# dotflipper.net
KiCad netlist of a schematic drawn in EAGLE
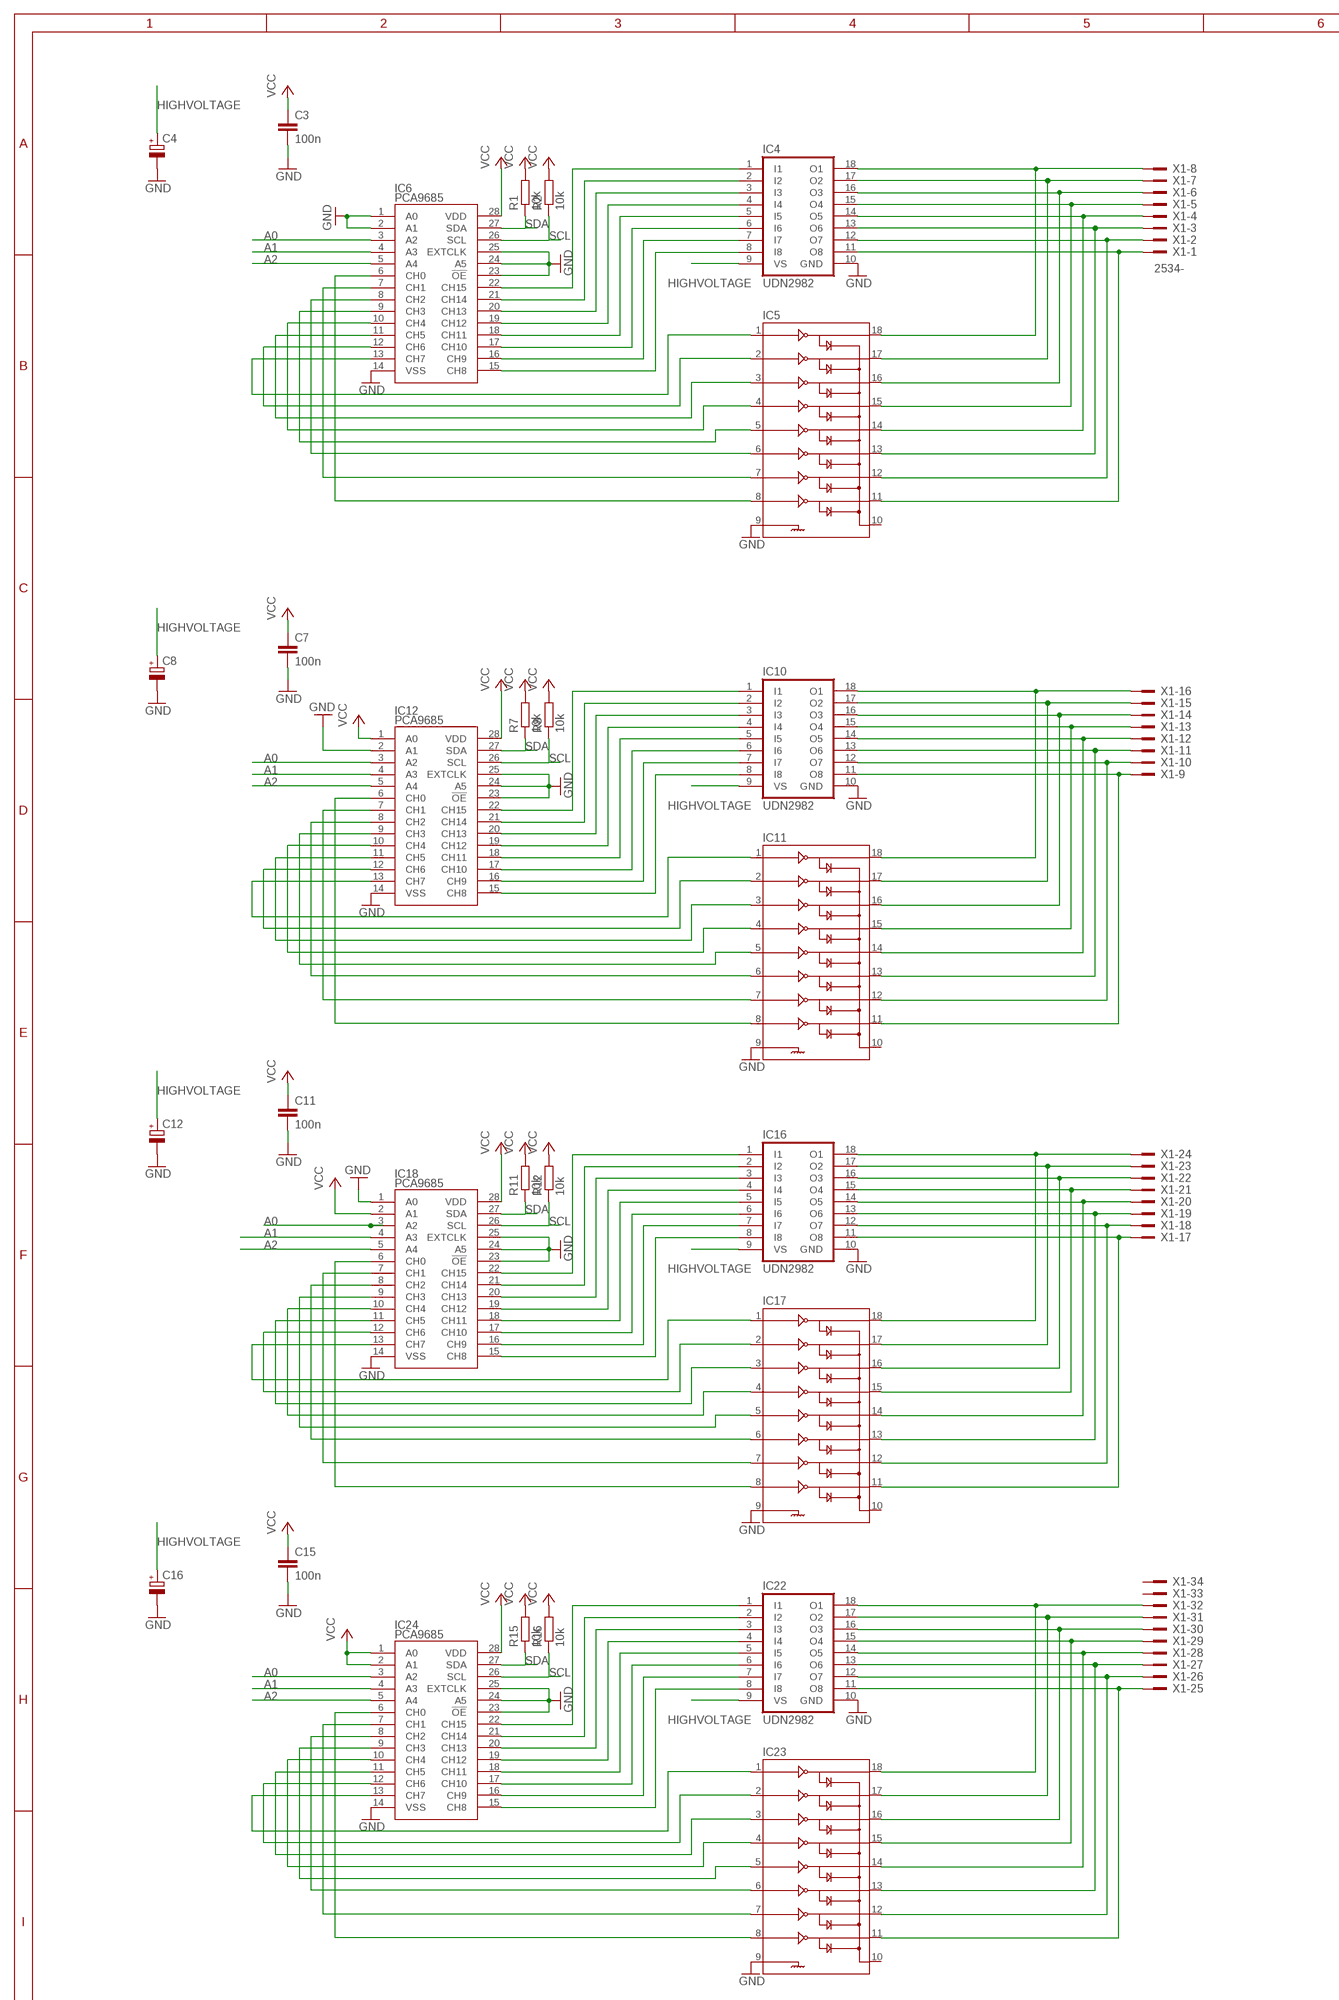
[diagram p0: schematic, sheet 1, part 1 of 2]
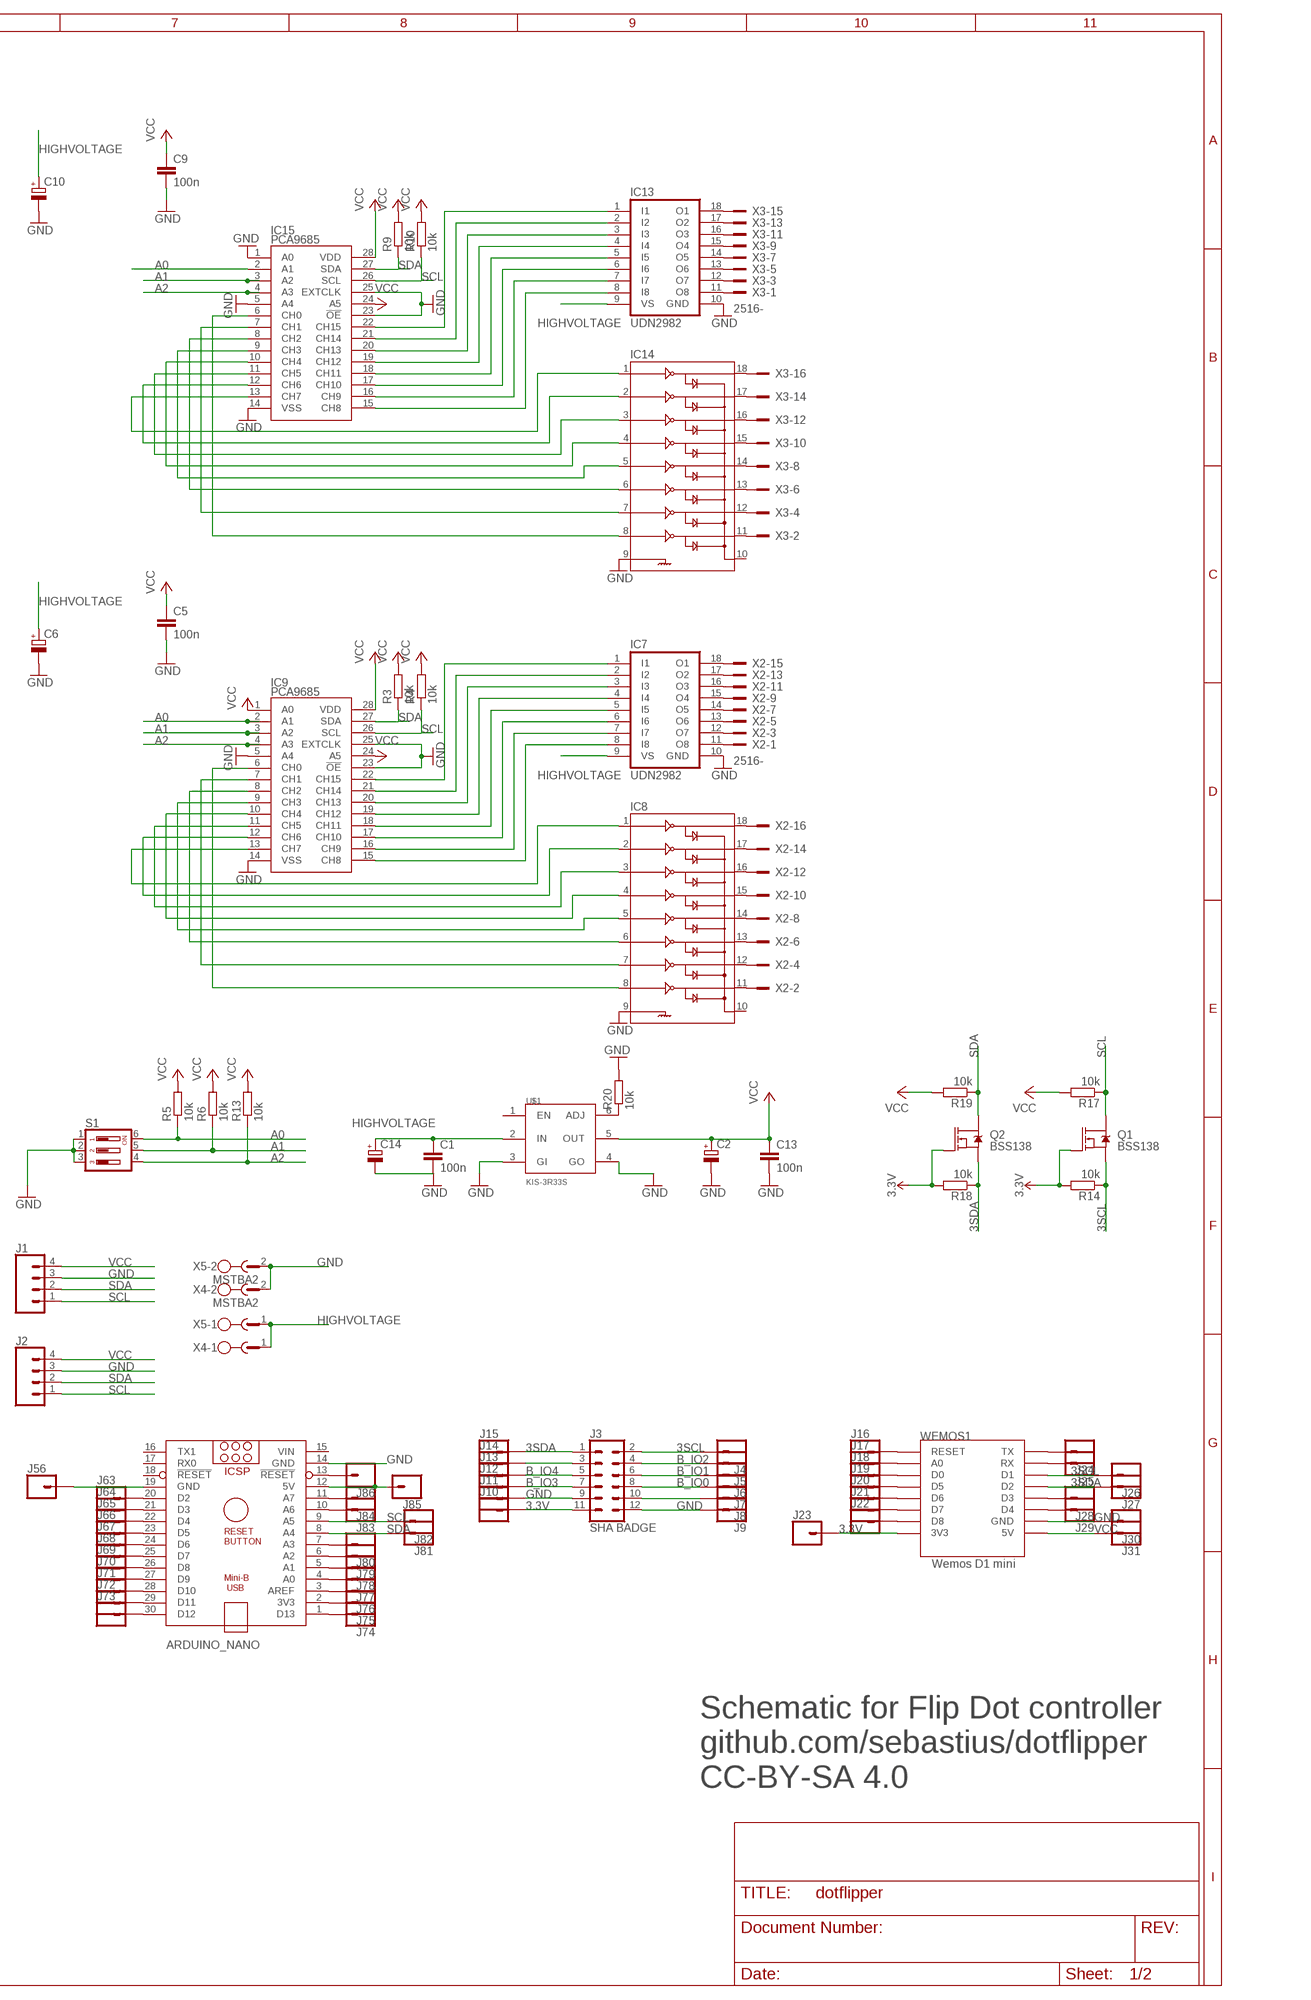
[diagram p1: schematic, sheet 1, part 2 of 2]
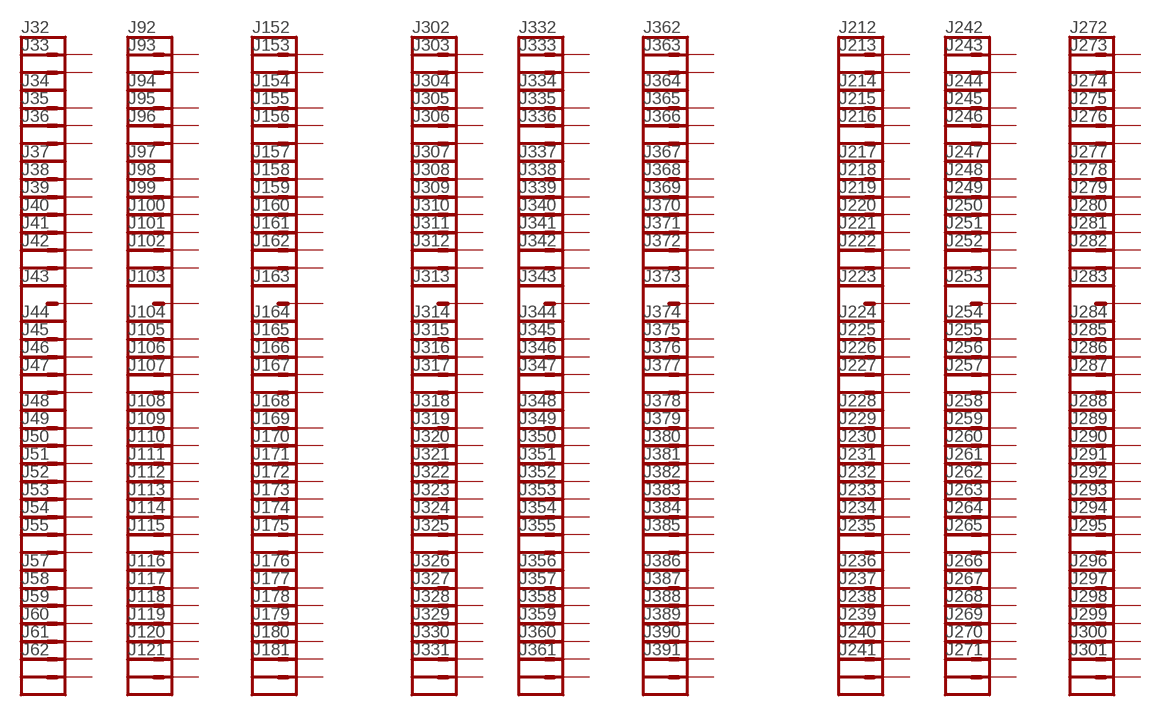
[diagram p2: schematic, sheet 2]

(export (version "E")
  (design (tool "Eeschema 10.0.6"))
  (components
    (comp (ref "ARDUINO_NANO")
      (value "ARDUINO_NANO")
      (footprint "eagle-import:ARDUINO_NANO")
      (libsource (lib "eagle-import") (part "ARDUINO_NANO"))
    )
    (comp (ref "C1")
      (value "100n")
      (footprint "eagle-import:C0603")
      (libsource (lib "eagle-import") (part "C-EUC0603"))
    )
    (comp (ref "C2")
      (value "CPOL-EUSANYO_SMD_F8")
      (footprint "eagle-import:SANYO-OSCON_SMD_F8")
      (libsource (lib "eagle-import") (part "CPOL-EUSANYO_SMD_F8"))
    )
    (comp (ref "C3")
      (value "100n")
      (footprint "eagle-import:C0603")
      (libsource (lib "eagle-import") (part "C-EUC0603"))
    )
    (comp (ref "C4")
      (value "CPOL-EUE2.5-6")
      (footprint "eagle-import:E2,5-6")
      (libsource (lib "eagle-import") (part "CPOL-EUE2.5-6"))
    )
    (comp (ref "C5")
      (value "100n")
      (footprint "eagle-import:C0603")
      (libsource (lib "eagle-import") (part "C-EUC0603"))
    )
    (comp (ref "C6")
      (value "CPOL-EUE2.5-6")
      (footprint "eagle-import:E2,5-6")
      (libsource (lib "eagle-import") (part "CPOL-EUE2.5-6"))
    )
    (comp (ref "C7")
      (value "100n")
      (footprint "eagle-import:C0603")
      (libsource (lib "eagle-import") (part "C-EUC0603"))
    )
    (comp (ref "C8")
      (value "CPOL-EUE2.5-6")
      (footprint "eagle-import:E2,5-6")
      (libsource (lib "eagle-import") (part "CPOL-EUE2.5-6"))
    )
    (comp (ref "C9")
      (value "100n")
      (footprint "eagle-import:C0603")
      (libsource (lib "eagle-import") (part "C-EUC0603"))
    )
    (comp (ref "C10")
      (value "CPOL-EUE2.5-6")
      (footprint "eagle-import:E2,5-6")
      (libsource (lib "eagle-import") (part "CPOL-EUE2.5-6"))
    )
    (comp (ref "C11")
      (value "100n")
      (footprint "eagle-import:C0603")
      (libsource (lib "eagle-import") (part "C-EUC0603"))
    )
    (comp (ref "C12")
      (value "CPOL-EUE2.5-6")
      (footprint "eagle-import:E2,5-6")
      (libsource (lib "eagle-import") (part "CPOL-EUE2.5-6"))
    )
    (comp (ref "C13")
      (value "100n")
      (footprint "eagle-import:C0603")
      (libsource (lib "eagle-import") (part "C-EUC0603"))
    )
    (comp (ref "C14")
      (value "CPOL-EUSANYO_SMD_F8")
      (footprint "eagle-import:SANYO-OSCON_SMD_F8")
      (libsource (lib "eagle-import") (part "CPOL-EUSANYO_SMD_F8"))
    )
    (comp (ref "C15")
      (value "100n")
      (footprint "eagle-import:C0603")
      (libsource (lib "eagle-import") (part "C-EUC0603"))
    )
    (comp (ref "C16")
      (value "CPOL-EUE2.5-6")
      (footprint "eagle-import:E2,5-6")
      (libsource (lib "eagle-import") (part "CPOL-EUE2.5-6"))
    )
    (comp (ref "IC4")
      (value "UDN2982")
      (footprint "eagle-import:DIL18")
      (libsource (lib "eagle-import") (part "UDN298A1"))
    )
    (comp (ref "IC5")
      (value "ULN2803DIP")
      (footprint "eagle-import:DIL18")
      (libsource (lib "eagle-import") (part "ULN2803DIP"))
    )
    (comp (ref "IC6")
      (value "PCA9685")
      (footprint "eagle-import:TSSOP-28_4MM")
      (libsource (lib "eagle-import") (part "PCA9685"))
    )
    (comp (ref "IC7")
      (value "UDN2982")
      (footprint "eagle-import:DIL18")
      (libsource (lib "eagle-import") (part "UDN298A1"))
    )
    (comp (ref "IC8")
      (value "ULN2803DIP")
      (footprint "eagle-import:DIL18")
      (libsource (lib "eagle-import") (part "ULN2803DIP"))
    )
    (comp (ref "IC9")
      (value "PCA9685")
      (footprint "eagle-import:TSSOP-28_4MM")
      (libsource (lib "eagle-import") (part "PCA9685"))
    )
    (comp (ref "IC10")
      (value "UDN2982")
      (footprint "eagle-import:DIL18")
      (libsource (lib "eagle-import") (part "UDN298A1"))
    )
    (comp (ref "IC11")
      (value "ULN2803DIP")
      (footprint "eagle-import:DIL18")
      (libsource (lib "eagle-import") (part "ULN2803DIP"))
    )
    (comp (ref "IC12")
      (value "PCA9685")
      (footprint "eagle-import:TSSOP-28_4MM")
      (libsource (lib "eagle-import") (part "PCA9685"))
    )
    (comp (ref "IC13")
      (value "UDN2982")
      (footprint "eagle-import:DIL18")
      (libsource (lib "eagle-import") (part "UDN298A1"))
    )
    (comp (ref "IC14")
      (value "ULN2803DIP")
      (footprint "eagle-import:DIL18")
      (libsource (lib "eagle-import") (part "ULN2803DIP"))
    )
    (comp (ref "IC15")
      (value "PCA9685")
      (footprint "eagle-import:TSSOP-28_4MM")
      (libsource (lib "eagle-import") (part "PCA9685"))
    )
    (comp (ref "IC16")
      (value "UDN2982")
      (footprint "eagle-import:DIL18")
      (libsource (lib "eagle-import") (part "UDN298A1"))
    )
    (comp (ref "IC17")
      (value "ULN2803DIP")
      (footprint "eagle-import:DIL18")
      (libsource (lib "eagle-import") (part "ULN2803DIP"))
    )
    (comp (ref "IC18")
      (value "PCA9685")
      (footprint "eagle-import:TSSOP-28_4MM")
      (libsource (lib "eagle-import") (part "PCA9685"))
    )
    (comp (ref "IC22")
      (value "UDN2982")
      (footprint "eagle-import:DIL18")
      (libsource (lib "eagle-import") (part "UDN298A1"))
    )
    (comp (ref "IC23")
      (value "ULN2803DIP")
      (footprint "eagle-import:DIL18")
      (libsource (lib "eagle-import") (part "ULN2803DIP"))
    )
    (comp (ref "IC24")
      (value "PCA9685")
      (footprint "eagle-import:TSSOP-28_4MM")
      (libsource (lib "eagle-import") (part "PCA9685"))
    )
    (comp (ref "J1")
      (value "CONN_04")
      (footprint "eagle-import:1X04")
      (libsource (lib "eagle-import") (part "CONN_04"))
    )
    (comp (ref "J2")
      (value "CONN_04")
      (footprint "eagle-import:1X04")
      (libsource (lib "eagle-import") (part "CONN_04"))
    )
    (comp (ref "J3")
      (value "SHA BADGE")
      (footprint "eagle-import:2X6")
      (libsource (lib "eagle-import") (part "CONN_06X2PTH_FEMALE"))
    )
    (comp (ref "J4")
      (value "CONN_01")
      (footprint "eagle-import:1X01")
      (libsource (lib "eagle-import") (part "CONN_01"))
    )
    (comp (ref "J5")
      (value "CONN_01")
      (footprint "eagle-import:1X01")
      (libsource (lib "eagle-import") (part "CONN_01"))
    )
    (comp (ref "J6")
      (value "CONN_01")
      (footprint "eagle-import:1X01")
      (libsource (lib "eagle-import") (part "CONN_01"))
    )
    (comp (ref "J7")
      (value "CONN_01")
      (footprint "eagle-import:1X01")
      (libsource (lib "eagle-import") (part "CONN_01"))
    )
    (comp (ref "J8")
      (value "CONN_01")
      (footprint "eagle-import:1X01")
      (libsource (lib "eagle-import") (part "CONN_01"))
    )
    (comp (ref "J9")
      (value "CONN_01")
      (footprint "eagle-import:1X01")
      (libsource (lib "eagle-import") (part "CONN_01"))
    )
    (comp (ref "J10")
      (value "CONN_01")
      (footprint "eagle-import:1X01")
      (libsource (lib "eagle-import") (part "CONN_01"))
    )
    (comp (ref "J11")
      (value "CONN_01")
      (footprint "eagle-import:1X01")
      (libsource (lib "eagle-import") (part "CONN_01"))
    )
    (comp (ref "J12")
      (value "CONN_01")
      (footprint "eagle-import:1X01")
      (libsource (lib "eagle-import") (part "CONN_01"))
    )
    (comp (ref "J13")
      (value "CONN_01")
      (footprint "eagle-import:1X01")
      (libsource (lib "eagle-import") (part "CONN_01"))
    )
    (comp (ref "J14")
      (value "CONN_01")
      (footprint "eagle-import:1X01")
      (libsource (lib "eagle-import") (part "CONN_01"))
    )
    (comp (ref "J15")
      (value "CONN_01")
      (footprint "eagle-import:1X01")
      (libsource (lib "eagle-import") (part "CONN_01"))
    )
    (comp (ref "J16")
      (value "CONN_01")
      (footprint "eagle-import:1X01")
      (libsource (lib "eagle-import") (part "CONN_01"))
    )
    (comp (ref "J17")
      (value "CONN_01")
      (footprint "eagle-import:1X01")
      (libsource (lib "eagle-import") (part "CONN_01"))
    )
    (comp (ref "J18")
      (value "CONN_01")
      (footprint "eagle-import:1X01")
      (libsource (lib "eagle-import") (part "CONN_01"))
    )
    (comp (ref "J19")
      (value "CONN_01")
      (footprint "eagle-import:1X01")
      (libsource (lib "eagle-import") (part "CONN_01"))
    )
    (comp (ref "J20")
      (value "CONN_01")
      (footprint "eagle-import:1X01")
      (libsource (lib "eagle-import") (part "CONN_01"))
    )
    (comp (ref "J21")
      (value "CONN_01")
      (footprint "eagle-import:1X01")
      (libsource (lib "eagle-import") (part "CONN_01"))
    )
    (comp (ref "J22")
      (value "CONN_01")
      (footprint "eagle-import:1X01")
      (libsource (lib "eagle-import") (part "CONN_01"))
    )
    (comp (ref "J23")
      (value "CONN_01")
      (footprint "eagle-import:1X01")
      (libsource (lib "eagle-import") (part "CONN_01"))
    )
    (comp (ref "J24")
      (value "CONN_01")
      (footprint "eagle-import:1X01")
      (libsource (lib "eagle-import") (part "CONN_01"))
    )
    (comp (ref "J25")
      (value "CONN_01")
      (footprint "eagle-import:1X01")
      (libsource (lib "eagle-import") (part "CONN_01"))
    )
    (comp (ref "J26")
      (value "CONN_01")
      (footprint "eagle-import:1X01")
      (libsource (lib "eagle-import") (part "CONN_01"))
    )
    (comp (ref "J27")
      (value "CONN_01")
      (footprint "eagle-import:1X01")
      (libsource (lib "eagle-import") (part "CONN_01"))
    )
    (comp (ref "J28")
      (value "CONN_01")
      (footprint "eagle-import:1X01")
      (libsource (lib "eagle-import") (part "CONN_01"))
    )
    (comp (ref "J29")
      (value "CONN_01")
      (footprint "eagle-import:1X01")
      (libsource (lib "eagle-import") (part "CONN_01"))
    )
    (comp (ref "J30")
      (value "CONN_01")
      (footprint "eagle-import:1X01")
      (libsource (lib "eagle-import") (part "CONN_01"))
    )
    (comp (ref "J31")
      (value "CONN_01")
      (footprint "eagle-import:1X01")
      (libsource (lib "eagle-import") (part "CONN_01"))
    )
    (comp (ref "J56")
      (value "CONN_01")
      (footprint "eagle-import:1X01")
      (libsource (lib "eagle-import") (part "CONN_01"))
    )
    (comp (ref "J63")
      (value "CONN_01")
      (footprint "eagle-import:1X01")
      (libsource (lib "eagle-import") (part "CONN_01"))
    )
    (comp (ref "J64")
      (value "CONN_01")
      (footprint "eagle-import:1X01")
      (libsource (lib "eagle-import") (part "CONN_01"))
    )
    (comp (ref "J65")
      (value "CONN_01")
      (footprint "eagle-import:1X01")
      (libsource (lib "eagle-import") (part "CONN_01"))
    )
    (comp (ref "J66")
      (value "CONN_01")
      (footprint "eagle-import:1X01")
      (libsource (lib "eagle-import") (part "CONN_01"))
    )
    (comp (ref "J67")
      (value "CONN_01")
      (footprint "eagle-import:1X01")
      (libsource (lib "eagle-import") (part "CONN_01"))
    )
    (comp (ref "J68")
      (value "CONN_01")
      (footprint "eagle-import:1X01")
      (libsource (lib "eagle-import") (part "CONN_01"))
    )
    (comp (ref "J69")
      (value "CONN_01")
      (footprint "eagle-import:1X01")
      (libsource (lib "eagle-import") (part "CONN_01"))
    )
    (comp (ref "J70")
      (value "CONN_01")
      (footprint "eagle-import:1X01")
      (libsource (lib "eagle-import") (part "CONN_01"))
    )
    (comp (ref "J71")
      (value "CONN_01")
      (footprint "eagle-import:1X01")
      (libsource (lib "eagle-import") (part "CONN_01"))
    )
    (comp (ref "J72")
      (value "CONN_01")
      (footprint "eagle-import:1X01")
      (libsource (lib "eagle-import") (part "CONN_01"))
    )
    (comp (ref "J73")
      (value "CONN_01")
      (footprint "eagle-import:1X01")
      (libsource (lib "eagle-import") (part "CONN_01"))
    )
    (comp (ref "J74")
      (value "CONN_01")
      (footprint "eagle-import:1X01")
      (libsource (lib "eagle-import") (part "CONN_01"))
    )
    (comp (ref "J75")
      (value "CONN_01")
      (footprint "eagle-import:1X01")
      (libsource (lib "eagle-import") (part "CONN_01"))
    )
    (comp (ref "J76")
      (value "CONN_01")
      (footprint "eagle-import:1X01")
      (libsource (lib "eagle-import") (part "CONN_01"))
    )
    (comp (ref "J77")
      (value "CONN_01")
      (footprint "eagle-import:1X01")
      (libsource (lib "eagle-import") (part "CONN_01"))
    )
    (comp (ref "J78")
      (value "CONN_01")
      (footprint "eagle-import:1X01")
      (libsource (lib "eagle-import") (part "CONN_01"))
    )
    (comp (ref "J79")
      (value "CONN_01")
      (footprint "eagle-import:1X01")
      (libsource (lib "eagle-import") (part "CONN_01"))
    )
    (comp (ref "J80")
      (value "CONN_01")
      (footprint "eagle-import:1X01")
      (libsource (lib "eagle-import") (part "CONN_01"))
    )
    (comp (ref "J81")
      (value "CONN_01")
      (footprint "eagle-import:1X01")
      (libsource (lib "eagle-import") (part "CONN_01"))
    )
    (comp (ref "J82")
      (value "CONN_01")
      (footprint "eagle-import:1X01")
      (libsource (lib "eagle-import") (part "CONN_01"))
    )
    (comp (ref "J83")
      (value "CONN_01")
      (footprint "eagle-import:1X01")
      (libsource (lib "eagle-import") (part "CONN_01"))
    )
    (comp (ref "J84")
      (value "CONN_01")
      (footprint "eagle-import:1X01")
      (libsource (lib "eagle-import") (part "CONN_01"))
    )
    (comp (ref "J85")
      (value "CONN_01")
      (footprint "eagle-import:1X01")
      (libsource (lib "eagle-import") (part "CONN_01"))
    )
    (comp (ref "J86")
      (value "CONN_01")
      (footprint "eagle-import:1X01")
      (libsource (lib "eagle-import") (part "CONN_01"))
    )
    (comp (ref "Q1")
      (value "BSS138")
      (footprint "eagle-import:SOT23-3")
      (libsource (lib "eagle-import") (part "MOSFET-NCH-BSS138"))
    )
    (comp (ref "Q2")
      (value "BSS138")
      (footprint "eagle-import:SOT23-3")
      (libsource (lib "eagle-import") (part "MOSFET-NCH-BSS138"))
    )
    (comp (ref "R1")
      (value "10k")
      (footprint "eagle-import:R0603")
      (libsource (lib "eagle-import") (part "R-EU_R0603"))
    )
    (comp (ref "R2")
      (value "10k")
      (footprint "eagle-import:R0603")
      (libsource (lib "eagle-import") (part "R-EU_R0603"))
    )
    (comp (ref "R3")
      (value "10k")
      (footprint "eagle-import:R0603")
      (libsource (lib "eagle-import") (part "R-EU_R0603"))
    )
    (comp (ref "R4")
      (value "10k")
      (footprint "eagle-import:R0603")
      (libsource (lib "eagle-import") (part "R-EU_R0603"))
    )
    (comp (ref "R5")
      (value "10k")
      (footprint "eagle-import:R0603")
      (libsource (lib "eagle-import") (part "R-EU_R0603"))
    )
    (comp (ref "R6")
      (value "10k")
      (footprint "eagle-import:R0603")
      (libsource (lib "eagle-import") (part "R-EU_R0603"))
    )
    (comp (ref "R7")
      (value "10k")
      (footprint "eagle-import:R0603")
      (libsource (lib "eagle-import") (part "R-EU_R0603"))
    )
    (comp (ref "R8")
      (value "10k")
      (footprint "eagle-import:R0603")
      (libsource (lib "eagle-import") (part "R-EU_R0603"))
    )
    (comp (ref "R9")
      (value "10k")
      (footprint "eagle-import:R0603")
      (libsource (lib "eagle-import") (part "R-EU_R0603"))
    )
    (comp (ref "R10")
      (value "10k")
      (footprint "eagle-import:R0603")
      (libsource (lib "eagle-import") (part "R-EU_R0603"))
    )
    (comp (ref "R11")
      (value "10k")
      (footprint "eagle-import:R0603")
      (libsource (lib "eagle-import") (part "R-EU_R0603"))
    )
    (comp (ref "R12")
      (value "10k")
      (footprint "eagle-import:R0603")
      (libsource (lib "eagle-import") (part "R-EU_R0603"))
    )
    (comp (ref "R13")
      (value "10k")
      (footprint "eagle-import:R0603")
      (libsource (lib "eagle-import") (part "R-EU_R0603"))
    )
    (comp (ref "R14")
      (value "10k")
      (footprint "eagle-import:R0603")
      (libsource (lib "eagle-import") (part "R-EU_R0603"))
    )
    (comp (ref "R15")
      (value "10k")
      (footprint "eagle-import:R0603")
      (libsource (lib "eagle-import") (part "R-EU_R0603"))
    )
    (comp (ref "R16")
      (value "10k")
      (footprint "eagle-import:R0603")
      (libsource (lib "eagle-import") (part "R-EU_R0603"))
    )
    (comp (ref "R17")
      (value "10k")
      (footprint "eagle-import:R0603")
      (libsource (lib "eagle-import") (part "R-EU_R0603"))
    )
    (comp (ref "R18")
      (value "10k")
      (footprint "eagle-import:R0603")
      (libsource (lib "eagle-import") (part "R-EU_R0603"))
    )
    (comp (ref "R19")
      (value "10k")
      (footprint "eagle-import:R0603")
      (libsource (lib "eagle-import") (part "R-EU_R0603"))
    )
    (comp (ref "R20")
      (value "10k")
      (footprint "eagle-import:R0603")
      (libsource (lib "eagle-import") (part "R-EU_R0603"))
    )
    (comp (ref "S1")
      (value "DIP03YL")
      (footprint "eagle-import:DIP03YL")
      (libsource (lib "eagle-import") (part "DIP03YL"))
    )
    (comp (ref "U$1")
      (value "KIS-3R33S")
      (footprint "eagle-import:KIS-3R33S")
      (libsource (lib "eagle-import") (part "KIS-3R33S"))
    )
    (comp (ref "WEMOS1")
      (value "Wemos D1 mini")
      (footprint "eagle-import:WEMOS-D1-MINI")
      (libsource (lib "eagle-import") (part "WEMOS-D1-MINI"))
    )
    (comp (ref "X1")
      (value "2534-")
      (footprint "eagle-import:PAK100_2500-34")
      (libsource (lib "eagle-import") (part "2534-"))
    )
    (comp (ref "X2")
      (value "2516-")
      (footprint "eagle-import:PAK100_2500-16")
      (libsource (lib "eagle-import") (part "2516-"))
    )
    (comp (ref "X3")
      (value "2516-")
      (footprint "eagle-import:PAK100_2500-16")
      (libsource (lib "eagle-import") (part "2516-"))
    )
    (comp (ref "X4")
      (value "MSTBA2")
      (footprint "eagle-import:MSTBA2")
      (fields (field (name "MF") "FARNELL") (field (name "MPN") "1757242"))
      (libsource (lib "eagle-import") (part "MSTBA2"))
    )
    (comp (ref "X5")
      (value "MSTBA2")
      (footprint "eagle-import:MSTBA2")
      (fields (field (name "MF") "FARNELL") (field (name "MPN") "1757242"))
      (libsource (lib "eagle-import") (part "MSTBA2"))
    )
    (comp (ref "J32")
      (value "CONN_01")
      (footprint "eagle-import:1X01")
      (libsource (lib "eagle-import") (part "CONN_01"))
    )
    (comp (ref "J33")
      (value "CONN_01")
      (footprint "eagle-import:1X01")
      (libsource (lib "eagle-import") (part "CONN_01"))
    )
    (comp (ref "J34")
      (value "CONN_01")
      (footprint "eagle-import:1X01")
      (libsource (lib "eagle-import") (part "CONN_01"))
    )
    (comp (ref "J35")
      (value "CONN_01")
      (footprint "eagle-import:1X01")
      (libsource (lib "eagle-import") (part "CONN_01"))
    )
    (comp (ref "J36")
      (value "CONN_01")
      (footprint "eagle-import:1X01")
      (libsource (lib "eagle-import") (part "CONN_01"))
    )
    (comp (ref "J37")
      (value "CONN_01")
      (footprint "eagle-import:1X01")
      (libsource (lib "eagle-import") (part "CONN_01"))
    )
    (comp (ref "J38")
      (value "CONN_01")
      (footprint "eagle-import:1X01")
      (libsource (lib "eagle-import") (part "CONN_01"))
    )
    (comp (ref "J39")
      (value "CONN_01")
      (footprint "eagle-import:1X01")
      (libsource (lib "eagle-import") (part "CONN_01"))
    )
    (comp (ref "J40")
      (value "CONN_01")
      (footprint "eagle-import:1X01")
      (libsource (lib "eagle-import") (part "CONN_01"))
    )
    (comp (ref "J41")
      (value "CONN_01")
      (footprint "eagle-import:1X01")
      (libsource (lib "eagle-import") (part "CONN_01"))
    )
    (comp (ref "J42")
      (value "CONN_01")
      (footprint "eagle-import:1X01")
      (libsource (lib "eagle-import") (part "CONN_01"))
    )
    (comp (ref "J43")
      (value "CONN_01")
      (footprint "eagle-import:1X01")
      (libsource (lib "eagle-import") (part "CONN_01"))
    )
    (comp (ref "J44")
      (value "CONN_01")
      (footprint "eagle-import:1X01")
      (libsource (lib "eagle-import") (part "CONN_01"))
    )
    (comp (ref "J45")
      (value "CONN_01")
      (footprint "eagle-import:1X01")
      (libsource (lib "eagle-import") (part "CONN_01"))
    )
    (comp (ref "J46")
      (value "CONN_01")
      (footprint "eagle-import:1X01")
      (libsource (lib "eagle-import") (part "CONN_01"))
    )
    (comp (ref "J47")
      (value "CONN_01")
      (footprint "eagle-import:1X01")
      (libsource (lib "eagle-import") (part "CONN_01"))
    )
    (comp (ref "J48")
      (value "CONN_01")
      (footprint "eagle-import:1X01")
      (libsource (lib "eagle-import") (part "CONN_01"))
    )
    (comp (ref "J49")
      (value "CONN_01")
      (footprint "eagle-import:1X01")
      (libsource (lib "eagle-import") (part "CONN_01"))
    )
    (comp (ref "J50")
      (value "CONN_01")
      (footprint "eagle-import:1X01")
      (libsource (lib "eagle-import") (part "CONN_01"))
    )
    (comp (ref "J51")
      (value "CONN_01")
      (footprint "eagle-import:1X01")
      (libsource (lib "eagle-import") (part "CONN_01"))
    )
    (comp (ref "J52")
      (value "CONN_01")
      (footprint "eagle-import:1X01")
      (libsource (lib "eagle-import") (part "CONN_01"))
    )
    (comp (ref "J53")
      (value "CONN_01")
      (footprint "eagle-import:1X01")
      (libsource (lib "eagle-import") (part "CONN_01"))
    )
    (comp (ref "J54")
      (value "CONN_01")
      (footprint "eagle-import:1X01")
      (libsource (lib "eagle-import") (part "CONN_01"))
    )
    (comp (ref "J55")
      (value "CONN_01")
      (footprint "eagle-import:1X01")
      (libsource (lib "eagle-import") (part "CONN_01"))
    )
    (comp (ref "J57")
      (value "CONN_01")
      (footprint "eagle-import:1X01")
      (libsource (lib "eagle-import") (part "CONN_01"))
    )
    (comp (ref "J58")
      (value "CONN_01")
      (footprint "eagle-import:1X01")
      (libsource (lib "eagle-import") (part "CONN_01"))
    )
    (comp (ref "J59")
      (value "CONN_01")
      (footprint "eagle-import:1X01")
      (libsource (lib "eagle-import") (part "CONN_01"))
    )
    (comp (ref "J60")
      (value "CONN_01")
      (footprint "eagle-import:1X01")
      (libsource (lib "eagle-import") (part "CONN_01"))
    )
    (comp (ref "J61")
      (value "CONN_01")
      (footprint "eagle-import:1X01")
      (libsource (lib "eagle-import") (part "CONN_01"))
    )
    (comp (ref "J62")
      (value "CONN_01")
      (footprint "eagle-import:1X01")
      (libsource (lib "eagle-import") (part "CONN_01"))
    )
    (comp (ref "J92")
      (value "CONN_01")
      (footprint "eagle-import:1X01")
      (libsource (lib "eagle-import") (part "CONN_01"))
    )
    (comp (ref "J93")
      (value "CONN_01")
      (footprint "eagle-import:1X01")
      (libsource (lib "eagle-import") (part "CONN_01"))
    )
    (comp (ref "J94")
      (value "CONN_01")
      (footprint "eagle-import:1X01")
      (libsource (lib "eagle-import") (part "CONN_01"))
    )
    (comp (ref "J95")
      (value "CONN_01")
      (footprint "eagle-import:1X01")
      (libsource (lib "eagle-import") (part "CONN_01"))
    )
    (comp (ref "J96")
      (value "CONN_01")
      (footprint "eagle-import:1X01")
      (libsource (lib "eagle-import") (part "CONN_01"))
    )
    (comp (ref "J97")
      (value "CONN_01")
      (footprint "eagle-import:1X01")
      (libsource (lib "eagle-import") (part "CONN_01"))
    )
    (comp (ref "J98")
      (value "CONN_01")
      (footprint "eagle-import:1X01")
      (libsource (lib "eagle-import") (part "CONN_01"))
    )
    (comp (ref "J99")
      (value "CONN_01")
      (footprint "eagle-import:1X01")
      (libsource (lib "eagle-import") (part "CONN_01"))
    )
    (comp (ref "J100")
      (value "CONN_01")
      (footprint "eagle-import:1X01")
      (libsource (lib "eagle-import") (part "CONN_01"))
    )
    (comp (ref "J101")
      (value "CONN_01")
      (footprint "eagle-import:1X01")
      (libsource (lib "eagle-import") (part "CONN_01"))
    )
    (comp (ref "J102")
      (value "CONN_01")
      (footprint "eagle-import:1X01")
      (libsource (lib "eagle-import") (part "CONN_01"))
    )
    (comp (ref "J103")
      (value "CONN_01")
      (footprint "eagle-import:1X01")
      (libsource (lib "eagle-import") (part "CONN_01"))
    )
    (comp (ref "J104")
      (value "CONN_01")
      (footprint "eagle-import:1X01")
      (libsource (lib "eagle-import") (part "CONN_01"))
    )
    (comp (ref "J105")
      (value "CONN_01")
      (footprint "eagle-import:1X01")
      (libsource (lib "eagle-import") (part "CONN_01"))
    )
    (comp (ref "J106")
      (value "CONN_01")
      (footprint "eagle-import:1X01")
      (libsource (lib "eagle-import") (part "CONN_01"))
    )
    (comp (ref "J107")
      (value "CONN_01")
      (footprint "eagle-import:1X01")
      (libsource (lib "eagle-import") (part "CONN_01"))
    )
    (comp (ref "J108")
      (value "CONN_01")
      (footprint "eagle-import:1X01")
      (libsource (lib "eagle-import") (part "CONN_01"))
    )
    (comp (ref "J109")
      (value "CONN_01")
      (footprint "eagle-import:1X01")
      (libsource (lib "eagle-import") (part "CONN_01"))
    )
    (comp (ref "J110")
      (value "CONN_01")
      (footprint "eagle-import:1X01")
      (libsource (lib "eagle-import") (part "CONN_01"))
    )
    (comp (ref "J111")
      (value "CONN_01")
      (footprint "eagle-import:1X01")
      (libsource (lib "eagle-import") (part "CONN_01"))
    )
    (comp (ref "J112")
      (value "CONN_01")
      (footprint "eagle-import:1X01")
      (libsource (lib "eagle-import") (part "CONN_01"))
    )
    (comp (ref "J113")
      (value "CONN_01")
      (footprint "eagle-import:1X01")
      (libsource (lib "eagle-import") (part "CONN_01"))
    )
    (comp (ref "J114")
      (value "CONN_01")
      (footprint "eagle-import:1X01")
      (libsource (lib "eagle-import") (part "CONN_01"))
    )
    (comp (ref "J115")
      (value "CONN_01")
      (footprint "eagle-import:1X01")
      (libsource (lib "eagle-import") (part "CONN_01"))
    )
    (comp (ref "J116")
      (value "CONN_01")
      (footprint "eagle-import:1X01")
      (libsource (lib "eagle-import") (part "CONN_01"))
    )
    (comp (ref "J117")
      (value "CONN_01")
      (footprint "eagle-import:1X01")
      (libsource (lib "eagle-import") (part "CONN_01"))
    )
    (comp (ref "J118")
      (value "CONN_01")
      (footprint "eagle-import:1X01")
      (libsource (lib "eagle-import") (part "CONN_01"))
    )
    (comp (ref "J119")
      (value "CONN_01")
      (footprint "eagle-import:1X01")
      (libsource (lib "eagle-import") (part "CONN_01"))
    )
    (comp (ref "J120")
      (value "CONN_01")
      (footprint "eagle-import:1X01")
      (libsource (lib "eagle-import") (part "CONN_01"))
    )
    (comp (ref "J121")
      (value "CONN_01")
      (footprint "eagle-import:1X01")
      (libsource (lib "eagle-import") (part "CONN_01"))
    )
    (comp (ref "J152")
      (value "CONN_01")
      (footprint "eagle-import:1X01")
      (libsource (lib "eagle-import") (part "CONN_01"))
    )
    (comp (ref "J153")
      (value "CONN_01")
      (footprint "eagle-import:1X01")
      (libsource (lib "eagle-import") (part "CONN_01"))
    )
    (comp (ref "J154")
      (value "CONN_01")
      (footprint "eagle-import:1X01")
      (libsource (lib "eagle-import") (part "CONN_01"))
    )
    (comp (ref "J155")
      (value "CONN_01")
      (footprint "eagle-import:1X01")
      (libsource (lib "eagle-import") (part "CONN_01"))
    )
    (comp (ref "J156")
      (value "CONN_01")
      (footprint "eagle-import:1X01")
      (libsource (lib "eagle-import") (part "CONN_01"))
    )
    (comp (ref "J157")
      (value "CONN_01")
      (footprint "eagle-import:1X01")
      (libsource (lib "eagle-import") (part "CONN_01"))
    )
    (comp (ref "J158")
      (value "CONN_01")
      (footprint "eagle-import:1X01")
      (libsource (lib "eagle-import") (part "CONN_01"))
    )
    (comp (ref "J159")
      (value "CONN_01")
      (footprint "eagle-import:1X01")
      (libsource (lib "eagle-import") (part "CONN_01"))
    )
    (comp (ref "J160")
      (value "CONN_01")
      (footprint "eagle-import:1X01")
      (libsource (lib "eagle-import") (part "CONN_01"))
    )
    (comp (ref "J161")
      (value "CONN_01")
      (footprint "eagle-import:1X01")
      (libsource (lib "eagle-import") (part "CONN_01"))
    )
    (comp (ref "J162")
      (value "CONN_01")
      (footprint "eagle-import:1X01")
      (libsource (lib "eagle-import") (part "CONN_01"))
    )
    (comp (ref "J163")
      (value "CONN_01")
      (footprint "eagle-import:1X01")
      (libsource (lib "eagle-import") (part "CONN_01"))
    )
    (comp (ref "J164")
      (value "CONN_01")
      (footprint "eagle-import:1X01")
      (libsource (lib "eagle-import") (part "CONN_01"))
    )
    (comp (ref "J165")
      (value "CONN_01")
      (footprint "eagle-import:1X01")
      (libsource (lib "eagle-import") (part "CONN_01"))
    )
    (comp (ref "J166")
      (value "CONN_01")
      (footprint "eagle-import:1X01")
      (libsource (lib "eagle-import") (part "CONN_01"))
    )
    (comp (ref "J167")
      (value "CONN_01")
      (footprint "eagle-import:1X01")
      (libsource (lib "eagle-import") (part "CONN_01"))
    )
    (comp (ref "J168")
      (value "CONN_01")
      (footprint "eagle-import:1X01")
      (libsource (lib "eagle-import") (part "CONN_01"))
    )
    (comp (ref "J169")
      (value "CONN_01")
      (footprint "eagle-import:1X01")
      (libsource (lib "eagle-import") (part "CONN_01"))
    )
    (comp (ref "J170")
      (value "CONN_01")
      (footprint "eagle-import:1X01")
      (libsource (lib "eagle-import") (part "CONN_01"))
    )
    (comp (ref "J171")
      (value "CONN_01")
      (footprint "eagle-import:1X01")
      (libsource (lib "eagle-import") (part "CONN_01"))
    )
    (comp (ref "J172")
      (value "CONN_01")
      (footprint "eagle-import:1X01")
      (libsource (lib "eagle-import") (part "CONN_01"))
    )
    (comp (ref "J173")
      (value "CONN_01")
      (footprint "eagle-import:1X01")
      (libsource (lib "eagle-import") (part "CONN_01"))
    )
    (comp (ref "J174")
      (value "CONN_01")
      (footprint "eagle-import:1X01")
      (libsource (lib "eagle-import") (part "CONN_01"))
    )
    (comp (ref "J175")
      (value "CONN_01")
      (footprint "eagle-import:1X01")
      (libsource (lib "eagle-import") (part "CONN_01"))
    )
    (comp (ref "J176")
      (value "CONN_01")
      (footprint "eagle-import:1X01")
      (libsource (lib "eagle-import") (part "CONN_01"))
    )
    (comp (ref "J177")
      (value "CONN_01")
      (footprint "eagle-import:1X01")
      (libsource (lib "eagle-import") (part "CONN_01"))
    )
    (comp (ref "J178")
      (value "CONN_01")
      (footprint "eagle-import:1X01")
      (libsource (lib "eagle-import") (part "CONN_01"))
    )
    (comp (ref "J179")
      (value "CONN_01")
      (footprint "eagle-import:1X01")
      (libsource (lib "eagle-import") (part "CONN_01"))
    )
    (comp (ref "J180")
      (value "CONN_01")
      (footprint "eagle-import:1X01")
      (libsource (lib "eagle-import") (part "CONN_01"))
    )
    (comp (ref "J181")
      (value "CONN_01")
      (footprint "eagle-import:1X01")
      (libsource (lib "eagle-import") (part "CONN_01"))
    )
    (comp (ref "J212")
      (value "CONN_01")
      (footprint "eagle-import:1X01")
      (libsource (lib "eagle-import") (part "CONN_01"))
    )
    (comp (ref "J213")
      (value "CONN_01")
      (footprint "eagle-import:1X01")
      (libsource (lib "eagle-import") (part "CONN_01"))
    )
    (comp (ref "J214")
      (value "CONN_01")
      (footprint "eagle-import:1X01")
      (libsource (lib "eagle-import") (part "CONN_01"))
    )
    (comp (ref "J215")
      (value "CONN_01")
      (footprint "eagle-import:1X01")
      (libsource (lib "eagle-import") (part "CONN_01"))
    )
    (comp (ref "J216")
      (value "CONN_01")
      (footprint "eagle-import:1X01")
      (libsource (lib "eagle-import") (part "CONN_01"))
    )
    (comp (ref "J217")
      (value "CONN_01")
      (footprint "eagle-import:1X01")
      (libsource (lib "eagle-import") (part "CONN_01"))
    )
    (comp (ref "J218")
      (value "CONN_01")
      (footprint "eagle-import:1X01")
      (libsource (lib "eagle-import") (part "CONN_01"))
    )
    (comp (ref "J219")
      (value "CONN_01")
      (footprint "eagle-import:1X01")
      (libsource (lib "eagle-import") (part "CONN_01"))
    )
    (comp (ref "J220")
      (value "CONN_01")
      (footprint "eagle-import:1X01")
      (libsource (lib "eagle-import") (part "CONN_01"))
    )
    (comp (ref "J221")
      (value "CONN_01")
      (footprint "eagle-import:1X01")
      (libsource (lib "eagle-import") (part "CONN_01"))
    )
    (comp (ref "J222")
      (value "CONN_01")
      (footprint "eagle-import:1X01")
      (libsource (lib "eagle-import") (part "CONN_01"))
    )
    (comp (ref "J223")
      (value "CONN_01")
      (footprint "eagle-import:1X01")
      (libsource (lib "eagle-import") (part "CONN_01"))
    )
    (comp (ref "J224")
      (value "CONN_01")
      (footprint "eagle-import:1X01")
      (libsource (lib "eagle-import") (part "CONN_01"))
    )
    (comp (ref "J225")
      (value "CONN_01")
      (footprint "eagle-import:1X01")
      (libsource (lib "eagle-import") (part "CONN_01"))
    )
    (comp (ref "J226")
      (value "CONN_01")
      (footprint "eagle-import:1X01")
      (libsource (lib "eagle-import") (part "CONN_01"))
    )
    (comp (ref "J227")
      (value "CONN_01")
      (footprint "eagle-import:1X01")
      (libsource (lib "eagle-import") (part "CONN_01"))
    )
    (comp (ref "J228")
      (value "CONN_01")
      (footprint "eagle-import:1X01")
      (libsource (lib "eagle-import") (part "CONN_01"))
    )
    (comp (ref "J229")
      (value "CONN_01")
      (footprint "eagle-import:1X01")
      (libsource (lib "eagle-import") (part "CONN_01"))
    )
    (comp (ref "J230")
      (value "CONN_01")
      (footprint "eagle-import:1X01")
      (libsource (lib "eagle-import") (part "CONN_01"))
    )
    (comp (ref "J231")
      (value "CONN_01")
      (footprint "eagle-import:1X01")
      (libsource (lib "eagle-import") (part "CONN_01"))
    )
    (comp (ref "J232")
      (value "CONN_01")
      (footprint "eagle-import:1X01")
      (libsource (lib "eagle-import") (part "CONN_01"))
    )
    (comp (ref "J233")
      (value "CONN_01")
      (footprint "eagle-import:1X01")
      (libsource (lib "eagle-import") (part "CONN_01"))
    )
    (comp (ref "J234")
      (value "CONN_01")
      (footprint "eagle-import:1X01")
      (libsource (lib "eagle-import") (part "CONN_01"))
    )
    (comp (ref "J235")
      (value "CONN_01")
      (footprint "eagle-import:1X01")
      (libsource (lib "eagle-import") (part "CONN_01"))
    )
    (comp (ref "J236")
      (value "CONN_01")
      (footprint "eagle-import:1X01")
      (libsource (lib "eagle-import") (part "CONN_01"))
    )
    (comp (ref "J237")
      (value "CONN_01")
      (footprint "eagle-import:1X01")
      (libsource (lib "eagle-import") (part "CONN_01"))
    )
    (comp (ref "J238")
      (value "CONN_01")
      (footprint "eagle-import:1X01")
      (libsource (lib "eagle-import") (part "CONN_01"))
    )
    (comp (ref "J239")
      (value "CONN_01")
      (footprint "eagle-import:1X01")
      (libsource (lib "eagle-import") (part "CONN_01"))
    )
    (comp (ref "J240")
      (value "CONN_01")
      (footprint "eagle-import:1X01")
      (libsource (lib "eagle-import") (part "CONN_01"))
    )
    (comp (ref "J241")
      (value "CONN_01")
      (footprint "eagle-import:1X01")
      (libsource (lib "eagle-import") (part "CONN_01"))
    )
    (comp (ref "J242")
      (value "CONN_01")
      (footprint "eagle-import:1X01")
      (libsource (lib "eagle-import") (part "CONN_01"))
    )
    (comp (ref "J243")
      (value "CONN_01")
      (footprint "eagle-import:1X01")
      (libsource (lib "eagle-import") (part "CONN_01"))
    )
    (comp (ref "J244")
      (value "CONN_01")
      (footprint "eagle-import:1X01")
      (libsource (lib "eagle-import") (part "CONN_01"))
    )
    (comp (ref "J245")
      (value "CONN_01")
      (footprint "eagle-import:1X01")
      (libsource (lib "eagle-import") (part "CONN_01"))
    )
    (comp (ref "J246")
      (value "CONN_01")
      (footprint "eagle-import:1X01")
      (libsource (lib "eagle-import") (part "CONN_01"))
    )
    (comp (ref "J247")
      (value "CONN_01")
      (footprint "eagle-import:1X01")
      (libsource (lib "eagle-import") (part "CONN_01"))
    )
    (comp (ref "J248")
      (value "CONN_01")
      (footprint "eagle-import:1X01")
      (libsource (lib "eagle-import") (part "CONN_01"))
    )
    (comp (ref "J249")
      (value "CONN_01")
      (footprint "eagle-import:1X01")
      (libsource (lib "eagle-import") (part "CONN_01"))
    )
    (comp (ref "J250")
      (value "CONN_01")
      (footprint "eagle-import:1X01")
      (libsource (lib "eagle-import") (part "CONN_01"))
    )
    (comp (ref "J251")
      (value "CONN_01")
      (footprint "eagle-import:1X01")
      (libsource (lib "eagle-import") (part "CONN_01"))
    )
    (comp (ref "J252")
      (value "CONN_01")
      (footprint "eagle-import:1X01")
      (libsource (lib "eagle-import") (part "CONN_01"))
    )
    (comp (ref "J253")
      (value "CONN_01")
      (footprint "eagle-import:1X01")
      (libsource (lib "eagle-import") (part "CONN_01"))
    )
    (comp (ref "J254")
      (value "CONN_01")
      (footprint "eagle-import:1X01")
      (libsource (lib "eagle-import") (part "CONN_01"))
    )
    (comp (ref "J255")
      (value "CONN_01")
      (footprint "eagle-import:1X01")
      (libsource (lib "eagle-import") (part "CONN_01"))
    )
    (comp (ref "J256")
      (value "CONN_01")
      (footprint "eagle-import:1X01")
      (libsource (lib "eagle-import") (part "CONN_01"))
    )
    (comp (ref "J257")
      (value "CONN_01")
      (footprint "eagle-import:1X01")
      (libsource (lib "eagle-import") (part "CONN_01"))
    )
    (comp (ref "J258")
      (value "CONN_01")
      (footprint "eagle-import:1X01")
      (libsource (lib "eagle-import") (part "CONN_01"))
    )
    (comp (ref "J259")
      (value "CONN_01")
      (footprint "eagle-import:1X01")
      (libsource (lib "eagle-import") (part "CONN_01"))
    )
    (comp (ref "J260")
      (value "CONN_01")
      (footprint "eagle-import:1X01")
      (libsource (lib "eagle-import") (part "CONN_01"))
    )
    (comp (ref "J261")
      (value "CONN_01")
      (footprint "eagle-import:1X01")
      (libsource (lib "eagle-import") (part "CONN_01"))
    )
    (comp (ref "J262")
      (value "CONN_01")
      (footprint "eagle-import:1X01")
      (libsource (lib "eagle-import") (part "CONN_01"))
    )
    (comp (ref "J263")
      (value "CONN_01")
      (footprint "eagle-import:1X01")
      (libsource (lib "eagle-import") (part "CONN_01"))
    )
    (comp (ref "J264")
      (value "CONN_01")
      (footprint "eagle-import:1X01")
      (libsource (lib "eagle-import") (part "CONN_01"))
    )
    (comp (ref "J265")
      (value "CONN_01")
      (footprint "eagle-import:1X01")
      (libsource (lib "eagle-import") (part "CONN_01"))
    )
    (comp (ref "J266")
      (value "CONN_01")
      (footprint "eagle-import:1X01")
      (libsource (lib "eagle-import") (part "CONN_01"))
    )
    (comp (ref "J267")
      (value "CONN_01")
      (footprint "eagle-import:1X01")
      (libsource (lib "eagle-import") (part "CONN_01"))
    )
    (comp (ref "J268")
      (value "CONN_01")
      (footprint "eagle-import:1X01")
      (libsource (lib "eagle-import") (part "CONN_01"))
    )
    (comp (ref "J269")
      (value "CONN_01")
      (footprint "eagle-import:1X01")
      (libsource (lib "eagle-import") (part "CONN_01"))
    )
    (comp (ref "J270")
      (value "CONN_01")
      (footprint "eagle-import:1X01")
      (libsource (lib "eagle-import") (part "CONN_01"))
    )
    (comp (ref "J271")
      (value "CONN_01")
      (footprint "eagle-import:1X01")
      (libsource (lib "eagle-import") (part "CONN_01"))
    )
    (comp (ref "J272")
      (value "CONN_01")
      (footprint "eagle-import:1X01")
      (libsource (lib "eagle-import") (part "CONN_01"))
    )
    (comp (ref "J273")
      (value "CONN_01")
      (footprint "eagle-import:1X01")
      (libsource (lib "eagle-import") (part "CONN_01"))
    )
    (comp (ref "J274")
      (value "CONN_01")
      (footprint "eagle-import:1X01")
      (libsource (lib "eagle-import") (part "CONN_01"))
    )
    (comp (ref "J275")
      (value "CONN_01")
      (footprint "eagle-import:1X01")
      (libsource (lib "eagle-import") (part "CONN_01"))
    )
    (comp (ref "J276")
      (value "CONN_01")
      (footprint "eagle-import:1X01")
      (libsource (lib "eagle-import") (part "CONN_01"))
    )
    (comp (ref "J277")
      (value "CONN_01")
      (footprint "eagle-import:1X01")
      (libsource (lib "eagle-import") (part "CONN_01"))
    )
    (comp (ref "J278")
      (value "CONN_01")
      (footprint "eagle-import:1X01")
      (libsource (lib "eagle-import") (part "CONN_01"))
    )
    (comp (ref "J279")
      (value "CONN_01")
      (footprint "eagle-import:1X01")
      (libsource (lib "eagle-import") (part "CONN_01"))
    )
    (comp (ref "J280")
      (value "CONN_01")
      (footprint "eagle-import:1X01")
      (libsource (lib "eagle-import") (part "CONN_01"))
    )
    (comp (ref "J281")
      (value "CONN_01")
      (footprint "eagle-import:1X01")
      (libsource (lib "eagle-import") (part "CONN_01"))
    )
    (comp (ref "J282")
      (value "CONN_01")
      (footprint "eagle-import:1X01")
      (libsource (lib "eagle-import") (part "CONN_01"))
    )
    (comp (ref "J283")
      (value "CONN_01")
      (footprint "eagle-import:1X01")
      (libsource (lib "eagle-import") (part "CONN_01"))
    )
    (comp (ref "J284")
      (value "CONN_01")
      (footprint "eagle-import:1X01")
      (libsource (lib "eagle-import") (part "CONN_01"))
    )
    (comp (ref "J285")
      (value "CONN_01")
      (footprint "eagle-import:1X01")
      (libsource (lib "eagle-import") (part "CONN_01"))
    )
    (comp (ref "J286")
      (value "CONN_01")
      (footprint "eagle-import:1X01")
      (libsource (lib "eagle-import") (part "CONN_01"))
    )
    (comp (ref "J287")
      (value "CONN_01")
      (footprint "eagle-import:1X01")
      (libsource (lib "eagle-import") (part "CONN_01"))
    )
    (comp (ref "J288")
      (value "CONN_01")
      (footprint "eagle-import:1X01")
      (libsource (lib "eagle-import") (part "CONN_01"))
    )
    (comp (ref "J289")
      (value "CONN_01")
      (footprint "eagle-import:1X01")
      (libsource (lib "eagle-import") (part "CONN_01"))
    )
    (comp (ref "J290")
      (value "CONN_01")
      (footprint "eagle-import:1X01")
      (libsource (lib "eagle-import") (part "CONN_01"))
    )
    (comp (ref "J291")
      (value "CONN_01")
      (footprint "eagle-import:1X01")
      (libsource (lib "eagle-import") (part "CONN_01"))
    )
    (comp (ref "J292")
      (value "CONN_01")
      (footprint "eagle-import:1X01")
      (libsource (lib "eagle-import") (part "CONN_01"))
    )
    (comp (ref "J293")
      (value "CONN_01")
      (footprint "eagle-import:1X01")
      (libsource (lib "eagle-import") (part "CONN_01"))
    )
    (comp (ref "J294")
      (value "CONN_01")
      (footprint "eagle-import:1X01")
      (libsource (lib "eagle-import") (part "CONN_01"))
    )
    (comp (ref "J295")
      (value "CONN_01")
      (footprint "eagle-import:1X01")
      (libsource (lib "eagle-import") (part "CONN_01"))
    )
    (comp (ref "J296")
      (value "CONN_01")
      (footprint "eagle-import:1X01")
      (libsource (lib "eagle-import") (part "CONN_01"))
    )
    (comp (ref "J297")
      (value "CONN_01")
      (footprint "eagle-import:1X01")
      (libsource (lib "eagle-import") (part "CONN_01"))
    )
    (comp (ref "J298")
      (value "CONN_01")
      (footprint "eagle-import:1X01")
      (libsource (lib "eagle-import") (part "CONN_01"))
    )
    (comp (ref "J299")
      (value "CONN_01")
      (footprint "eagle-import:1X01")
      (libsource (lib "eagle-import") (part "CONN_01"))
    )
    (comp (ref "J300")
      (value "CONN_01")
      (footprint "eagle-import:1X01")
      (libsource (lib "eagle-import") (part "CONN_01"))
    )
    (comp (ref "J301")
      (value "CONN_01")
      (footprint "eagle-import:1X01")
      (libsource (lib "eagle-import") (part "CONN_01"))
    )
    (comp (ref "J302")
      (value "CONN_01")
      (footprint "eagle-import:1X01")
      (libsource (lib "eagle-import") (part "CONN_01"))
    )
    (comp (ref "J303")
      (value "CONN_01")
      (footprint "eagle-import:1X01")
      (libsource (lib "eagle-import") (part "CONN_01"))
    )
    (comp (ref "J304")
      (value "CONN_01")
      (footprint "eagle-import:1X01")
      (libsource (lib "eagle-import") (part "CONN_01"))
    )
    (comp (ref "J305")
      (value "CONN_01")
      (footprint "eagle-import:1X01")
      (libsource (lib "eagle-import") (part "CONN_01"))
    )
    (comp (ref "J306")
      (value "CONN_01")
      (footprint "eagle-import:1X01")
      (libsource (lib "eagle-import") (part "CONN_01"))
    )
    (comp (ref "J307")
      (value "CONN_01")
      (footprint "eagle-import:1X01")
      (libsource (lib "eagle-import") (part "CONN_01"))
    )
    (comp (ref "J308")
      (value "CONN_01")
      (footprint "eagle-import:1X01")
      (libsource (lib "eagle-import") (part "CONN_01"))
    )
    (comp (ref "J309")
      (value "CONN_01")
      (footprint "eagle-import:1X01")
      (libsource (lib "eagle-import") (part "CONN_01"))
    )
    (comp (ref "J310")
      (value "CONN_01")
      (footprint "eagle-import:1X01")
      (libsource (lib "eagle-import") (part "CONN_01"))
    )
    (comp (ref "J311")
      (value "CONN_01")
      (footprint "eagle-import:1X01")
      (libsource (lib "eagle-import") (part "CONN_01"))
    )
    (comp (ref "J312")
      (value "CONN_01")
      (footprint "eagle-import:1X01")
      (libsource (lib "eagle-import") (part "CONN_01"))
    )
    (comp (ref "J313")
      (value "CONN_01")
      (footprint "eagle-import:1X01")
      (libsource (lib "eagle-import") (part "CONN_01"))
    )
    (comp (ref "J314")
      (value "CONN_01")
      (footprint "eagle-import:1X01")
      (libsource (lib "eagle-import") (part "CONN_01"))
    )
    (comp (ref "J315")
      (value "CONN_01")
      (footprint "eagle-import:1X01")
      (libsource (lib "eagle-import") (part "CONN_01"))
    )
    (comp (ref "J316")
      (value "CONN_01")
      (footprint "eagle-import:1X01")
      (libsource (lib "eagle-import") (part "CONN_01"))
    )
    (comp (ref "J317")
      (value "CONN_01")
      (footprint "eagle-import:1X01")
      (libsource (lib "eagle-import") (part "CONN_01"))
    )
    (comp (ref "J318")
      (value "CONN_01")
      (footprint "eagle-import:1X01")
      (libsource (lib "eagle-import") (part "CONN_01"))
    )
    (comp (ref "J319")
      (value "CONN_01")
      (footprint "eagle-import:1X01")
      (libsource (lib "eagle-import") (part "CONN_01"))
    )
    (comp (ref "J320")
      (value "CONN_01")
      (footprint "eagle-import:1X01")
      (libsource (lib "eagle-import") (part "CONN_01"))
    )
    (comp (ref "J321")
      (value "CONN_01")
      (footprint "eagle-import:1X01")
      (libsource (lib "eagle-import") (part "CONN_01"))
    )
    (comp (ref "J322")
      (value "CONN_01")
      (footprint "eagle-import:1X01")
      (libsource (lib "eagle-import") (part "CONN_01"))
    )
    (comp (ref "J323")
      (value "CONN_01")
      (footprint "eagle-import:1X01")
      (libsource (lib "eagle-import") (part "CONN_01"))
    )
    (comp (ref "J324")
      (value "CONN_01")
      (footprint "eagle-import:1X01")
      (libsource (lib "eagle-import") (part "CONN_01"))
    )
    (comp (ref "J325")
      (value "CONN_01")
      (footprint "eagle-import:1X01")
      (libsource (lib "eagle-import") (part "CONN_01"))
    )
    (comp (ref "J326")
      (value "CONN_01")
      (footprint "eagle-import:1X01")
      (libsource (lib "eagle-import") (part "CONN_01"))
    )
    (comp (ref "J327")
      (value "CONN_01")
      (footprint "eagle-import:1X01")
      (libsource (lib "eagle-import") (part "CONN_01"))
    )
    (comp (ref "J328")
      (value "CONN_01")
      (footprint "eagle-import:1X01")
      (libsource (lib "eagle-import") (part "CONN_01"))
    )
    (comp (ref "J329")
      (value "CONN_01")
      (footprint "eagle-import:1X01")
      (libsource (lib "eagle-import") (part "CONN_01"))
    )
    (comp (ref "J330")
      (value "CONN_01")
      (footprint "eagle-import:1X01")
      (libsource (lib "eagle-import") (part "CONN_01"))
    )
    (comp (ref "J331")
      (value "CONN_01")
      (footprint "eagle-import:1X01")
      (libsource (lib "eagle-import") (part "CONN_01"))
    )
    (comp (ref "J332")
      (value "CONN_01")
      (footprint "eagle-import:1X01")
      (libsource (lib "eagle-import") (part "CONN_01"))
    )
    (comp (ref "J333")
      (value "CONN_01")
      (footprint "eagle-import:1X01")
      (libsource (lib "eagle-import") (part "CONN_01"))
    )
    (comp (ref "J334")
      (value "CONN_01")
      (footprint "eagle-import:1X01")
      (libsource (lib "eagle-import") (part "CONN_01"))
    )
    (comp (ref "J335")
      (value "CONN_01")
      (footprint "eagle-import:1X01")
      (libsource (lib "eagle-import") (part "CONN_01"))
    )
    (comp (ref "J336")
      (value "CONN_01")
      (footprint "eagle-import:1X01")
      (libsource (lib "eagle-import") (part "CONN_01"))
    )
    (comp (ref "J337")
      (value "CONN_01")
      (footprint "eagle-import:1X01")
      (libsource (lib "eagle-import") (part "CONN_01"))
    )
    (comp (ref "J338")
      (value "CONN_01")
      (footprint "eagle-import:1X01")
      (libsource (lib "eagle-import") (part "CONN_01"))
    )
    (comp (ref "J339")
      (value "CONN_01")
      (footprint "eagle-import:1X01")
      (libsource (lib "eagle-import") (part "CONN_01"))
    )
    (comp (ref "J340")
      (value "CONN_01")
      (footprint "eagle-import:1X01")
      (libsource (lib "eagle-import") (part "CONN_01"))
    )
    (comp (ref "J341")
      (value "CONN_01")
      (footprint "eagle-import:1X01")
      (libsource (lib "eagle-import") (part "CONN_01"))
    )
    (comp (ref "J342")
      (value "CONN_01")
      (footprint "eagle-import:1X01")
      (libsource (lib "eagle-import") (part "CONN_01"))
    )
    (comp (ref "J343")
      (value "CONN_01")
      (footprint "eagle-import:1X01")
      (libsource (lib "eagle-import") (part "CONN_01"))
    )
    (comp (ref "J344")
      (value "CONN_01")
      (footprint "eagle-import:1X01")
      (libsource (lib "eagle-import") (part "CONN_01"))
    )
    (comp (ref "J345")
      (value "CONN_01")
      (footprint "eagle-import:1X01")
      (libsource (lib "eagle-import") (part "CONN_01"))
    )
    (comp (ref "J346")
      (value "CONN_01")
      (footprint "eagle-import:1X01")
      (libsource (lib "eagle-import") (part "CONN_01"))
    )
    (comp (ref "J347")
      (value "CONN_01")
      (footprint "eagle-import:1X01")
      (libsource (lib "eagle-import") (part "CONN_01"))
    )
    (comp (ref "J348")
      (value "CONN_01")
      (footprint "eagle-import:1X01")
      (libsource (lib "eagle-import") (part "CONN_01"))
    )
    (comp (ref "J349")
      (value "CONN_01")
      (footprint "eagle-import:1X01")
      (libsource (lib "eagle-import") (part "CONN_01"))
    )
    (comp (ref "J350")
      (value "CONN_01")
      (footprint "eagle-import:1X01")
      (libsource (lib "eagle-import") (part "CONN_01"))
    )
    (comp (ref "J351")
      (value "CONN_01")
      (footprint "eagle-import:1X01")
      (libsource (lib "eagle-import") (part "CONN_01"))
    )
    (comp (ref "J352")
      (value "CONN_01")
      (footprint "eagle-import:1X01")
      (libsource (lib "eagle-import") (part "CONN_01"))
    )
    (comp (ref "J353")
      (value "CONN_01")
      (footprint "eagle-import:1X01")
      (libsource (lib "eagle-import") (part "CONN_01"))
    )
    (comp (ref "J354")
      (value "CONN_01")
      (footprint "eagle-import:1X01")
      (libsource (lib "eagle-import") (part "CONN_01"))
    )
    (comp (ref "J355")
      (value "CONN_01")
      (footprint "eagle-import:1X01")
      (libsource (lib "eagle-import") (part "CONN_01"))
    )
    (comp (ref "J356")
      (value "CONN_01")
      (footprint "eagle-import:1X01")
      (libsource (lib "eagle-import") (part "CONN_01"))
    )
    (comp (ref "J357")
      (value "CONN_01")
      (footprint "eagle-import:1X01")
      (libsource (lib "eagle-import") (part "CONN_01"))
    )
    (comp (ref "J358")
      (value "CONN_01")
      (footprint "eagle-import:1X01")
      (libsource (lib "eagle-import") (part "CONN_01"))
    )
    (comp (ref "J359")
      (value "CONN_01")
      (footprint "eagle-import:1X01")
      (libsource (lib "eagle-import") (part "CONN_01"))
    )
    (comp (ref "J360")
      (value "CONN_01")
      (footprint "eagle-import:1X01")
      (libsource (lib "eagle-import") (part "CONN_01"))
    )
    (comp (ref "J361")
      (value "CONN_01")
      (footprint "eagle-import:1X01")
      (libsource (lib "eagle-import") (part "CONN_01"))
    )
    (comp (ref "J362")
      (value "CONN_01")
      (footprint "eagle-import:1X01")
      (libsource (lib "eagle-import") (part "CONN_01"))
    )
    (comp (ref "J363")
      (value "CONN_01")
      (footprint "eagle-import:1X01")
      (libsource (lib "eagle-import") (part "CONN_01"))
    )
    (comp (ref "J364")
      (value "CONN_01")
      (footprint "eagle-import:1X01")
      (libsource (lib "eagle-import") (part "CONN_01"))
    )
    (comp (ref "J365")
      (value "CONN_01")
      (footprint "eagle-import:1X01")
      (libsource (lib "eagle-import") (part "CONN_01"))
    )
    (comp (ref "J366")
      (value "CONN_01")
      (footprint "eagle-import:1X01")
      (libsource (lib "eagle-import") (part "CONN_01"))
    )
    (comp (ref "J367")
      (value "CONN_01")
      (footprint "eagle-import:1X01")
      (libsource (lib "eagle-import") (part "CONN_01"))
    )
    (comp (ref "J368")
      (value "CONN_01")
      (footprint "eagle-import:1X01")
      (libsource (lib "eagle-import") (part "CONN_01"))
    )
    (comp (ref "J369")
      (value "CONN_01")
      (footprint "eagle-import:1X01")
      (libsource (lib "eagle-import") (part "CONN_01"))
    )
    (comp (ref "J370")
      (value "CONN_01")
      (footprint "eagle-import:1X01")
      (libsource (lib "eagle-import") (part "CONN_01"))
    )
    (comp (ref "J371")
      (value "CONN_01")
      (footprint "eagle-import:1X01")
      (libsource (lib "eagle-import") (part "CONN_01"))
    )
    (comp (ref "J372")
      (value "CONN_01")
      (footprint "eagle-import:1X01")
      (libsource (lib "eagle-import") (part "CONN_01"))
    )
    (comp (ref "J373")
      (value "CONN_01")
      (footprint "eagle-import:1X01")
      (libsource (lib "eagle-import") (part "CONN_01"))
    )
    (comp (ref "J374")
      (value "CONN_01")
      (footprint "eagle-import:1X01")
      (libsource (lib "eagle-import") (part "CONN_01"))
    )
    (comp (ref "J375")
      (value "CONN_01")
      (footprint "eagle-import:1X01")
      (libsource (lib "eagle-import") (part "CONN_01"))
    )
    (comp (ref "J376")
      (value "CONN_01")
      (footprint "eagle-import:1X01")
      (libsource (lib "eagle-import") (part "CONN_01"))
    )
    (comp (ref "J377")
      (value "CONN_01")
      (footprint "eagle-import:1X01")
      (libsource (lib "eagle-import") (part "CONN_01"))
    )
    (comp (ref "J378")
      (value "CONN_01")
      (footprint "eagle-import:1X01")
      (libsource (lib "eagle-import") (part "CONN_01"))
    )
    (comp (ref "J379")
      (value "CONN_01")
      (footprint "eagle-import:1X01")
      (libsource (lib "eagle-import") (part "CONN_01"))
    )
    (comp (ref "J380")
      (value "CONN_01")
      (footprint "eagle-import:1X01")
      (libsource (lib "eagle-import") (part "CONN_01"))
    )
    (comp (ref "J381")
      (value "CONN_01")
      (footprint "eagle-import:1X01")
      (libsource (lib "eagle-import") (part "CONN_01"))
    )
    (comp (ref "J382")
      (value "CONN_01")
      (footprint "eagle-import:1X01")
      (libsource (lib "eagle-import") (part "CONN_01"))
    )
    (comp (ref "J383")
      (value "CONN_01")
      (footprint "eagle-import:1X01")
      (libsource (lib "eagle-import") (part "CONN_01"))
    )
    (comp (ref "J384")
      (value "CONN_01")
      (footprint "eagle-import:1X01")
      (libsource (lib "eagle-import") (part "CONN_01"))
    )
    (comp (ref "J385")
      (value "CONN_01")
      (footprint "eagle-import:1X01")
      (libsource (lib "eagle-import") (part "CONN_01"))
    )
    (comp (ref "J386")
      (value "CONN_01")
      (footprint "eagle-import:1X01")
      (libsource (lib "eagle-import") (part "CONN_01"))
    )
    (comp (ref "J387")
      (value "CONN_01")
      (footprint "eagle-import:1X01")
      (libsource (lib "eagle-import") (part "CONN_01"))
    )
    (comp (ref "J388")
      (value "CONN_01")
      (footprint "eagle-import:1X01")
      (libsource (lib "eagle-import") (part "CONN_01"))
    )
    (comp (ref "J389")
      (value "CONN_01")
      (footprint "eagle-import:1X01")
      (libsource (lib "eagle-import") (part "CONN_01"))
    )
    (comp (ref "J390")
      (value "CONN_01")
      (footprint "eagle-import:1X01")
      (libsource (lib "eagle-import") (part "CONN_01"))
    )
    (comp (ref "J391")
      (value "CONN_01")
      (footprint "eagle-import:1X01")
      (libsource (lib "eagle-import") (part "CONN_01"))
    )
  )
  (nets
    (net (code "1") (name "3.3V") (class "Default")
      (node (ref "J10") (pin "1") (pinfunction "1_1") (pintype "passive"))
      (node (ref "J23") (pin "1") (pinfunction "1_1") (pintype "passive"))
      (node (ref "J3") (pin "11") (pinfunction "11_11") (pintype "passive"))
      (node (ref "Q1") (pin "1") (pinfunction "G_1") (pintype "bidirectional"))
      (node (ref "Q2") (pin "1") (pinfunction "G_1") (pintype "bidirectional"))
      (node (ref "R14") (pin "2") (pinfunction "2_2") (pintype "passive"))
      (node (ref "R18") (pin "2") (pinfunction "2_2") (pintype "passive"))
      (node (ref "WEMOS1") (pin "3V3") (pinfunction "3V3_3V3") (pintype "bidirectional"))
    )
    (net (code "2") (name "3SCL") (class "Default")
      (node (ref "J26") (pin "1") (pinfunction "1_1") (pintype "passive"))
      (node (ref "J3") (pin "2") (pinfunction "2_2") (pintype "passive"))
      (node (ref "J4") (pin "1") (pinfunction "1_1") (pintype "passive"))
      (node (ref "Q1") (pin "2") (pinfunction "S_2") (pintype "bidirectional"))
      (node (ref "R14") (pin "1") (pinfunction "1_1") (pintype "passive"))
      (node (ref "WEMOS1") (pin "D1") (pinfunction "D1_D1") (pintype "bidirectional"))
    )
    (net (code "3") (name "3SDA") (class "Default")
      (node (ref "J15") (pin "1") (pinfunction "1_1") (pintype "passive"))
      (node (ref "J27") (pin "1") (pinfunction "1_1") (pintype "passive"))
      (node (ref "J3") (pin "1") (pinfunction "1_1") (pintype "passive"))
      (node (ref "Q2") (pin "2") (pinfunction "S_2") (pintype "bidirectional"))
      (node (ref "R18") (pin "1") (pinfunction "1_1") (pintype "passive"))
      (node (ref "WEMOS1") (pin "D2") (pinfunction "D2_D2") (pintype "bidirectional"))
    )
    (net (code "4") (name "A0") (class "Default")
      (node (ref "IC12") (pin "3") (pinfunction "A2_3") (pintype "bidirectional"))
      (node (ref "IC15") (pin "2") (pinfunction "A1_2") (pintype "bidirectional"))
      (node (ref "IC18") (pin "3") (pinfunction "A2_3") (pintype "bidirectional"))
      (node (ref "IC24") (pin "3") (pinfunction "A2_3") (pintype "bidirectional"))
      (node (ref "IC6") (pin "3") (pinfunction "A2_3") (pintype "bidirectional"))
      (node (ref "IC9") (pin "2") (pinfunction "A1_2") (pintype "bidirectional"))
      (node (ref "R5") (pin "1") (pinfunction "1_1") (pintype "passive"))
      (node (ref "S1") (pin "6") (pinfunction "6_6") (pintype "passive"))
    )
    (net (code "5") (name "A1") (class "Default")
      (node (ref "IC12") (pin "4") (pinfunction "A3_4") (pintype "bidirectional"))
      (node (ref "IC15") (pin "3") (pinfunction "A2_3") (pintype "bidirectional"))
      (node (ref "IC18") (pin "4") (pinfunction "A3_4") (pintype "bidirectional"))
      (node (ref "IC24") (pin "4") (pinfunction "A3_4") (pintype "bidirectional"))
      (node (ref "IC6") (pin "4") (pinfunction "A3_4") (pintype "bidirectional"))
      (node (ref "IC9") (pin "3") (pinfunction "A2_3") (pintype "bidirectional"))
      (node (ref "R6") (pin "1") (pinfunction "1_1") (pintype "passive"))
      (node (ref "S1") (pin "5") (pinfunction "5_5") (pintype "passive"))
    )
    (net (code "6") (name "A2") (class "Default")
      (node (ref "IC12") (pin "5") (pinfunction "A4_5") (pintype "bidirectional"))
      (node (ref "IC15") (pin "4") (pinfunction "A3_4") (pintype "bidirectional"))
      (node (ref "IC18") (pin "5") (pinfunction "A4_5") (pintype "bidirectional"))
      (node (ref "IC24") (pin "5") (pinfunction "A4_5") (pintype "bidirectional"))
      (node (ref "IC6") (pin "5") (pinfunction "A4_5") (pintype "bidirectional"))
      (node (ref "IC9") (pin "4") (pinfunction "A3_4") (pintype "bidirectional"))
      (node (ref "R13") (pin "1") (pinfunction "1_1") (pintype "passive"))
      (node (ref "S1") (pin "4") (pinfunction "4_4") (pintype "passive"))
    )
    (net (code "7") (name "B_IO0") (class "Default")
      (node (ref "J3") (pin "8") (pinfunction "8_8") (pintype "passive"))
      (node (ref "J7") (pin "1") (pinfunction "1_1") (pintype "passive"))
    )
    (net (code "8") (name "B_IO1") (class "Default")
      (node (ref "J3") (pin "6") (pinfunction "6_6") (pintype "passive"))
      (node (ref "J6") (pin "1") (pinfunction "1_1") (pintype "passive"))
    )
    (net (code "9") (name "B_IO2") (class "Default")
      (node (ref "J3") (pin "4") (pinfunction "4_4") (pintype "passive"))
      (node (ref "J5") (pin "1") (pinfunction "1_1") (pintype "passive"))
    )
    (net (code "10") (name "B_IO3") (class "Default")
      (node (ref "J12") (pin "1") (pinfunction "1_1") (pintype "passive"))
      (node (ref "J3") (pin "7") (pinfunction "7_7") (pintype "passive"))
    )
    (net (code "11") (name "B_IO4") (class "Default")
      (node (ref "J13") (pin "1") (pinfunction "1_1") (pintype "passive"))
      (node (ref "J3") (pin "5") (pinfunction "5_5") (pintype "passive"))
    )
    (net (code "12") (name "GND") (class "Default")
      (node (ref "ARDUINO_NANO") (pin "14") (pinfunction "GND_14") (pintype "power_in"))
      (node (ref "ARDUINO_NANO") (pin "19") (pinfunction "GND_19") (pintype "power_in"))
      (node (ref "C1") (pin "2") (pinfunction "2_2") (pintype "passive"))
      (node (ref "C10") (pin "-") (pinfunction "-_-") (pintype "passive"))
      (node (ref "C11") (pin "2") (pinfunction "2_2") (pintype "passive"))
      (node (ref "C12") (pin "-") (pinfunction "-_-") (pintype "passive"))
      (node (ref "C13") (pin "2") (pinfunction "2_2") (pintype "passive"))
      (node (ref "C14") (pin "-") (pinfunction "-_-") (pintype "passive"))
      (node (ref "C15") (pin "2") (pinfunction "2_2") (pintype "passive"))
      (node (ref "C16") (pin "-") (pinfunction "-_-") (pintype "passive"))
      (node (ref "C2") (pin "-") (pinfunction "-_-") (pintype "passive"))
      (node (ref "C3") (pin "2") (pinfunction "2_2") (pintype "passive"))
      (node (ref "C4") (pin "-") (pinfunction "-_-") (pintype "passive"))
      (node (ref "C5") (pin "2") (pinfunction "2_2") (pintype "passive"))
      (node (ref "C6") (pin "-") (pinfunction "-_-") (pintype "passive"))
      (node (ref "C7") (pin "2") (pinfunction "2_2") (pintype "passive"))
      (node (ref "C8") (pin "-") (pinfunction "-_-") (pintype "passive"))
      (node (ref "C9") (pin "2") (pinfunction "2_2") (pintype "passive"))
      (node (ref "IC10") (pin "10") (pinfunction "GND_10") (pintype "power_in"))
      (node (ref "IC11") (pin "9") (pinfunction "9_9") (pintype "bidirectional"))
      (node (ref "IC12") (pin "14") (pinfunction "VSS_14") (pintype "bidirectional"))
      (node (ref "IC12") (pin "2") (pinfunction "A1_2") (pintype "bidirectional"))
      (node (ref "IC12") (pin "23") (pinfunction "~{OE}_23") (pintype "bidirectional"))
      (node (ref "IC12") (pin "24") (pinfunction "A5_24") (pintype "bidirectional"))
      (node (ref "IC12") (pin "25") (pinfunction "EXTCLK_25") (pintype "bidirectional"))
      (node (ref "IC13") (pin "10") (pinfunction "GND_10") (pintype "power_in"))
      (node (ref "IC14") (pin "9") (pinfunction "9_9") (pintype "bidirectional"))
      (node (ref "IC15") (pin "1") (pinfunction "A0_1") (pintype "bidirectional"))
      (node (ref "IC15") (pin "14") (pinfunction "VSS_14") (pintype "bidirectional"))
      (node (ref "IC15") (pin "23") (pinfunction "~{OE}_23") (pintype "bidirectional"))
      (node (ref "IC15") (pin "25") (pinfunction "EXTCLK_25") (pintype "bidirectional"))
      (node (ref "IC15") (pin "5") (pinfunction "A4_5") (pintype "bidirectional"))
      (node (ref "IC16") (pin "10") (pinfunction "GND_10") (pintype "power_in"))
      (node (ref "IC17") (pin "9") (pinfunction "9_9") (pintype "bidirectional"))
      (node (ref "IC18") (pin "1") (pinfunction "A0_1") (pintype "bidirectional"))
      (node (ref "IC18") (pin "14") (pinfunction "VSS_14") (pintype "bidirectional"))
      (node (ref "IC18") (pin "23") (pinfunction "~{OE}_23") (pintype "bidirectional"))
      (node (ref "IC18") (pin "24") (pinfunction "A5_24") (pintype "bidirectional"))
      (node (ref "IC18") (pin "25") (pinfunction "EXTCLK_25") (pintype "bidirectional"))
      (node (ref "IC22") (pin "10") (pinfunction "GND_10") (pintype "power_in"))
      (node (ref "IC23") (pin "9") (pinfunction "9_9") (pintype "bidirectional"))
      (node (ref "IC24") (pin "14") (pinfunction "VSS_14") (pintype "bidirectional"))
      (node (ref "IC24") (pin "23") (pinfunction "~{OE}_23") (pintype "bidirectional"))
      (node (ref "IC24") (pin "24") (pinfunction "A5_24") (pintype "bidirectional"))
      (node (ref "IC24") (pin "25") (pinfunction "EXTCLK_25") (pintype "bidirectional"))
      (node (ref "IC4") (pin "10") (pinfunction "GND_10") (pintype "power_in"))
      (node (ref "IC5") (pin "9") (pinfunction "9_9") (pintype "bidirectional"))
      (node (ref "IC6") (pin "1") (pinfunction "A0_1") (pintype "bidirectional"))
      (node (ref "IC6") (pin "14") (pinfunction "VSS_14") (pintype "bidirectional"))
      (node (ref "IC6") (pin "2") (pinfunction "A1_2") (pintype "bidirectional"))
      (node (ref "IC6") (pin "23") (pinfunction "~{OE}_23") (pintype "bidirectional"))
      (node (ref "IC6") (pin "24") (pinfunction "A5_24") (pintype "bidirectional"))
      (node (ref "IC6") (pin "25") (pinfunction "EXTCLK_25") (pintype "bidirectional"))
      (node (ref "IC7") (pin "10") (pinfunction "GND_10") (pintype "power_in"))
      (node (ref "IC8") (pin "9") (pinfunction "9_9") (pintype "bidirectional"))
      (node (ref "IC9") (pin "14") (pinfunction "VSS_14") (pintype "bidirectional"))
      (node (ref "IC9") (pin "23") (pinfunction "~{OE}_23") (pintype "bidirectional"))
      (node (ref "IC9") (pin "25") (pinfunction "EXTCLK_25") (pintype "bidirectional"))
      (node (ref "IC9") (pin "5") (pinfunction "A4_5") (pintype "bidirectional"))
      (node (ref "J1") (pin "3") (pinfunction "3_3") (pintype "passive"))
      (node (ref "J11") (pin "1") (pinfunction "1_1") (pintype "passive"))
      (node (ref "J2") (pin "3") (pinfunction "3_3") (pintype "passive"))
      (node (ref "J3") (pin "12") (pinfunction "12_12") (pintype "passive"))
      (node (ref "J3") (pin "9") (pinfunction "9_9") (pintype "passive"))
      (node (ref "J30") (pin "1") (pinfunction "1_1") (pintype "passive"))
      (node (ref "J56") (pin "1") (pinfunction "1_1") (pintype "passive"))
      (node (ref "J9") (pin "1") (pinfunction "1_1") (pintype "passive"))
      (node (ref "R20") (pin "2") (pinfunction "2_2") (pintype "passive"))
      (node (ref "S1") (pin "1") (pinfunction "1_1") (pintype "passive"))
      (node (ref "S1") (pin "2") (pinfunction "2_2") (pintype "passive"))
      (node (ref "S1") (pin "3") (pinfunction "3_3") (pintype "passive"))
      (node (ref "U$1") (pin "3") (pinfunction "GI_3") (pintype "power_in"))
      (node (ref "U$1") (pin "4") (pinfunction "GO_4") (pintype "power_in"))
      (node (ref "WEMOS1") (pin "GND") (pinfunction "GND_GND") (pintype "bidirectional"))
      (node (ref "X4") (pin "2") (pinfunction "1_2") (pintype "passive"))
      (node (ref "X5") (pin "2") (pinfunction "1_2") (pintype "passive"))
    )
    (net (code "13") (name "HIGHVOLTAGE") (class "Default")
      (node (ref "C1") (pin "1") (pinfunction "1_1") (pintype "passive"))
      (node (ref "C10") (pin "+") (pinfunction "+_+") (pintype "passive"))
      (node (ref "C12") (pin "+") (pinfunction "+_+") (pintype "passive"))
      (node (ref "C14") (pin "+") (pinfunction "+_+") (pintype "passive"))
      (node (ref "C16") (pin "+") (pinfunction "+_+") (pintype "passive"))
      (node (ref "C4") (pin "+") (pinfunction "+_+") (pintype "passive"))
      (node (ref "C6") (pin "+") (pinfunction "+_+") (pintype "passive"))
      (node (ref "C8") (pin "+") (pinfunction "+_+") (pintype "passive"))
      (node (ref "IC10") (pin "9") (pinfunction "VS_9") (pintype "passive"))
      (node (ref "IC13") (pin "9") (pinfunction "VS_9") (pintype "passive"))
      (node (ref "IC16") (pin "9") (pinfunction "VS_9") (pintype "passive"))
      (node (ref "IC22") (pin "9") (pinfunction "VS_9") (pintype "passive"))
      (node (ref "IC4") (pin "9") (pinfunction "VS_9") (pintype "passive"))
      (node (ref "IC7") (pin "9") (pinfunction "VS_9") (pintype "passive"))
      (node (ref "U$1") (pin "2") (pinfunction "IN_2") (pintype "bidirectional"))
      (node (ref "X4") (pin "1") (pinfunction "1_1") (pintype "passive"))
      (node (ref "X5") (pin "1") (pinfunction "1_1") (pintype "passive"))
    )
    (net (code "14") (name "Net-(ARDUINO_NANO-3V3)") (class "Default")
      (node (ref "ARDUINO_NANO") (pin "2") (pinfunction "3V3_2") (pintype "output"))
      (node (ref "J75") (pin "1") (pinfunction "1_1") (pintype "passive"))
    )
    (net (code "15") (name "Net-(ARDUINO_NANO-A0)") (class "Default")
      (node (ref "ARDUINO_NANO") (pin "4") (pinfunction "A0_4") (pintype "bidirectional"))
      (node (ref "J77") (pin "1") (pinfunction "1_1") (pintype "passive"))
    )
    (net (code "16") (name "Net-(ARDUINO_NANO-A1)") (class "Default")
      (node (ref "ARDUINO_NANO") (pin "5") (pinfunction "A1_5") (pintype "bidirectional"))
      (node (ref "J78") (pin "1") (pinfunction "1_1") (pintype "passive"))
    )
    (net (code "17") (name "Net-(ARDUINO_NANO-A2)") (class "Default")
      (node (ref "ARDUINO_NANO") (pin "6") (pinfunction "A2_6") (pintype "bidirectional"))
      (node (ref "J79") (pin "1") (pinfunction "1_1") (pintype "passive"))
    )
    (net (code "18") (name "Net-(ARDUINO_NANO-A3)") (class "Default")
      (node (ref "ARDUINO_NANO") (pin "7") (pinfunction "A3_7") (pintype "bidirectional"))
      (node (ref "J80") (pin "1") (pinfunction "1_1") (pintype "passive"))
    )
    (net (code "19") (name "Net-(ARDUINO_NANO-A6)") (class "Default")
      (node (ref "ARDUINO_NANO") (pin "10") (pinfunction "A6_10") (pintype "bidirectional"))
      (node (ref "J83") (pin "1") (pinfunction "1_1") (pintype "passive"))
    )
    (net (code "20") (name "Net-(ARDUINO_NANO-A7)") (class "Default")
      (node (ref "ARDUINO_NANO") (pin "11") (pinfunction "A7_11") (pintype "bidirectional"))
      (node (ref "J84") (pin "1") (pinfunction "1_1") (pintype "passive"))
    )
    (net (code "21") (name "Net-(ARDUINO_NANO-AREF)") (class "Default")
      (node (ref "ARDUINO_NANO") (pin "3") (pinfunction "AREF_3") (pintype "input"))
      (node (ref "J76") (pin "1") (pinfunction "1_1") (pintype "passive"))
    )
    (net (code "22") (name "Net-(ARDUINO_NANO-D2)") (class "Default")
      (node (ref "ARDUINO_NANO") (pin "20") (pinfunction "D2_20") (pintype "bidirectional"))
      (node (ref "J63") (pin "1") (pinfunction "1_1") (pintype "passive"))
    )
    (net (code "23") (name "Net-(ARDUINO_NANO-D3)") (class "Default")
      (node (ref "ARDUINO_NANO") (pin "21") (pinfunction "D3_21") (pintype "bidirectional"))
      (node (ref "J64") (pin "1") (pinfunction "1_1") (pintype "passive"))
    )
    (net (code "24") (name "Net-(ARDUINO_NANO-D4)") (class "Default")
      (node (ref "ARDUINO_NANO") (pin "22") (pinfunction "D4_22") (pintype "bidirectional"))
      (node (ref "J65") (pin "1") (pinfunction "1_1") (pintype "passive"))
    )
    (net (code "25") (name "Net-(ARDUINO_NANO-D5)") (class "Default")
      (node (ref "ARDUINO_NANO") (pin "23") (pinfunction "D5_23") (pintype "bidirectional"))
      (node (ref "J66") (pin "1") (pinfunction "1_1") (pintype "passive"))
    )
    (net (code "26") (name "Net-(ARDUINO_NANO-D6)") (class "Default")
      (node (ref "ARDUINO_NANO") (pin "24") (pinfunction "D6_24") (pintype "bidirectional"))
      (node (ref "J67") (pin "1") (pinfunction "1_1") (pintype "passive"))
    )
    (net (code "27") (name "Net-(ARDUINO_NANO-D7)") (class "Default")
      (node (ref "ARDUINO_NANO") (pin "25") (pinfunction "D7_25") (pintype "bidirectional"))
      (node (ref "J68") (pin "1") (pinfunction "1_1") (pintype "passive"))
    )
    (net (code "28") (name "Net-(ARDUINO_NANO-D8)") (class "Default")
      (node (ref "ARDUINO_NANO") (pin "26") (pinfunction "D8_26") (pintype "bidirectional"))
      (node (ref "J69") (pin "1") (pinfunction "1_1") (pintype "passive"))
    )
    (net (code "29") (name "Net-(ARDUINO_NANO-D9)") (class "Default")
      (node (ref "ARDUINO_NANO") (pin "27") (pinfunction "D9_27") (pintype "bidirectional"))
      (node (ref "J70") (pin "1") (pinfunction "1_1") (pintype "passive"))
    )
    (net (code "30") (name "Net-(ARDUINO_NANO-D10)") (class "Default")
      (node (ref "ARDUINO_NANO") (pin "28") (pinfunction "D10_28") (pintype "bidirectional"))
      (node (ref "J71") (pin "1") (pinfunction "1_1") (pintype "passive"))
    )
    (net (code "31") (name "Net-(ARDUINO_NANO-D11)") (class "Default")
      (node (ref "ARDUINO_NANO") (pin "29") (pinfunction "D11_29") (pintype "bidirectional"))
      (node (ref "J72") (pin "1") (pinfunction "1_1") (pintype "passive"))
    )
    (net (code "32") (name "Net-(ARDUINO_NANO-D12)") (class "Default")
      (node (ref "ARDUINO_NANO") (pin "30") (pinfunction "D12_30") (pintype "bidirectional"))
      (node (ref "J73") (pin "1") (pinfunction "1_1") (pintype "passive"))
    )
    (net (code "33") (name "Net-(ARDUINO_NANO-D13)") (class "Default")
      (node (ref "ARDUINO_NANO") (pin "1") (pinfunction "D13_1") (pintype "bidirectional"))
      (node (ref "J74") (pin "1") (pinfunction "1_1") (pintype "passive"))
    )
    (net (code "34") (name "Net-(ARDUINO_NANO-~{RESET}-Pad13)") (class "Default")
      (node (ref "ARDUINO_NANO") (pin "13") (pinfunction "~{RESET}_13") (pintype "input"))
      (node (ref "J86") (pin "1") (pinfunction "1_1") (pintype "passive"))
    )
    (net (code "35") (name "Net-(IC4-I1)") (class "Default")
      (node (ref "IC4") (pin "1") (pinfunction "I1_1") (pintype "input"))
      (node (ref "IC6") (pin "22") (pinfunction "CH15_22") (pintype "bidirectional"))
    )
    (net (code "36") (name "Net-(IC4-I2)") (class "Default")
      (node (ref "IC4") (pin "2") (pinfunction "I2_2") (pintype "input"))
      (node (ref "IC6") (pin "21") (pinfunction "CH14_21") (pintype "bidirectional"))
    )
    (net (code "37") (name "Net-(IC4-I3)") (class "Default")
      (node (ref "IC4") (pin "3") (pinfunction "I3_3") (pintype "input"))
      (node (ref "IC6") (pin "20") (pinfunction "CH13_20") (pintype "bidirectional"))
    )
    (net (code "38") (name "Net-(IC4-I4)") (class "Default")
      (node (ref "IC4") (pin "4") (pinfunction "I4_4") (pintype "input"))
      (node (ref "IC6") (pin "19") (pinfunction "CH12_19") (pintype "bidirectional"))
    )
    (net (code "39") (name "Net-(IC4-I5)") (class "Default")
      (node (ref "IC4") (pin "5") (pinfunction "I5_5") (pintype "input"))
      (node (ref "IC6") (pin "18") (pinfunction "CH11_18") (pintype "bidirectional"))
    )
    (net (code "40") (name "Net-(IC4-I6)") (class "Default")
      (node (ref "IC4") (pin "6") (pinfunction "I6_6") (pintype "input"))
      (node (ref "IC6") (pin "17") (pinfunction "CH10_17") (pintype "bidirectional"))
    )
    (net (code "41") (name "Net-(IC4-I7)") (class "Default")
      (node (ref "IC4") (pin "7") (pinfunction "I7_7") (pintype "input"))
      (node (ref "IC6") (pin "16") (pinfunction "CH9_16") (pintype "bidirectional"))
    )
    (net (code "42") (name "Net-(IC4-I8)") (class "Default")
      (node (ref "IC4") (pin "8") (pinfunction "I8_8") (pintype "input"))
      (node (ref "IC6") (pin "15") (pinfunction "CH8_15") (pintype "bidirectional"))
    )
    (net (code "43") (name "Net-(IC4-O1)") (class "Default")
      (node (ref "IC4") (pin "18") (pinfunction "O1_18") (pintype "open_collector"))
      (node (ref "IC5") (pin "18") (pinfunction "18_18") (pintype "bidirectional"))
      (node (ref "X1") (pin "8") (pinfunction "KL_8") (pintype "passive"))
    )
    (net (code "44") (name "Net-(IC4-O2)") (class "Default")
      (node (ref "IC4") (pin "17") (pinfunction "O2_17") (pintype "open_collector"))
      (node (ref "IC5") (pin "17") (pinfunction "17_17") (pintype "bidirectional"))
      (node (ref "X1") (pin "7") (pinfunction "KL_7") (pintype "passive"))
    )
    (net (code "45") (name "Net-(IC4-O3)") (class "Default")
      (node (ref "IC4") (pin "16") (pinfunction "O3_16") (pintype "open_collector"))
      (node (ref "IC5") (pin "16") (pinfunction "16_16") (pintype "bidirectional"))
      (node (ref "X1") (pin "6") (pinfunction "KL_6") (pintype "passive"))
    )
    (net (code "46") (name "Net-(IC4-O4)") (class "Default")
      (node (ref "IC4") (pin "15") (pinfunction "O4_15") (pintype "open_collector"))
      (node (ref "IC5") (pin "15") (pinfunction "15_15") (pintype "bidirectional"))
      (node (ref "X1") (pin "5") (pinfunction "KL_5") (pintype "passive"))
    )
    (net (code "47") (name "Net-(IC4-O5)") (class "Default")
      (node (ref "IC4") (pin "14") (pinfunction "O5_14") (pintype "open_collector"))
      (node (ref "IC5") (pin "14") (pinfunction "14_14") (pintype "bidirectional"))
      (node (ref "X1") (pin "4") (pinfunction "KL_4") (pintype "passive"))
    )
    (net (code "48") (name "Net-(IC4-O6)") (class "Default")
      (node (ref "IC4") (pin "13") (pinfunction "O6_13") (pintype "open_collector"))
      (node (ref "IC5") (pin "13") (pinfunction "13_13") (pintype "bidirectional"))
      (node (ref "X1") (pin "3") (pinfunction "KL_3") (pintype "passive"))
    )
    (net (code "49") (name "Net-(IC4-O7)") (class "Default")
      (node (ref "IC4") (pin "12") (pinfunction "O7_12") (pintype "open_collector"))
      (node (ref "IC5") (pin "12") (pinfunction "12_12") (pintype "bidirectional"))
      (node (ref "X1") (pin "2") (pinfunction "KL_2") (pintype "passive"))
    )
    (net (code "50") (name "Net-(IC4-O8)") (class "Default")
      (node (ref "IC4") (pin "11") (pinfunction "O8_11") (pintype "open_collector"))
      (node (ref "IC5") (pin "11") (pinfunction "11_11") (pintype "bidirectional"))
      (node (ref "X1") (pin "1") (pinfunction "KL_1") (pintype "passive"))
    )
    (net (code "51") (name "Net-(IC6-CH0)") (class "Default")
      (node (ref "IC5") (pin "8") (pinfunction "8_8") (pintype "bidirectional"))
      (node (ref "IC6") (pin "6") (pinfunction "CH0_6") (pintype "bidirectional"))
    )
    (net (code "52") (name "Net-(IC6-CH1)") (class "Default")
      (node (ref "IC5") (pin "7") (pinfunction "7_7") (pintype "bidirectional"))
      (node (ref "IC6") (pin "7") (pinfunction "CH1_7") (pintype "bidirectional"))
    )
    (net (code "53") (name "Net-(IC6-CH2)") (class "Default")
      (node (ref "IC5") (pin "6") (pinfunction "6_6") (pintype "bidirectional"))
      (node (ref "IC6") (pin "8") (pinfunction "CH2_8") (pintype "bidirectional"))
    )
    (net (code "54") (name "Net-(IC6-CH3)") (class "Default")
      (node (ref "IC5") (pin "5") (pinfunction "5_5") (pintype "bidirectional"))
      (node (ref "IC6") (pin "9") (pinfunction "CH3_9") (pintype "bidirectional"))
    )
    (net (code "55") (name "Net-(IC6-CH4)") (class "Default")
      (node (ref "IC5") (pin "4") (pinfunction "4_4") (pintype "bidirectional"))
      (node (ref "IC6") (pin "10") (pinfunction "CH4_10") (pintype "bidirectional"))
    )
    (net (code "56") (name "Net-(IC6-CH5)") (class "Default")
      (node (ref "IC5") (pin "3") (pinfunction "3_3") (pintype "bidirectional"))
      (node (ref "IC6") (pin "11") (pinfunction "CH5_11") (pintype "bidirectional"))
    )
    (net (code "57") (name "Net-(IC6-CH6)") (class "Default")
      (node (ref "IC5") (pin "2") (pinfunction "2_2") (pintype "bidirectional"))
      (node (ref "IC6") (pin "12") (pinfunction "CH6_12") (pintype "bidirectional"))
    )
    (net (code "58") (name "Net-(IC6-CH7)") (class "Default")
      (node (ref "IC5") (pin "1") (pinfunction "1_1") (pintype "bidirectional"))
      (node (ref "IC6") (pin "13") (pinfunction "CH7_13") (pintype "bidirectional"))
    )
    (net (code "59") (name "Net-(IC7-I1)") (class "Default")
      (node (ref "IC7") (pin "1") (pinfunction "I1_1") (pintype "input"))
      (node (ref "IC9") (pin "22") (pinfunction "CH15_22") (pintype "bidirectional"))
    )
    (net (code "60") (name "Net-(IC7-I2)") (class "Default")
      (node (ref "IC7") (pin "2") (pinfunction "I2_2") (pintype "input"))
      (node (ref "IC9") (pin "21") (pinfunction "CH14_21") (pintype "bidirectional"))
    )
    (net (code "61") (name "Net-(IC7-I3)") (class "Default")
      (node (ref "IC7") (pin "3") (pinfunction "I3_3") (pintype "input"))
      (node (ref "IC9") (pin "20") (pinfunction "CH13_20") (pintype "bidirectional"))
    )
    (net (code "62") (name "Net-(IC7-I4)") (class "Default")
      (node (ref "IC7") (pin "4") (pinfunction "I4_4") (pintype "input"))
      (node (ref "IC9") (pin "19") (pinfunction "CH12_19") (pintype "bidirectional"))
    )
    (net (code "63") (name "Net-(IC7-I5)") (class "Default")
      (node (ref "IC7") (pin "5") (pinfunction "I5_5") (pintype "input"))
      (node (ref "IC9") (pin "18") (pinfunction "CH11_18") (pintype "bidirectional"))
    )
    (net (code "64") (name "Net-(IC7-I6)") (class "Default")
      (node (ref "IC7") (pin "6") (pinfunction "I6_6") (pintype "input"))
      (node (ref "IC9") (pin "17") (pinfunction "CH10_17") (pintype "bidirectional"))
    )
    (net (code "65") (name "Net-(IC7-I7)") (class "Default")
      (node (ref "IC7") (pin "7") (pinfunction "I7_7") (pintype "input"))
      (node (ref "IC9") (pin "16") (pinfunction "CH9_16") (pintype "bidirectional"))
    )
    (net (code "66") (name "Net-(IC7-I8)") (class "Default")
      (node (ref "IC7") (pin "8") (pinfunction "I8_8") (pintype "input"))
      (node (ref "IC9") (pin "15") (pinfunction "CH8_15") (pintype "bidirectional"))
    )
    (net (code "67") (name "Net-(IC7-O1)") (class "Default")
      (node (ref "IC7") (pin "18") (pinfunction "O1_18") (pintype "open_collector"))
      (node (ref "X2") (pin "15") (pinfunction "KL_15") (pintype "passive"))
    )
    (net (code "68") (name "Net-(IC7-O2)") (class "Default")
      (node (ref "IC7") (pin "17") (pinfunction "O2_17") (pintype "open_collector"))
      (node (ref "X2") (pin "13") (pinfunction "KL_13") (pintype "passive"))
    )
    (net (code "69") (name "Net-(IC7-O3)") (class "Default")
      (node (ref "IC7") (pin "16") (pinfunction "O3_16") (pintype "open_collector"))
      (node (ref "X2") (pin "11") (pinfunction "KL_11") (pintype "passive"))
    )
    (net (code "70") (name "Net-(IC7-O4)") (class "Default")
      (node (ref "IC7") (pin "15") (pinfunction "O4_15") (pintype "open_collector"))
      (node (ref "X2") (pin "9") (pinfunction "KL_9") (pintype "passive"))
    )
    (net (code "71") (name "Net-(IC7-O5)") (class "Default")
      (node (ref "IC7") (pin "14") (pinfunction "O5_14") (pintype "open_collector"))
      (node (ref "X2") (pin "7") (pinfunction "KL_7") (pintype "passive"))
    )
    (net (code "72") (name "Net-(IC7-O6)") (class "Default")
      (node (ref "IC7") (pin "13") (pinfunction "O6_13") (pintype "open_collector"))
      (node (ref "X2") (pin "5") (pinfunction "KL_5") (pintype "passive"))
    )
    (net (code "73") (name "Net-(IC7-O7)") (class "Default")
      (node (ref "IC7") (pin "12") (pinfunction "O7_12") (pintype "open_collector"))
      (node (ref "X2") (pin "3") (pinfunction "KL_3") (pintype "passive"))
    )
    (net (code "74") (name "Net-(IC7-O8)") (class "Default")
      (node (ref "IC7") (pin "11") (pinfunction "O8_11") (pintype "open_collector"))
      (node (ref "X2") (pin "1") (pinfunction "KL_1") (pintype "passive"))
    )
    (net (code "75") (name "Net-(IC9-CH0)") (class "Default")
      (node (ref "IC8") (pin "8") (pinfunction "8_8") (pintype "bidirectional"))
      (node (ref "IC9") (pin "6") (pinfunction "CH0_6") (pintype "bidirectional"))
    )
    (net (code "76") (name "Net-(IC9-CH1)") (class "Default")
      (node (ref "IC8") (pin "7") (pinfunction "7_7") (pintype "bidirectional"))
      (node (ref "IC9") (pin "7") (pinfunction "CH1_7") (pintype "bidirectional"))
    )
    (net (code "77") (name "Net-(IC9-CH2)") (class "Default")
      (node (ref "IC8") (pin "6") (pinfunction "6_6") (pintype "bidirectional"))
      (node (ref "IC9") (pin "8") (pinfunction "CH2_8") (pintype "bidirectional"))
    )
    (net (code "78") (name "Net-(IC9-CH3)") (class "Default")
      (node (ref "IC8") (pin "5") (pinfunction "5_5") (pintype "bidirectional"))
      (node (ref "IC9") (pin "9") (pinfunction "CH3_9") (pintype "bidirectional"))
    )
    (net (code "79") (name "Net-(IC9-CH4)") (class "Default")
      (node (ref "IC8") (pin "4") (pinfunction "4_4") (pintype "bidirectional"))
      (node (ref "IC9") (pin "10") (pinfunction "CH4_10") (pintype "bidirectional"))
    )
    (net (code "80") (name "Net-(IC9-CH5)") (class "Default")
      (node (ref "IC8") (pin "3") (pinfunction "3_3") (pintype "bidirectional"))
      (node (ref "IC9") (pin "11") (pinfunction "CH5_11") (pintype "bidirectional"))
    )
    (net (code "81") (name "Net-(IC9-CH6)") (class "Default")
      (node (ref "IC8") (pin "2") (pinfunction "2_2") (pintype "bidirectional"))
      (node (ref "IC9") (pin "12") (pinfunction "CH6_12") (pintype "bidirectional"))
    )
    (net (code "82") (name "Net-(IC9-CH7)") (class "Default")
      (node (ref "IC8") (pin "1") (pinfunction "1_1") (pintype "bidirectional"))
      (node (ref "IC9") (pin "13") (pinfunction "CH7_13") (pintype "bidirectional"))
    )
    (net (code "83") (name "Net-(IC10-I1)") (class "Default")
      (node (ref "IC10") (pin "1") (pinfunction "I1_1") (pintype "input"))
      (node (ref "IC12") (pin "22") (pinfunction "CH15_22") (pintype "bidirectional"))
    )
    (net (code "84") (name "Net-(IC10-I2)") (class "Default")
      (node (ref "IC10") (pin "2") (pinfunction "I2_2") (pintype "input"))
      (node (ref "IC12") (pin "21") (pinfunction "CH14_21") (pintype "bidirectional"))
    )
    (net (code "85") (name "Net-(IC10-I3)") (class "Default")
      (node (ref "IC10") (pin "3") (pinfunction "I3_3") (pintype "input"))
      (node (ref "IC12") (pin "20") (pinfunction "CH13_20") (pintype "bidirectional"))
    )
    (net (code "86") (name "Net-(IC10-I4)") (class "Default")
      (node (ref "IC10") (pin "4") (pinfunction "I4_4") (pintype "input"))
      (node (ref "IC12") (pin "19") (pinfunction "CH12_19") (pintype "bidirectional"))
    )
    (net (code "87") (name "Net-(IC10-I5)") (class "Default")
      (node (ref "IC10") (pin "5") (pinfunction "I5_5") (pintype "input"))
      (node (ref "IC12") (pin "18") (pinfunction "CH11_18") (pintype "bidirectional"))
    )
    (net (code "88") (name "Net-(IC10-I6)") (class "Default")
      (node (ref "IC10") (pin "6") (pinfunction "I6_6") (pintype "input"))
      (node (ref "IC12") (pin "17") (pinfunction "CH10_17") (pintype "bidirectional"))
    )
    (net (code "89") (name "Net-(IC10-I7)") (class "Default")
      (node (ref "IC10") (pin "7") (pinfunction "I7_7") (pintype "input"))
      (node (ref "IC12") (pin "16") (pinfunction "CH9_16") (pintype "bidirectional"))
    )
    (net (code "90") (name "Net-(IC10-I8)") (class "Default")
      (node (ref "IC10") (pin "8") (pinfunction "I8_8") (pintype "input"))
      (node (ref "IC12") (pin "15") (pinfunction "CH8_15") (pintype "bidirectional"))
    )
    (net (code "91") (name "Net-(IC10-O1)") (class "Default")
      (node (ref "IC10") (pin "18") (pinfunction "O1_18") (pintype "open_collector"))
      (node (ref "IC11") (pin "18") (pinfunction "18_18") (pintype "bidirectional"))
      (node (ref "X1") (pin "16") (pinfunction "KL_16") (pintype "passive"))
    )
    (net (code "92") (name "Net-(IC10-O2)") (class "Default")
      (node (ref "IC10") (pin "17") (pinfunction "O2_17") (pintype "open_collector"))
      (node (ref "IC11") (pin "17") (pinfunction "17_17") (pintype "bidirectional"))
      (node (ref "X1") (pin "15") (pinfunction "KL_15") (pintype "passive"))
    )
    (net (code "93") (name "Net-(IC10-O3)") (class "Default")
      (node (ref "IC10") (pin "16") (pinfunction "O3_16") (pintype "open_collector"))
      (node (ref "IC11") (pin "16") (pinfunction "16_16") (pintype "bidirectional"))
      (node (ref "X1") (pin "14") (pinfunction "KL_14") (pintype "passive"))
    )
    (net (code "94") (name "Net-(IC10-O4)") (class "Default")
      (node (ref "IC10") (pin "15") (pinfunction "O4_15") (pintype "open_collector"))
      (node (ref "IC11") (pin "15") (pinfunction "15_15") (pintype "bidirectional"))
      (node (ref "X1") (pin "13") (pinfunction "KL_13") (pintype "passive"))
    )
    (net (code "95") (name "Net-(IC10-O5)") (class "Default")
      (node (ref "IC10") (pin "14") (pinfunction "O5_14") (pintype "open_collector"))
      (node (ref "IC11") (pin "14") (pinfunction "14_14") (pintype "bidirectional"))
      (node (ref "X1") (pin "12") (pinfunction "KL_12") (pintype "passive"))
    )
    (net (code "96") (name "Net-(IC10-O6)") (class "Default")
      (node (ref "IC10") (pin "13") (pinfunction "O6_13") (pintype "open_collector"))
      (node (ref "IC11") (pin "13") (pinfunction "13_13") (pintype "bidirectional"))
      (node (ref "X1") (pin "11") (pinfunction "KL_11") (pintype "passive"))
    )
    (net (code "97") (name "Net-(IC10-O7)") (class "Default")
      (node (ref "IC10") (pin "12") (pinfunction "O7_12") (pintype "open_collector"))
      (node (ref "IC11") (pin "12") (pinfunction "12_12") (pintype "bidirectional"))
      (node (ref "X1") (pin "10") (pinfunction "KL_10") (pintype "passive"))
    )
    (net (code "98") (name "Net-(IC10-O8)") (class "Default")
      (node (ref "IC10") (pin "11") (pinfunction "O8_11") (pintype "open_collector"))
      (node (ref "IC11") (pin "11") (pinfunction "11_11") (pintype "bidirectional"))
      (node (ref "X1") (pin "9") (pinfunction "KL_9") (pintype "passive"))
    )
    (net (code "99") (name "Net-(IC12-CH0)") (class "Default")
      (node (ref "IC11") (pin "8") (pinfunction "8_8") (pintype "bidirectional"))
      (node (ref "IC12") (pin "6") (pinfunction "CH0_6") (pintype "bidirectional"))
    )
    (net (code "100") (name "Net-(IC12-CH1)") (class "Default")
      (node (ref "IC11") (pin "7") (pinfunction "7_7") (pintype "bidirectional"))
      (node (ref "IC12") (pin "7") (pinfunction "CH1_7") (pintype "bidirectional"))
    )
    (net (code "101") (name "Net-(IC12-CH2)") (class "Default")
      (node (ref "IC11") (pin "6") (pinfunction "6_6") (pintype "bidirectional"))
      (node (ref "IC12") (pin "8") (pinfunction "CH2_8") (pintype "bidirectional"))
    )
    (net (code "102") (name "Net-(IC12-CH3)") (class "Default")
      (node (ref "IC11") (pin "5") (pinfunction "5_5") (pintype "bidirectional"))
      (node (ref "IC12") (pin "9") (pinfunction "CH3_9") (pintype "bidirectional"))
    )
    (net (code "103") (name "Net-(IC12-CH4)") (class "Default")
      (node (ref "IC11") (pin "4") (pinfunction "4_4") (pintype "bidirectional"))
      (node (ref "IC12") (pin "10") (pinfunction "CH4_10") (pintype "bidirectional"))
    )
    (net (code "104") (name "Net-(IC12-CH5)") (class "Default")
      (node (ref "IC11") (pin "3") (pinfunction "3_3") (pintype "bidirectional"))
      (node (ref "IC12") (pin "11") (pinfunction "CH5_11") (pintype "bidirectional"))
    )
    (net (code "105") (name "Net-(IC12-CH6)") (class "Default")
      (node (ref "IC11") (pin "2") (pinfunction "2_2") (pintype "bidirectional"))
      (node (ref "IC12") (pin "12") (pinfunction "CH6_12") (pintype "bidirectional"))
    )
    (net (code "106") (name "Net-(IC12-CH7)") (class "Default")
      (node (ref "IC11") (pin "1") (pinfunction "1_1") (pintype "bidirectional"))
      (node (ref "IC12") (pin "13") (pinfunction "CH7_13") (pintype "bidirectional"))
    )
    (net (code "107") (name "Net-(IC13-I1)") (class "Default")
      (node (ref "IC13") (pin "1") (pinfunction "I1_1") (pintype "input"))
      (node (ref "IC15") (pin "22") (pinfunction "CH15_22") (pintype "bidirectional"))
    )
    (net (code "108") (name "Net-(IC13-I2)") (class "Default")
      (node (ref "IC13") (pin "2") (pinfunction "I2_2") (pintype "input"))
      (node (ref "IC15") (pin "21") (pinfunction "CH14_21") (pintype "bidirectional"))
    )
    (net (code "109") (name "Net-(IC13-I3)") (class "Default")
      (node (ref "IC13") (pin "3") (pinfunction "I3_3") (pintype "input"))
      (node (ref "IC15") (pin "20") (pinfunction "CH13_20") (pintype "bidirectional"))
    )
    (net (code "110") (name "Net-(IC13-I4)") (class "Default")
      (node (ref "IC13") (pin "4") (pinfunction "I4_4") (pintype "input"))
      (node (ref "IC15") (pin "19") (pinfunction "CH12_19") (pintype "bidirectional"))
    )
    (net (code "111") (name "Net-(IC13-I5)") (class "Default")
      (node (ref "IC13") (pin "5") (pinfunction "I5_5") (pintype "input"))
      (node (ref "IC15") (pin "18") (pinfunction "CH11_18") (pintype "bidirectional"))
    )
    (net (code "112") (name "Net-(IC13-I6)") (class "Default")
      (node (ref "IC13") (pin "6") (pinfunction "I6_6") (pintype "input"))
      (node (ref "IC15") (pin "17") (pinfunction "CH10_17") (pintype "bidirectional"))
    )
    (net (code "113") (name "Net-(IC13-I7)") (class "Default")
      (node (ref "IC13") (pin "7") (pinfunction "I7_7") (pintype "input"))
      (node (ref "IC15") (pin "16") (pinfunction "CH9_16") (pintype "bidirectional"))
    )
    (net (code "114") (name "Net-(IC13-I8)") (class "Default")
      (node (ref "IC13") (pin "8") (pinfunction "I8_8") (pintype "input"))
      (node (ref "IC15") (pin "15") (pinfunction "CH8_15") (pintype "bidirectional"))
    )
    (net (code "115") (name "Net-(IC13-O1)") (class "Default")
      (node (ref "IC13") (pin "18") (pinfunction "O1_18") (pintype "open_collector"))
      (node (ref "X3") (pin "15") (pinfunction "KL_15") (pintype "passive"))
    )
    (net (code "116") (name "Net-(IC13-O2)") (class "Default")
      (node (ref "IC13") (pin "17") (pinfunction "O2_17") (pintype "open_collector"))
      (node (ref "X3") (pin "13") (pinfunction "KL_13") (pintype "passive"))
    )
    (net (code "117") (name "Net-(IC13-O3)") (class "Default")
      (node (ref "IC13") (pin "16") (pinfunction "O3_16") (pintype "open_collector"))
      (node (ref "X3") (pin "11") (pinfunction "KL_11") (pintype "passive"))
    )
    (net (code "118") (name "Net-(IC13-O4)") (class "Default")
      (node (ref "IC13") (pin "15") (pinfunction "O4_15") (pintype "open_collector"))
      (node (ref "X3") (pin "9") (pinfunction "KL_9") (pintype "passive"))
    )
    (net (code "119") (name "Net-(IC13-O5)") (class "Default")
      (node (ref "IC13") (pin "14") (pinfunction "O5_14") (pintype "open_collector"))
      (node (ref "X3") (pin "7") (pinfunction "KL_7") (pintype "passive"))
    )
    (net (code "120") (name "Net-(IC13-O6)") (class "Default")
      (node (ref "IC13") (pin "13") (pinfunction "O6_13") (pintype "open_collector"))
      (node (ref "X3") (pin "5") (pinfunction "KL_5") (pintype "passive"))
    )
    (net (code "121") (name "Net-(IC13-O7)") (class "Default")
      (node (ref "IC13") (pin "12") (pinfunction "O7_12") (pintype "open_collector"))
      (node (ref "X3") (pin "3") (pinfunction "KL_3") (pintype "passive"))
    )
    (net (code "122") (name "Net-(IC13-O8)") (class "Default")
      (node (ref "IC13") (pin "11") (pinfunction "O8_11") (pintype "open_collector"))
      (node (ref "X3") (pin "1") (pinfunction "KL_1") (pintype "passive"))
    )
    (net (code "123") (name "Net-(IC15-CH0)") (class "Default")
      (node (ref "IC14") (pin "8") (pinfunction "8_8") (pintype "bidirectional"))
      (node (ref "IC15") (pin "6") (pinfunction "CH0_6") (pintype "bidirectional"))
    )
    (net (code "124") (name "Net-(IC15-CH1)") (class "Default")
      (node (ref "IC14") (pin "7") (pinfunction "7_7") (pintype "bidirectional"))
      (node (ref "IC15") (pin "7") (pinfunction "CH1_7") (pintype "bidirectional"))
    )
    (net (code "125") (name "Net-(IC15-CH2)") (class "Default")
      (node (ref "IC14") (pin "6") (pinfunction "6_6") (pintype "bidirectional"))
      (node (ref "IC15") (pin "8") (pinfunction "CH2_8") (pintype "bidirectional"))
    )
    (net (code "126") (name "Net-(IC15-CH3)") (class "Default")
      (node (ref "IC14") (pin "5") (pinfunction "5_5") (pintype "bidirectional"))
      (node (ref "IC15") (pin "9") (pinfunction "CH3_9") (pintype "bidirectional"))
    )
    (net (code "127") (name "Net-(IC15-CH4)") (class "Default")
      (node (ref "IC14") (pin "4") (pinfunction "4_4") (pintype "bidirectional"))
      (node (ref "IC15") (pin "10") (pinfunction "CH4_10") (pintype "bidirectional"))
    )
    (net (code "128") (name "Net-(IC15-CH5)") (class "Default")
      (node (ref "IC14") (pin "3") (pinfunction "3_3") (pintype "bidirectional"))
      (node (ref "IC15") (pin "11") (pinfunction "CH5_11") (pintype "bidirectional"))
    )
    (net (code "129") (name "Net-(IC15-CH6)") (class "Default")
      (node (ref "IC14") (pin "2") (pinfunction "2_2") (pintype "bidirectional"))
      (node (ref "IC15") (pin "12") (pinfunction "CH6_12") (pintype "bidirectional"))
    )
    (net (code "130") (name "Net-(IC15-CH7)") (class "Default")
      (node (ref "IC14") (pin "1") (pinfunction "1_1") (pintype "bidirectional"))
      (node (ref "IC15") (pin "13") (pinfunction "CH7_13") (pintype "bidirectional"))
    )
    (net (code "131") (name "Net-(IC16-I1)") (class "Default")
      (node (ref "IC16") (pin "1") (pinfunction "I1_1") (pintype "input"))
      (node (ref "IC18") (pin "22") (pinfunction "CH15_22") (pintype "bidirectional"))
    )
    (net (code "132") (name "Net-(IC16-I2)") (class "Default")
      (node (ref "IC16") (pin "2") (pinfunction "I2_2") (pintype "input"))
      (node (ref "IC18") (pin "21") (pinfunction "CH14_21") (pintype "bidirectional"))
    )
    (net (code "133") (name "Net-(IC16-I3)") (class "Default")
      (node (ref "IC16") (pin "3") (pinfunction "I3_3") (pintype "input"))
      (node (ref "IC18") (pin "20") (pinfunction "CH13_20") (pintype "bidirectional"))
    )
    (net (code "134") (name "Net-(IC16-I4)") (class "Default")
      (node (ref "IC16") (pin "4") (pinfunction "I4_4") (pintype "input"))
      (node (ref "IC18") (pin "19") (pinfunction "CH12_19") (pintype "bidirectional"))
    )
    (net (code "135") (name "Net-(IC16-I5)") (class "Default")
      (node (ref "IC16") (pin "5") (pinfunction "I5_5") (pintype "input"))
      (node (ref "IC18") (pin "18") (pinfunction "CH11_18") (pintype "bidirectional"))
    )
    (net (code "136") (name "Net-(IC16-I6)") (class "Default")
      (node (ref "IC16") (pin "6") (pinfunction "I6_6") (pintype "input"))
      (node (ref "IC18") (pin "17") (pinfunction "CH10_17") (pintype "bidirectional"))
    )
    (net (code "137") (name "Net-(IC16-I7)") (class "Default")
      (node (ref "IC16") (pin "7") (pinfunction "I7_7") (pintype "input"))
      (node (ref "IC18") (pin "16") (pinfunction "CH9_16") (pintype "bidirectional"))
    )
    (net (code "138") (name "Net-(IC16-I8)") (class "Default")
      (node (ref "IC16") (pin "8") (pinfunction "I8_8") (pintype "input"))
      (node (ref "IC18") (pin "15") (pinfunction "CH8_15") (pintype "bidirectional"))
    )
    (net (code "139") (name "Net-(IC16-O1)") (class "Default")
      (node (ref "IC16") (pin "18") (pinfunction "O1_18") (pintype "open_collector"))
      (node (ref "IC17") (pin "18") (pinfunction "18_18") (pintype "bidirectional"))
      (node (ref "X1") (pin "24") (pinfunction "KL_24") (pintype "passive"))
    )
    (net (code "140") (name "Net-(IC16-O2)") (class "Default")
      (node (ref "IC16") (pin "17") (pinfunction "O2_17") (pintype "open_collector"))
      (node (ref "IC17") (pin "17") (pinfunction "17_17") (pintype "bidirectional"))
      (node (ref "X1") (pin "23") (pinfunction "KL_23") (pintype "passive"))
    )
    (net (code "141") (name "Net-(IC16-O3)") (class "Default")
      (node (ref "IC16") (pin "16") (pinfunction "O3_16") (pintype "open_collector"))
      (node (ref "IC17") (pin "16") (pinfunction "16_16") (pintype "bidirectional"))
      (node (ref "X1") (pin "22") (pinfunction "KL_22") (pintype "passive"))
    )
    (net (code "142") (name "Net-(IC16-O4)") (class "Default")
      (node (ref "IC16") (pin "15") (pinfunction "O4_15") (pintype "open_collector"))
      (node (ref "IC17") (pin "15") (pinfunction "15_15") (pintype "bidirectional"))
      (node (ref "X1") (pin "21") (pinfunction "KL_21") (pintype "passive"))
    )
    (net (code "143") (name "Net-(IC16-O5)") (class "Default")
      (node (ref "IC16") (pin "14") (pinfunction "O5_14") (pintype "open_collector"))
      (node (ref "IC17") (pin "14") (pinfunction "14_14") (pintype "bidirectional"))
      (node (ref "X1") (pin "20") (pinfunction "KL_20") (pintype "passive"))
    )
    (net (code "144") (name "Net-(IC16-O6)") (class "Default")
      (node (ref "IC16") (pin "13") (pinfunction "O6_13") (pintype "open_collector"))
      (node (ref "IC17") (pin "13") (pinfunction "13_13") (pintype "bidirectional"))
      (node (ref "X1") (pin "19") (pinfunction "KL_19") (pintype "passive"))
    )
    (net (code "145") (name "Net-(IC16-O7)") (class "Default")
      (node (ref "IC16") (pin "12") (pinfunction "O7_12") (pintype "open_collector"))
      (node (ref "IC17") (pin "12") (pinfunction "12_12") (pintype "bidirectional"))
      (node (ref "X1") (pin "18") (pinfunction "KL_18") (pintype "passive"))
    )
    (net (code "146") (name "Net-(IC16-O8)") (class "Default")
      (node (ref "IC16") (pin "11") (pinfunction "O8_11") (pintype "open_collector"))
      (node (ref "IC17") (pin "11") (pinfunction "11_11") (pintype "bidirectional"))
      (node (ref "X1") (pin "17") (pinfunction "KL_17") (pintype "passive"))
    )
    (net (code "147") (name "Net-(IC18-CH0)") (class "Default")
      (node (ref "IC17") (pin "8") (pinfunction "8_8") (pintype "bidirectional"))
      (node (ref "IC18") (pin "6") (pinfunction "CH0_6") (pintype "bidirectional"))
    )
    (net (code "148") (name "Net-(IC18-CH1)") (class "Default")
      (node (ref "IC17") (pin "7") (pinfunction "7_7") (pintype "bidirectional"))
      (node (ref "IC18") (pin "7") (pinfunction "CH1_7") (pintype "bidirectional"))
    )
    (net (code "149") (name "Net-(IC18-CH2)") (class "Default")
      (node (ref "IC17") (pin "6") (pinfunction "6_6") (pintype "bidirectional"))
      (node (ref "IC18") (pin "8") (pinfunction "CH2_8") (pintype "bidirectional"))
    )
    (net (code "150") (name "Net-(IC18-CH3)") (class "Default")
      (node (ref "IC17") (pin "5") (pinfunction "5_5") (pintype "bidirectional"))
      (node (ref "IC18") (pin "9") (pinfunction "CH3_9") (pintype "bidirectional"))
    )
    (net (code "151") (name "Net-(IC18-CH4)") (class "Default")
      (node (ref "IC17") (pin "4") (pinfunction "4_4") (pintype "bidirectional"))
      (node (ref "IC18") (pin "10") (pinfunction "CH4_10") (pintype "bidirectional"))
    )
    (net (code "152") (name "Net-(IC18-CH5)") (class "Default")
      (node (ref "IC17") (pin "3") (pinfunction "3_3") (pintype "bidirectional"))
      (node (ref "IC18") (pin "11") (pinfunction "CH5_11") (pintype "bidirectional"))
    )
    (net (code "153") (name "Net-(IC18-CH6)") (class "Default")
      (node (ref "IC17") (pin "2") (pinfunction "2_2") (pintype "bidirectional"))
      (node (ref "IC18") (pin "12") (pinfunction "CH6_12") (pintype "bidirectional"))
    )
    (net (code "154") (name "Net-(IC18-CH7)") (class "Default")
      (node (ref "IC17") (pin "1") (pinfunction "1_1") (pintype "bidirectional"))
      (node (ref "IC18") (pin "13") (pinfunction "CH7_13") (pintype "bidirectional"))
    )
    (net (code "155") (name "Net-(IC22-I1)") (class "Default")
      (node (ref "IC22") (pin "1") (pinfunction "I1_1") (pintype "input"))
      (node (ref "IC24") (pin "22") (pinfunction "CH15_22") (pintype "bidirectional"))
    )
    (net (code "156") (name "Net-(IC22-I2)") (class "Default")
      (node (ref "IC22") (pin "2") (pinfunction "I2_2") (pintype "input"))
      (node (ref "IC24") (pin "21") (pinfunction "CH14_21") (pintype "bidirectional"))
    )
    (net (code "157") (name "Net-(IC22-I3)") (class "Default")
      (node (ref "IC22") (pin "3") (pinfunction "I3_3") (pintype "input"))
      (node (ref "IC24") (pin "20") (pinfunction "CH13_20") (pintype "bidirectional"))
    )
    (net (code "158") (name "Net-(IC22-I4)") (class "Default")
      (node (ref "IC22") (pin "4") (pinfunction "I4_4") (pintype "input"))
      (node (ref "IC24") (pin "19") (pinfunction "CH12_19") (pintype "bidirectional"))
    )
    (net (code "159") (name "Net-(IC22-I5)") (class "Default")
      (node (ref "IC22") (pin "5") (pinfunction "I5_5") (pintype "input"))
      (node (ref "IC24") (pin "18") (pinfunction "CH11_18") (pintype "bidirectional"))
    )
    (net (code "160") (name "Net-(IC22-I6)") (class "Default")
      (node (ref "IC22") (pin "6") (pinfunction "I6_6") (pintype "input"))
      (node (ref "IC24") (pin "17") (pinfunction "CH10_17") (pintype "bidirectional"))
    )
    (net (code "161") (name "Net-(IC22-I7)") (class "Default")
      (node (ref "IC22") (pin "7") (pinfunction "I7_7") (pintype "input"))
      (node (ref "IC24") (pin "16") (pinfunction "CH9_16") (pintype "bidirectional"))
    )
    (net (code "162") (name "Net-(IC22-I8)") (class "Default")
      (node (ref "IC22") (pin "8") (pinfunction "I8_8") (pintype "input"))
      (node (ref "IC24") (pin "15") (pinfunction "CH8_15") (pintype "bidirectional"))
    )
    (net (code "163") (name "Net-(IC22-O1)") (class "Default")
      (node (ref "IC22") (pin "18") (pinfunction "O1_18") (pintype "open_collector"))
      (node (ref "IC23") (pin "18") (pinfunction "18_18") (pintype "bidirectional"))
      (node (ref "X1") (pin "32") (pinfunction "KL_32") (pintype "passive"))
    )
    (net (code "164") (name "Net-(IC22-O2)") (class "Default")
      (node (ref "IC22") (pin "17") (pinfunction "O2_17") (pintype "open_collector"))
      (node (ref "IC23") (pin "17") (pinfunction "17_17") (pintype "bidirectional"))
      (node (ref "X1") (pin "31") (pinfunction "KL_31") (pintype "passive"))
    )
    (net (code "165") (name "Net-(IC22-O3)") (class "Default")
      (node (ref "IC22") (pin "16") (pinfunction "O3_16") (pintype "open_collector"))
      (node (ref "IC23") (pin "16") (pinfunction "16_16") (pintype "bidirectional"))
      (node (ref "X1") (pin "30") (pinfunction "KL_30") (pintype "passive"))
    )
    (net (code "166") (name "Net-(IC22-O4)") (class "Default")
      (node (ref "IC22") (pin "15") (pinfunction "O4_15") (pintype "open_collector"))
      (node (ref "IC23") (pin "15") (pinfunction "15_15") (pintype "bidirectional"))
      (node (ref "X1") (pin "29") (pinfunction "KL_29") (pintype "passive"))
    )
    (net (code "167") (name "Net-(IC22-O5)") (class "Default")
      (node (ref "IC22") (pin "14") (pinfunction "O5_14") (pintype "open_collector"))
      (node (ref "IC23") (pin "14") (pinfunction "14_14") (pintype "bidirectional"))
      (node (ref "X1") (pin "28") (pinfunction "KL_28") (pintype "passive"))
    )
    (net (code "168") (name "Net-(IC22-O6)") (class "Default")
      (node (ref "IC22") (pin "13") (pinfunction "O6_13") (pintype "open_collector"))
      (node (ref "IC23") (pin "13") (pinfunction "13_13") (pintype "bidirectional"))
      (node (ref "X1") (pin "27") (pinfunction "KL_27") (pintype "passive"))
    )
    (net (code "169") (name "Net-(IC22-O7)") (class "Default")
      (node (ref "IC22") (pin "12") (pinfunction "O7_12") (pintype "open_collector"))
      (node (ref "IC23") (pin "12") (pinfunction "12_12") (pintype "bidirectional"))
      (node (ref "X1") (pin "26") (pinfunction "KL_26") (pintype "passive"))
    )
    (net (code "170") (name "Net-(IC22-O8)") (class "Default")
      (node (ref "IC22") (pin "11") (pinfunction "O8_11") (pintype "open_collector"))
      (node (ref "IC23") (pin "11") (pinfunction "11_11") (pintype "bidirectional"))
      (node (ref "X1") (pin "25") (pinfunction "KL_25") (pintype "passive"))
    )
    (net (code "171") (name "Net-(IC24-CH0)") (class "Default")
      (node (ref "IC23") (pin "8") (pinfunction "8_8") (pintype "bidirectional"))
      (node (ref "IC24") (pin "6") (pinfunction "CH0_6") (pintype "bidirectional"))
    )
    (net (code "172") (name "Net-(IC24-CH1)") (class "Default")
      (node (ref "IC23") (pin "7") (pinfunction "7_7") (pintype "bidirectional"))
      (node (ref "IC24") (pin "7") (pinfunction "CH1_7") (pintype "bidirectional"))
    )
    (net (code "173") (name "Net-(IC24-CH2)") (class "Default")
      (node (ref "IC23") (pin "6") (pinfunction "6_6") (pintype "bidirectional"))
      (node (ref "IC24") (pin "8") (pinfunction "CH2_8") (pintype "bidirectional"))
    )
    (net (code "174") (name "Net-(IC24-CH3)") (class "Default")
      (node (ref "IC23") (pin "5") (pinfunction "5_5") (pintype "bidirectional"))
      (node (ref "IC24") (pin "9") (pinfunction "CH3_9") (pintype "bidirectional"))
    )
    (net (code "175") (name "Net-(IC24-CH4)") (class "Default")
      (node (ref "IC23") (pin "4") (pinfunction "4_4") (pintype "bidirectional"))
      (node (ref "IC24") (pin "10") (pinfunction "CH4_10") (pintype "bidirectional"))
    )
    (net (code "176") (name "Net-(IC24-CH5)") (class "Default")
      (node (ref "IC23") (pin "3") (pinfunction "3_3") (pintype "bidirectional"))
      (node (ref "IC24") (pin "11") (pinfunction "CH5_11") (pintype "bidirectional"))
    )
    (net (code "177") (name "Net-(IC24-CH6)") (class "Default")
      (node (ref "IC23") (pin "2") (pinfunction "2_2") (pintype "bidirectional"))
      (node (ref "IC24") (pin "12") (pinfunction "CH6_12") (pintype "bidirectional"))
    )
    (net (code "178") (name "Net-(IC24-CH7)") (class "Default")
      (node (ref "IC23") (pin "1") (pinfunction "1_1") (pintype "bidirectional"))
      (node (ref "IC24") (pin "13") (pinfunction "CH7_13") (pintype "bidirectional"))
    )
    (net (code "179") (name "Net-(J3-Pad10)") (class "Default")
      (node (ref "J3") (pin "10") (pinfunction "10_10") (pintype "passive"))
      (node (ref "J8") (pin "1") (pinfunction "1_1") (pintype "passive"))
    )
    (net (code "180") (name "Net-(J14-Pad1)") (class "Default")
      (node (ref "J14") (pin "1") (pinfunction "1_1") (pintype "passive"))
      (node (ref "J3") (pin "3") (pinfunction "3_3") (pintype "passive"))
    )
    (net (code "181") (name "Net-(J16-Pad1)") (class "Default")
      (node (ref "J16") (pin "1") (pinfunction "1_1") (pintype "passive"))
      (node (ref "WEMOS1") (pin "RESET") (pinfunction "RESET_RESET") (pintype "bidirectional"))
    )
    (net (code "182") (name "Net-(J17-Pad1)") (class "Default")
      (node (ref "J17") (pin "1") (pinfunction "1_1") (pintype "passive"))
      (node (ref "WEMOS1") (pin "A0") (pinfunction "A0_A0") (pintype "bidirectional"))
    )
    (net (code "183") (name "Net-(J18-Pad1)") (class "Default")
      (node (ref "J18") (pin "1") (pinfunction "1_1") (pintype "passive"))
      (node (ref "WEMOS1") (pin "D0") (pinfunction "D0_D0") (pintype "bidirectional"))
    )
    (net (code "184") (name "Net-(J19-Pad1)") (class "Default")
      (node (ref "J19") (pin "1") (pinfunction "1_1") (pintype "passive"))
      (node (ref "WEMOS1") (pin "D5") (pinfunction "D5_D5") (pintype "bidirectional"))
    )
    (net (code "185") (name "Net-(J20-Pad1)") (class "Default")
      (node (ref "J20") (pin "1") (pinfunction "1_1") (pintype "passive"))
      (node (ref "WEMOS1") (pin "D6") (pinfunction "D6_D6") (pintype "bidirectional"))
    )
    (net (code "186") (name "Net-(J21-Pad1)") (class "Default")
      (node (ref "J21") (pin "1") (pinfunction "1_1") (pintype "passive"))
      (node (ref "WEMOS1") (pin "D7") (pinfunction "D7_D7") (pintype "bidirectional"))
    )
    (net (code "187") (name "Net-(J22-Pad1)") (class "Default")
      (node (ref "J22") (pin "1") (pinfunction "1_1") (pintype "passive"))
      (node (ref "WEMOS1") (pin "D8") (pinfunction "D8_D8") (pintype "bidirectional"))
    )
    (net (code "188") (name "Net-(J24-Pad1)") (class "Default")
      (node (ref "J24") (pin "1") (pinfunction "1_1") (pintype "passive"))
      (node (ref "WEMOS1") (pin "TX") (pinfunction "TX_TX") (pintype "bidirectional"))
    )
    (net (code "189") (name "Net-(J25-Pad1)") (class "Default")
      (node (ref "J25") (pin "1") (pinfunction "1_1") (pintype "passive"))
      (node (ref "WEMOS1") (pin "RX") (pinfunction "RX_RX") (pintype "bidirectional"))
    )
    (net (code "190") (name "Net-(J28-Pad1)") (class "Default")
      (node (ref "J28") (pin "1") (pinfunction "1_1") (pintype "passive"))
      (node (ref "WEMOS1") (pin "D3") (pinfunction "D3_D3") (pintype "bidirectional"))
    )
    (net (code "191") (name "Net-(J29-Pad1)") (class "Default")
      (node (ref "J29") (pin "1") (pinfunction "1_1") (pintype "passive"))
      (node (ref "WEMOS1") (pin "D4") (pinfunction "D4_D4") (pintype "bidirectional"))
    )
    (net (code "192") (name "Net-(U$1-ADJ)") (class "Default")
      (node (ref "R20") (pin "1") (pinfunction "1_1") (pintype "passive"))
      (node (ref "U$1") (pin "6") (pinfunction "ADJ_6") (pintype "bidirectional"))
    )
    (net (code "193") (name "Net-(X2B-KL)") (class "Default")
      (node (ref "IC8") (pin "15") (pinfunction "15_15") (pintype "bidirectional"))
      (node (ref "X2") (pin "10") (pinfunction "KL_10") (pintype "passive"))
    )
    (net (code "194") (name "Net-(X2D-KL)") (class "Default")
      (node (ref "IC8") (pin "16") (pinfunction "16_16") (pintype "bidirectional"))
      (node (ref "X2") (pin "12") (pinfunction "KL_12") (pintype "passive"))
    )
    (net (code "195") (name "Net-(X2F-KL)") (class "Default")
      (node (ref "IC8") (pin "17") (pinfunction "17_17") (pintype "bidirectional"))
      (node (ref "X2") (pin "14") (pinfunction "KL_14") (pintype "passive"))
    )
    (net (code "196") (name "Net-(X2H-KL)") (class "Default")
      (node (ref "IC8") (pin "18") (pinfunction "18_18") (pintype "bidirectional"))
      (node (ref "X2") (pin "16") (pinfunction "KL_16") (pintype "passive"))
    )
    (net (code "197") (name "Net-(X2I-KL)") (class "Default")
      (node (ref "IC8") (pin "11") (pinfunction "11_11") (pintype "bidirectional"))
      (node (ref "X2") (pin "2") (pinfunction "KL_2") (pintype "passive"))
    )
    (net (code "198") (name "Net-(X2K-KL)") (class "Default")
      (node (ref "IC8") (pin "12") (pinfunction "12_12") (pintype "bidirectional"))
      (node (ref "X2") (pin "4") (pinfunction "KL_4") (pintype "passive"))
    )
    (net (code "199") (name "Net-(X2M-KL)") (class "Default")
      (node (ref "IC8") (pin "13") (pinfunction "13_13") (pintype "bidirectional"))
      (node (ref "X2") (pin "6") (pinfunction "KL_6") (pintype "passive"))
    )
    (net (code "200") (name "Net-(X2O-KL)") (class "Default")
      (node (ref "IC8") (pin "14") (pinfunction "14_14") (pintype "bidirectional"))
      (node (ref "X2") (pin "8") (pinfunction "KL_8") (pintype "passive"))
    )
    (net (code "201") (name "Net-(X3B-KL)") (class "Default")
      (node (ref "IC14") (pin "15") (pinfunction "15_15") (pintype "bidirectional"))
      (node (ref "X3") (pin "10") (pinfunction "KL_10") (pintype "passive"))
    )
    (net (code "202") (name "Net-(X3D-KL)") (class "Default")
      (node (ref "IC14") (pin "16") (pinfunction "16_16") (pintype "bidirectional"))
      (node (ref "X3") (pin "12") (pinfunction "KL_12") (pintype "passive"))
    )
    (net (code "203") (name "Net-(X3F-KL)") (class "Default")
      (node (ref "IC14") (pin "17") (pinfunction "17_17") (pintype "bidirectional"))
      (node (ref "X3") (pin "14") (pinfunction "KL_14") (pintype "passive"))
    )
    (net (code "204") (name "Net-(X3H-KL)") (class "Default")
      (node (ref "IC14") (pin "18") (pinfunction "18_18") (pintype "bidirectional"))
      (node (ref "X3") (pin "16") (pinfunction "KL_16") (pintype "passive"))
    )
    (net (code "205") (name "Net-(X3I-KL)") (class "Default")
      (node (ref "IC14") (pin "11") (pinfunction "11_11") (pintype "bidirectional"))
      (node (ref "X3") (pin "2") (pinfunction "KL_2") (pintype "passive"))
    )
    (net (code "206") (name "Net-(X3K-KL)") (class "Default")
      (node (ref "IC14") (pin "12") (pinfunction "12_12") (pintype "bidirectional"))
      (node (ref "X3") (pin "4") (pinfunction "KL_4") (pintype "passive"))
    )
    (net (code "207") (name "Net-(X3M-KL)") (class "Default")
      (node (ref "IC14") (pin "13") (pinfunction "13_13") (pintype "bidirectional"))
      (node (ref "X3") (pin "6") (pinfunction "KL_6") (pintype "passive"))
    )
    (net (code "208") (name "Net-(X3O-KL)") (class "Default")
      (node (ref "IC14") (pin "14") (pinfunction "14_14") (pintype "bidirectional"))
      (node (ref "X3") (pin "8") (pinfunction "KL_8") (pintype "passive"))
    )
    (net (code "209") (name "SCL") (class "Default")
      (node (ref "ARDUINO_NANO") (pin "9") (pinfunction "A5_9") (pintype "bidirectional"))
      (node (ref "IC12") (pin "26") (pinfunction "SCL_26") (pintype "bidirectional"))
      (node (ref "IC15") (pin "26") (pinfunction "SCL_26") (pintype "bidirectional"))
      (node (ref "IC18") (pin "26") (pinfunction "SCL_26") (pintype "bidirectional"))
      (node (ref "IC24") (pin "26") (pinfunction "SCL_26") (pintype "bidirectional"))
      (node (ref "IC6") (pin "26") (pinfunction "SCL_26") (pintype "bidirectional"))
      (node (ref "IC9") (pin "26") (pinfunction "SCL_26") (pintype "bidirectional"))
      (node (ref "J1") (pin "1") (pinfunction "1_1") (pintype "passive"))
      (node (ref "J2") (pin "1") (pinfunction "1_1") (pintype "passive"))
      (node (ref "J82") (pin "1") (pinfunction "1_1") (pintype "passive"))
      (node (ref "Q1") (pin "3") (pinfunction "D_3") (pintype "bidirectional"))
      (node (ref "R10") (pin "1") (pinfunction "1_1") (pintype "passive"))
      (node (ref "R12") (pin "1") (pinfunction "1_1") (pintype "passive"))
      (node (ref "R16") (pin "1") (pinfunction "1_1") (pintype "passive"))
      (node (ref "R17") (pin "1") (pinfunction "1_1") (pintype "passive"))
      (node (ref "R2") (pin "1") (pinfunction "1_1") (pintype "passive"))
      (node (ref "R4") (pin "1") (pinfunction "1_1") (pintype "passive"))
      (node (ref "R8") (pin "1") (pinfunction "1_1") (pintype "passive"))
    )
    (net (code "210") (name "SDA") (class "Default")
      (node (ref "ARDUINO_NANO") (pin "8") (pinfunction "A4_8") (pintype "bidirectional"))
      (node (ref "IC12") (pin "27") (pinfunction "SDA_27") (pintype "bidirectional"))
      (node (ref "IC15") (pin "27") (pinfunction "SDA_27") (pintype "bidirectional"))
      (node (ref "IC18") (pin "27") (pinfunction "SDA_27") (pintype "bidirectional"))
      (node (ref "IC24") (pin "27") (pinfunction "SDA_27") (pintype "bidirectional"))
      (node (ref "IC6") (pin "27") (pinfunction "SDA_27") (pintype "bidirectional"))
      (node (ref "IC9") (pin "27") (pinfunction "SDA_27") (pintype "bidirectional"))
      (node (ref "J1") (pin "2") (pinfunction "2_2") (pintype "passive"))
      (node (ref "J2") (pin "2") (pinfunction "2_2") (pintype "passive"))
      (node (ref "J81") (pin "1") (pinfunction "1_1") (pintype "passive"))
      (node (ref "Q2") (pin "3") (pinfunction "D_3") (pintype "bidirectional"))
      (node (ref "R1") (pin "1") (pinfunction "1_1") (pintype "passive"))
      (node (ref "R11") (pin "1") (pinfunction "1_1") (pintype "passive"))
      (node (ref "R15") (pin "1") (pinfunction "1_1") (pintype "passive"))
      (node (ref "R19") (pin "1") (pinfunction "1_1") (pintype "passive"))
      (node (ref "R3") (pin "1") (pinfunction "1_1") (pintype "passive"))
      (node (ref "R7") (pin "1") (pinfunction "1_1") (pintype "passive"))
      (node (ref "R9") (pin "1") (pinfunction "1_1") (pintype "passive"))
    )
    (net (code "211") (name "VCC") (class "Default")
      (node (ref "ARDUINO_NANO") (pin "12") (pinfunction "5V_12") (pintype "power_in"))
      (node (ref "C11") (pin "1") (pinfunction "1_1") (pintype "passive"))
      (node (ref "C13") (pin "1") (pinfunction "1_1") (pintype "passive"))
      (node (ref "C15") (pin "1") (pinfunction "1_1") (pintype "passive"))
      (node (ref "C2") (pin "+") (pinfunction "+_+") (pintype "passive"))
      (node (ref "C3") (pin "1") (pinfunction "1_1") (pintype "passive"))
      (node (ref "C5") (pin "1") (pinfunction "1_1") (pintype "passive"))
      (node (ref "C7") (pin "1") (pinfunction "1_1") (pintype "passive"))
      (node (ref "C9") (pin "1") (pinfunction "1_1") (pintype "passive"))
      (node (ref "IC12") (pin "1") (pinfunction "A0_1") (pintype "bidirectional"))
      (node (ref "IC12") (pin "28") (pinfunction "VDD_28") (pintype "bidirectional"))
      (node (ref "IC15") (pin "24") (pinfunction "A5_24") (pintype "bidirectional"))
      (node (ref "IC15") (pin "28") (pinfunction "VDD_28") (pintype "bidirectional"))
      (node (ref "IC18") (pin "2") (pinfunction "A1_2") (pintype "bidirectional"))
      (node (ref "IC18") (pin "28") (pinfunction "VDD_28") (pintype "bidirectional"))
      (node (ref "IC24") (pin "1") (pinfunction "A0_1") (pintype "bidirectional"))
      (node (ref "IC24") (pin "2") (pinfunction "A1_2") (pintype "bidirectional"))
      (node (ref "IC24") (pin "28") (pinfunction "VDD_28") (pintype "bidirectional"))
      (node (ref "IC6") (pin "28") (pinfunction "VDD_28") (pintype "bidirectional"))
      (node (ref "IC9") (pin "1") (pinfunction "A0_1") (pintype "bidirectional"))
      (node (ref "IC9") (pin "24") (pinfunction "A5_24") (pintype "bidirectional"))
      (node (ref "IC9") (pin "28") (pinfunction "VDD_28") (pintype "bidirectional"))
      (node (ref "J1") (pin "4") (pinfunction "4_4") (pintype "passive"))
      (node (ref "J2") (pin "4") (pinfunction "4_4") (pintype "passive"))
      (node (ref "J31") (pin "1") (pinfunction "1_1") (pintype "passive"))
      (node (ref "J85") (pin "1") (pinfunction "1_1") (pintype "passive"))
      (node (ref "R1") (pin "2") (pinfunction "2_2") (pintype "passive"))
      (node (ref "R10") (pin "2") (pinfunction "2_2") (pintype "passive"))
      (node (ref "R11") (pin "2") (pinfunction "2_2") (pintype "passive"))
      (node (ref "R12") (pin "2") (pinfunction "2_2") (pintype "passive"))
      (node (ref "R13") (pin "2") (pinfunction "2_2") (pintype "passive"))
      (node (ref "R15") (pin "2") (pinfunction "2_2") (pintype "passive"))
      (node (ref "R16") (pin "2") (pinfunction "2_2") (pintype "passive"))
      (node (ref "R17") (pin "2") (pinfunction "2_2") (pintype "passive"))
      (node (ref "R19") (pin "2") (pinfunction "2_2") (pintype "passive"))
      (node (ref "R2") (pin "2") (pinfunction "2_2") (pintype "passive"))
      (node (ref "R3") (pin "2") (pinfunction "2_2") (pintype "passive"))
      (node (ref "R4") (pin "2") (pinfunction "2_2") (pintype "passive"))
      (node (ref "R5") (pin "2") (pinfunction "2_2") (pintype "passive"))
      (node (ref "R6") (pin "2") (pinfunction "2_2") (pintype "passive"))
      (node (ref "R7") (pin "2") (pinfunction "2_2") (pintype "passive"))
      (node (ref "R8") (pin "2") (pinfunction "2_2") (pintype "passive"))
      (node (ref "R9") (pin "2") (pinfunction "2_2") (pintype "passive"))
      (node (ref "U$1") (pin "5") (pinfunction "OUT_5") (pintype "bidirectional"))
      (node (ref "WEMOS1") (pin "5V") (pinfunction "5V_5V") (pintype "bidirectional"))
    )
    (net (code "212") (name "VIN") (class "Default")
      (node (ref "ARDUINO_NANO") (pin "15") (pinfunction "VIN_15") (pintype "power_in"))
    )
    (net (code "213") (name "unconnected-(ARDUINO_NANO-RX0-Pad17)") (class "Default")
      (node (ref "ARDUINO_NANO") (pin "17") (pinfunction "RX0_17") (pintype "bidirectional"))
    )
    (net (code "214") (name "unconnected-(ARDUINO_NANO-TX1-Pad16)") (class "Default")
      (node (ref "ARDUINO_NANO") (pin "16") (pinfunction "TX1_16") (pintype "bidirectional"))
    )
    (net (code "215") (name "unconnected-(ARDUINO_NANO-~{RESET}-Pad18)") (class "Default")
      (node (ref "ARDUINO_NANO") (pin "18") (pinfunction "~{RESET}_18") (pintype "input"))
    )
    (net (code "216") (name "unconnected-(IC5-Pad10)") (class "Default")
      (node (ref "IC5") (pin "10") (pinfunction "10_10") (pintype "bidirectional"))
    )
    (net (code "217") (name "unconnected-(IC8-Pad10)") (class "Default")
      (node (ref "IC8") (pin "10") (pinfunction "10_10") (pintype "bidirectional"))
    )
    (net (code "218") (name "unconnected-(IC11-Pad10)") (class "Default")
      (node (ref "IC11") (pin "10") (pinfunction "10_10") (pintype "bidirectional"))
    )
    (net (code "219") (name "unconnected-(IC14-Pad10)") (class "Default")
      (node (ref "IC14") (pin "10") (pinfunction "10_10") (pintype "bidirectional"))
    )
    (net (code "220") (name "unconnected-(IC17-Pad10)") (class "Default")
      (node (ref "IC17") (pin "10") (pinfunction "10_10") (pintype "bidirectional"))
    )
    (net (code "221") (name "unconnected-(IC23-Pad10)") (class "Default")
      (node (ref "IC23") (pin "10") (pinfunction "10_10") (pintype "bidirectional"))
    )
    (net (code "222") (name "unconnected-(J32-Pad1)") (class "Default")
      (node (ref "J32") (pin "1") (pinfunction "1_1") (pintype "passive"))
    )
    (net (code "223") (name "unconnected-(J33-Pad1)") (class "Default")
      (node (ref "J33") (pin "1") (pinfunction "1_1") (pintype "passive"))
    )
    (net (code "224") (name "unconnected-(J34-Pad1)") (class "Default")
      (node (ref "J34") (pin "1") (pinfunction "1_1") (pintype "passive"))
    )
    (net (code "225") (name "unconnected-(J35-Pad1)") (class "Default")
      (node (ref "J35") (pin "1") (pinfunction "1_1") (pintype "passive"))
    )
    (net (code "226") (name "unconnected-(J36-Pad1)") (class "Default")
      (node (ref "J36") (pin "1") (pinfunction "1_1") (pintype "passive"))
    )
    (net (code "227") (name "unconnected-(J37-Pad1)") (class "Default")
      (node (ref "J37") (pin "1") (pinfunction "1_1") (pintype "passive"))
    )
    (net (code "228") (name "unconnected-(J38-Pad1)") (class "Default")
      (node (ref "J38") (pin "1") (pinfunction "1_1") (pintype "passive"))
    )
    (net (code "229") (name "unconnected-(J39-Pad1)") (class "Default")
      (node (ref "J39") (pin "1") (pinfunction "1_1") (pintype "passive"))
    )
    (net (code "230") (name "unconnected-(J40-Pad1)") (class "Default")
      (node (ref "J40") (pin "1") (pinfunction "1_1") (pintype "passive"))
    )
    (net (code "231") (name "unconnected-(J41-Pad1)") (class "Default")
      (node (ref "J41") (pin "1") (pinfunction "1_1") (pintype "passive"))
    )
    (net (code "232") (name "unconnected-(J42-Pad1)") (class "Default")
      (node (ref "J42") (pin "1") (pinfunction "1_1") (pintype "passive"))
    )
    (net (code "233") (name "unconnected-(J43-Pad1)") (class "Default")
      (node (ref "J43") (pin "1") (pinfunction "1_1") (pintype "passive"))
    )
    (net (code "234") (name "unconnected-(J44-Pad1)") (class "Default")
      (node (ref "J44") (pin "1") (pinfunction "1_1") (pintype "passive"))
    )
    (net (code "235") (name "unconnected-(J45-Pad1)") (class "Default")
      (node (ref "J45") (pin "1") (pinfunction "1_1") (pintype "passive"))
    )
    (net (code "236") (name "unconnected-(J46-Pad1)") (class "Default")
      (node (ref "J46") (pin "1") (pinfunction "1_1") (pintype "passive"))
    )
    (net (code "237") (name "unconnected-(J47-Pad1)") (class "Default")
      (node (ref "J47") (pin "1") (pinfunction "1_1") (pintype "passive"))
    )
    (net (code "238") (name "unconnected-(J48-Pad1)") (class "Default")
      (node (ref "J48") (pin "1") (pinfunction "1_1") (pintype "passive"))
    )
    (net (code "239") (name "unconnected-(J49-Pad1)") (class "Default")
      (node (ref "J49") (pin "1") (pinfunction "1_1") (pintype "passive"))
    )
    (net (code "240") (name "unconnected-(J50-Pad1)") (class "Default")
      (node (ref "J50") (pin "1") (pinfunction "1_1") (pintype "passive"))
    )
    (net (code "241") (name "unconnected-(J51-Pad1)") (class "Default")
      (node (ref "J51") (pin "1") (pinfunction "1_1") (pintype "passive"))
    )
    (net (code "242") (name "unconnected-(J52-Pad1)") (class "Default")
      (node (ref "J52") (pin "1") (pinfunction "1_1") (pintype "passive"))
    )
    (net (code "243") (name "unconnected-(J53-Pad1)") (class "Default")
      (node (ref "J53") (pin "1") (pinfunction "1_1") (pintype "passive"))
    )
    (net (code "244") (name "unconnected-(J54-Pad1)") (class "Default")
      (node (ref "J54") (pin "1") (pinfunction "1_1") (pintype "passive"))
    )
    (net (code "245") (name "unconnected-(J55-Pad1)") (class "Default")
      (node (ref "J55") (pin "1") (pinfunction "1_1") (pintype "passive"))
    )
    (net (code "246") (name "unconnected-(J57-Pad1)") (class "Default")
      (node (ref "J57") (pin "1") (pinfunction "1_1") (pintype "passive"))
    )
    (net (code "247") (name "unconnected-(J58-Pad1)") (class "Default")
      (node (ref "J58") (pin "1") (pinfunction "1_1") (pintype "passive"))
    )
    (net (code "248") (name "unconnected-(J59-Pad1)") (class "Default")
      (node (ref "J59") (pin "1") (pinfunction "1_1") (pintype "passive"))
    )
    (net (code "249") (name "unconnected-(J60-Pad1)") (class "Default")
      (node (ref "J60") (pin "1") (pinfunction "1_1") (pintype "passive"))
    )
    (net (code "250") (name "unconnected-(J61-Pad1)") (class "Default")
      (node (ref "J61") (pin "1") (pinfunction "1_1") (pintype "passive"))
    )
    (net (code "251") (name "unconnected-(J62-Pad1)") (class "Default")
      (node (ref "J62") (pin "1") (pinfunction "1_1") (pintype "passive"))
    )
    (net (code "252") (name "unconnected-(J92-Pad1)") (class "Default")
      (node (ref "J92") (pin "1") (pinfunction "1_1") (pintype "passive"))
    )
    (net (code "253") (name "unconnected-(J93-Pad1)") (class "Default")
      (node (ref "J93") (pin "1") (pinfunction "1_1") (pintype "passive"))
    )
    (net (code "254") (name "unconnected-(J94-Pad1)") (class "Default")
      (node (ref "J94") (pin "1") (pinfunction "1_1") (pintype "passive"))
    )
    (net (code "255") (name "unconnected-(J95-Pad1)") (class "Default")
      (node (ref "J95") (pin "1") (pinfunction "1_1") (pintype "passive"))
    )
    (net (code "256") (name "unconnected-(J96-Pad1)") (class "Default")
      (node (ref "J96") (pin "1") (pinfunction "1_1") (pintype "passive"))
    )
    (net (code "257") (name "unconnected-(J97-Pad1)") (class "Default")
      (node (ref "J97") (pin "1") (pinfunction "1_1") (pintype "passive"))
    )
    (net (code "258") (name "unconnected-(J98-Pad1)") (class "Default")
      (node (ref "J98") (pin "1") (pinfunction "1_1") (pintype "passive"))
    )
    (net (code "259") (name "unconnected-(J99-Pad1)") (class "Default")
      (node (ref "J99") (pin "1") (pinfunction "1_1") (pintype "passive"))
    )
    (net (code "260") (name "unconnected-(J100-Pad1)") (class "Default")
      (node (ref "J100") (pin "1") (pinfunction "1_1") (pintype "passive"))
    )
    (net (code "261") (name "unconnected-(J101-Pad1)") (class "Default")
      (node (ref "J101") (pin "1") (pinfunction "1_1") (pintype "passive"))
    )
    (net (code "262") (name "unconnected-(J102-Pad1)") (class "Default")
      (node (ref "J102") (pin "1") (pinfunction "1_1") (pintype "passive"))
    )
    (net (code "263") (name "unconnected-(J103-Pad1)") (class "Default")
      (node (ref "J103") (pin "1") (pinfunction "1_1") (pintype "passive"))
    )
    (net (code "264") (name "unconnected-(J104-Pad1)") (class "Default")
      (node (ref "J104") (pin "1") (pinfunction "1_1") (pintype "passive"))
    )
    (net (code "265") (name "unconnected-(J105-Pad1)") (class "Default")
      (node (ref "J105") (pin "1") (pinfunction "1_1") (pintype "passive"))
    )
    (net (code "266") (name "unconnected-(J106-Pad1)") (class "Default")
      (node (ref "J106") (pin "1") (pinfunction "1_1") (pintype "passive"))
    )
    (net (code "267") (name "unconnected-(J107-Pad1)") (class "Default")
      (node (ref "J107") (pin "1") (pinfunction "1_1") (pintype "passive"))
    )
    (net (code "268") (name "unconnected-(J108-Pad1)") (class "Default")
      (node (ref "J108") (pin "1") (pinfunction "1_1") (pintype "passive"))
    )
    (net (code "269") (name "unconnected-(J109-Pad1)") (class "Default")
      (node (ref "J109") (pin "1") (pinfunction "1_1") (pintype "passive"))
    )
    (net (code "270") (name "unconnected-(J110-Pad1)") (class "Default")
      (node (ref "J110") (pin "1") (pinfunction "1_1") (pintype "passive"))
    )
    (net (code "271") (name "unconnected-(J111-Pad1)") (class "Default")
      (node (ref "J111") (pin "1") (pinfunction "1_1") (pintype "passive"))
    )
    (net (code "272") (name "unconnected-(J112-Pad1)") (class "Default")
      (node (ref "J112") (pin "1") (pinfunction "1_1") (pintype "passive"))
    )
    (net (code "273") (name "unconnected-(J113-Pad1)") (class "Default")
      (node (ref "J113") (pin "1") (pinfunction "1_1") (pintype "passive"))
    )
    (net (code "274") (name "unconnected-(J114-Pad1)") (class "Default")
      (node (ref "J114") (pin "1") (pinfunction "1_1") (pintype "passive"))
    )
    (net (code "275") (name "unconnected-(J115-Pad1)") (class "Default")
      (node (ref "J115") (pin "1") (pinfunction "1_1") (pintype "passive"))
    )
    (net (code "276") (name "unconnected-(J116-Pad1)") (class "Default")
      (node (ref "J116") (pin "1") (pinfunction "1_1") (pintype "passive"))
    )
    (net (code "277") (name "unconnected-(J117-Pad1)") (class "Default")
      (node (ref "J117") (pin "1") (pinfunction "1_1") (pintype "passive"))
    )
    (net (code "278") (name "unconnected-(J118-Pad1)") (class "Default")
      (node (ref "J118") (pin "1") (pinfunction "1_1") (pintype "passive"))
    )
    (net (code "279") (name "unconnected-(J119-Pad1)") (class "Default")
      (node (ref "J119") (pin "1") (pinfunction "1_1") (pintype "passive"))
    )
    (net (code "280") (name "unconnected-(J120-Pad1)") (class "Default")
      (node (ref "J120") (pin "1") (pinfunction "1_1") (pintype "passive"))
    )
    (net (code "281") (name "unconnected-(J121-Pad1)") (class "Default")
      (node (ref "J121") (pin "1") (pinfunction "1_1") (pintype "passive"))
    )
    (net (code "282") (name "unconnected-(J152-Pad1)") (class "Default")
      (node (ref "J152") (pin "1") (pinfunction "1_1") (pintype "passive"))
    )
    (net (code "283") (name "unconnected-(J153-Pad1)") (class "Default")
      (node (ref "J153") (pin "1") (pinfunction "1_1") (pintype "passive"))
    )
    (net (code "284") (name "unconnected-(J154-Pad1)") (class "Default")
      (node (ref "J154") (pin "1") (pinfunction "1_1") (pintype "passive"))
    )
    (net (code "285") (name "unconnected-(J155-Pad1)") (class "Default")
      (node (ref "J155") (pin "1") (pinfunction "1_1") (pintype "passive"))
    )
    (net (code "286") (name "unconnected-(J156-Pad1)") (class "Default")
      (node (ref "J156") (pin "1") (pinfunction "1_1") (pintype "passive"))
    )
    (net (code "287") (name "unconnected-(J157-Pad1)") (class "Default")
      (node (ref "J157") (pin "1") (pinfunction "1_1") (pintype "passive"))
    )
    (net (code "288") (name "unconnected-(J158-Pad1)") (class "Default")
      (node (ref "J158") (pin "1") (pinfunction "1_1") (pintype "passive"))
    )
    (net (code "289") (name "unconnected-(J159-Pad1)") (class "Default")
      (node (ref "J159") (pin "1") (pinfunction "1_1") (pintype "passive"))
    )
    (net (code "290") (name "unconnected-(J160-Pad1)") (class "Default")
      (node (ref "J160") (pin "1") (pinfunction "1_1") (pintype "passive"))
    )
    (net (code "291") (name "unconnected-(J161-Pad1)") (class "Default")
      (node (ref "J161") (pin "1") (pinfunction "1_1") (pintype "passive"))
    )
    (net (code "292") (name "unconnected-(J162-Pad1)") (class "Default")
      (node (ref "J162") (pin "1") (pinfunction "1_1") (pintype "passive"))
    )
    (net (code "293") (name "unconnected-(J163-Pad1)") (class "Default")
      (node (ref "J163") (pin "1") (pinfunction "1_1") (pintype "passive"))
    )
    (net (code "294") (name "unconnected-(J164-Pad1)") (class "Default")
      (node (ref "J164") (pin "1") (pinfunction "1_1") (pintype "passive"))
    )
    (net (code "295") (name "unconnected-(J165-Pad1)") (class "Default")
      (node (ref "J165") (pin "1") (pinfunction "1_1") (pintype "passive"))
    )
    (net (code "296") (name "unconnected-(J166-Pad1)") (class "Default")
      (node (ref "J166") (pin "1") (pinfunction "1_1") (pintype "passive"))
    )
    (net (code "297") (name "unconnected-(J167-Pad1)") (class "Default")
      (node (ref "J167") (pin "1") (pinfunction "1_1") (pintype "passive"))
    )
    (net (code "298") (name "unconnected-(J168-Pad1)") (class "Default")
      (node (ref "J168") (pin "1") (pinfunction "1_1") (pintype "passive"))
    )
    (net (code "299") (name "unconnected-(J169-Pad1)") (class "Default")
      (node (ref "J169") (pin "1") (pinfunction "1_1") (pintype "passive"))
    )
    (net (code "300") (name "unconnected-(J170-Pad1)") (class "Default")
      (node (ref "J170") (pin "1") (pinfunction "1_1") (pintype "passive"))
    )
    (net (code "301") (name "unconnected-(J171-Pad1)") (class "Default")
      (node (ref "J171") (pin "1") (pinfunction "1_1") (pintype "passive"))
    )
    (net (code "302") (name "unconnected-(J172-Pad1)") (class "Default")
      (node (ref "J172") (pin "1") (pinfunction "1_1") (pintype "passive"))
    )
    (net (code "303") (name "unconnected-(J173-Pad1)") (class "Default")
      (node (ref "J173") (pin "1") (pinfunction "1_1") (pintype "passive"))
    )
    (net (code "304") (name "unconnected-(J174-Pad1)") (class "Default")
      (node (ref "J174") (pin "1") (pinfunction "1_1") (pintype "passive"))
    )
    (net (code "305") (name "unconnected-(J175-Pad1)") (class "Default")
      (node (ref "J175") (pin "1") (pinfunction "1_1") (pintype "passive"))
    )
    (net (code "306") (name "unconnected-(J176-Pad1)") (class "Default")
      (node (ref "J176") (pin "1") (pinfunction "1_1") (pintype "passive"))
    )
    (net (code "307") (name "unconnected-(J177-Pad1)") (class "Default")
      (node (ref "J177") (pin "1") (pinfunction "1_1") (pintype "passive"))
    )
    (net (code "308") (name "unconnected-(J178-Pad1)") (class "Default")
      (node (ref "J178") (pin "1") (pinfunction "1_1") (pintype "passive"))
    )
    (net (code "309") (name "unconnected-(J179-Pad1)") (class "Default")
      (node (ref "J179") (pin "1") (pinfunction "1_1") (pintype "passive"))
    )
    (net (code "310") (name "unconnected-(J180-Pad1)") (class "Default")
      (node (ref "J180") (pin "1") (pinfunction "1_1") (pintype "passive"))
    )
    (net (code "311") (name "unconnected-(J181-Pad1)") (class "Default")
      (node (ref "J181") (pin "1") (pinfunction "1_1") (pintype "passive"))
    )
    (net (code "312") (name "unconnected-(J212-Pad1)") (class "Default")
      (node (ref "J212") (pin "1") (pinfunction "1_1") (pintype "passive"))
    )
    (net (code "313") (name "unconnected-(J213-Pad1)") (class "Default")
      (node (ref "J213") (pin "1") (pinfunction "1_1") (pintype "passive"))
    )
    (net (code "314") (name "unconnected-(J214-Pad1)") (class "Default")
      (node (ref "J214") (pin "1") (pinfunction "1_1") (pintype "passive"))
    )
    (net (code "315") (name "unconnected-(J215-Pad1)") (class "Default")
      (node (ref "J215") (pin "1") (pinfunction "1_1") (pintype "passive"))
    )
    (net (code "316") (name "unconnected-(J216-Pad1)") (class "Default")
      (node (ref "J216") (pin "1") (pinfunction "1_1") (pintype "passive"))
    )
    (net (code "317") (name "unconnected-(J217-Pad1)") (class "Default")
      (node (ref "J217") (pin "1") (pinfunction "1_1") (pintype "passive"))
    )
    (net (code "318") (name "unconnected-(J218-Pad1)") (class "Default")
      (node (ref "J218") (pin "1") (pinfunction "1_1") (pintype "passive"))
    )
    (net (code "319") (name "unconnected-(J219-Pad1)") (class "Default")
      (node (ref "J219") (pin "1") (pinfunction "1_1") (pintype "passive"))
    )
    (net (code "320") (name "unconnected-(J220-Pad1)") (class "Default")
      (node (ref "J220") (pin "1") (pinfunction "1_1") (pintype "passive"))
    )
    (net (code "321") (name "unconnected-(J221-Pad1)") (class "Default")
      (node (ref "J221") (pin "1") (pinfunction "1_1") (pintype "passive"))
    )
    (net (code "322") (name "unconnected-(J222-Pad1)") (class "Default")
      (node (ref "J222") (pin "1") (pinfunction "1_1") (pintype "passive"))
    )
    (net (code "323") (name "unconnected-(J223-Pad1)") (class "Default")
      (node (ref "J223") (pin "1") (pinfunction "1_1") (pintype "passive"))
    )
    (net (code "324") (name "unconnected-(J224-Pad1)") (class "Default")
      (node (ref "J224") (pin "1") (pinfunction "1_1") (pintype "passive"))
    )
    (net (code "325") (name "unconnected-(J225-Pad1)") (class "Default")
      (node (ref "J225") (pin "1") (pinfunction "1_1") (pintype "passive"))
    )
    (net (code "326") (name "unconnected-(J226-Pad1)") (class "Default")
      (node (ref "J226") (pin "1") (pinfunction "1_1") (pintype "passive"))
    )
    (net (code "327") (name "unconnected-(J227-Pad1)") (class "Default")
      (node (ref "J227") (pin "1") (pinfunction "1_1") (pintype "passive"))
    )
    (net (code "328") (name "unconnected-(J228-Pad1)") (class "Default")
      (node (ref "J228") (pin "1") (pinfunction "1_1") (pintype "passive"))
    )
    (net (code "329") (name "unconnected-(J229-Pad1)") (class "Default")
      (node (ref "J229") (pin "1") (pinfunction "1_1") (pintype "passive"))
    )
    (net (code "330") (name "unconnected-(J230-Pad1)") (class "Default")
      (node (ref "J230") (pin "1") (pinfunction "1_1") (pintype "passive"))
    )
    (net (code "331") (name "unconnected-(J231-Pad1)") (class "Default")
      (node (ref "J231") (pin "1") (pinfunction "1_1") (pintype "passive"))
    )
    (net (code "332") (name "unconnected-(J232-Pad1)") (class "Default")
      (node (ref "J232") (pin "1") (pinfunction "1_1") (pintype "passive"))
    )
    (net (code "333") (name "unconnected-(J233-Pad1)") (class "Default")
      (node (ref "J233") (pin "1") (pinfunction "1_1") (pintype "passive"))
    )
    (net (code "334") (name "unconnected-(J234-Pad1)") (class "Default")
      (node (ref "J234") (pin "1") (pinfunction "1_1") (pintype "passive"))
    )
    (net (code "335") (name "unconnected-(J235-Pad1)") (class "Default")
      (node (ref "J235") (pin "1") (pinfunction "1_1") (pintype "passive"))
    )
    (net (code "336") (name "unconnected-(J236-Pad1)") (class "Default")
      (node (ref "J236") (pin "1") (pinfunction "1_1") (pintype "passive"))
    )
    (net (code "337") (name "unconnected-(J237-Pad1)") (class "Default")
      (node (ref "J237") (pin "1") (pinfunction "1_1") (pintype "passive"))
    )
    (net (code "338") (name "unconnected-(J238-Pad1)") (class "Default")
      (node (ref "J238") (pin "1") (pinfunction "1_1") (pintype "passive"))
    )
    (net (code "339") (name "unconnected-(J239-Pad1)") (class "Default")
      (node (ref "J239") (pin "1") (pinfunction "1_1") (pintype "passive"))
    )
    (net (code "340") (name "unconnected-(J240-Pad1)") (class "Default")
      (node (ref "J240") (pin "1") (pinfunction "1_1") (pintype "passive"))
    )
    (net (code "341") (name "unconnected-(J241-Pad1)") (class "Default")
      (node (ref "J241") (pin "1") (pinfunction "1_1") (pintype "passive"))
    )
    (net (code "342") (name "unconnected-(J242-Pad1)") (class "Default")
      (node (ref "J242") (pin "1") (pinfunction "1_1") (pintype "passive"))
    )
    (net (code "343") (name "unconnected-(J243-Pad1)") (class "Default")
      (node (ref "J243") (pin "1") (pinfunction "1_1") (pintype "passive"))
    )
    (net (code "344") (name "unconnected-(J244-Pad1)") (class "Default")
      (node (ref "J244") (pin "1") (pinfunction "1_1") (pintype "passive"))
    )
    (net (code "345") (name "unconnected-(J245-Pad1)") (class "Default")
      (node (ref "J245") (pin "1") (pinfunction "1_1") (pintype "passive"))
    )
    (net (code "346") (name "unconnected-(J246-Pad1)") (class "Default")
      (node (ref "J246") (pin "1") (pinfunction "1_1") (pintype "passive"))
    )
    (net (code "347") (name "unconnected-(J247-Pad1)") (class "Default")
      (node (ref "J247") (pin "1") (pinfunction "1_1") (pintype "passive"))
    )
    (net (code "348") (name "unconnected-(J248-Pad1)") (class "Default")
      (node (ref "J248") (pin "1") (pinfunction "1_1") (pintype "passive"))
    )
    (net (code "349") (name "unconnected-(J249-Pad1)") (class "Default")
      (node (ref "J249") (pin "1") (pinfunction "1_1") (pintype "passive"))
    )
    (net (code "350") (name "unconnected-(J250-Pad1)") (class "Default")
      (node (ref "J250") (pin "1") (pinfunction "1_1") (pintype "passive"))
    )
    (net (code "351") (name "unconnected-(J251-Pad1)") (class "Default")
      (node (ref "J251") (pin "1") (pinfunction "1_1") (pintype "passive"))
    )
    (net (code "352") (name "unconnected-(J252-Pad1)") (class "Default")
      (node (ref "J252") (pin "1") (pinfunction "1_1") (pintype "passive"))
    )
    (net (code "353") (name "unconnected-(J253-Pad1)") (class "Default")
      (node (ref "J253") (pin "1") (pinfunction "1_1") (pintype "passive"))
    )
    (net (code "354") (name "unconnected-(J254-Pad1)") (class "Default")
      (node (ref "J254") (pin "1") (pinfunction "1_1") (pintype "passive"))
    )
    (net (code "355") (name "unconnected-(J255-Pad1)") (class "Default")
      (node (ref "J255") (pin "1") (pinfunction "1_1") (pintype "passive"))
    )
    (net (code "356") (name "unconnected-(J256-Pad1)") (class "Default")
      (node (ref "J256") (pin "1") (pinfunction "1_1") (pintype "passive"))
    )
    (net (code "357") (name "unconnected-(J257-Pad1)") (class "Default")
      (node (ref "J257") (pin "1") (pinfunction "1_1") (pintype "passive"))
    )
    (net (code "358") (name "unconnected-(J258-Pad1)") (class "Default")
      (node (ref "J258") (pin "1") (pinfunction "1_1") (pintype "passive"))
    )
    (net (code "359") (name "unconnected-(J259-Pad1)") (class "Default")
      (node (ref "J259") (pin "1") (pinfunction "1_1") (pintype "passive"))
    )
    (net (code "360") (name "unconnected-(J260-Pad1)") (class "Default")
      (node (ref "J260") (pin "1") (pinfunction "1_1") (pintype "passive"))
    )
    (net (code "361") (name "unconnected-(J261-Pad1)") (class "Default")
      (node (ref "J261") (pin "1") (pinfunction "1_1") (pintype "passive"))
    )
    (net (code "362") (name "unconnected-(J262-Pad1)") (class "Default")
      (node (ref "J262") (pin "1") (pinfunction "1_1") (pintype "passive"))
    )
    (net (code "363") (name "unconnected-(J263-Pad1)") (class "Default")
      (node (ref "J263") (pin "1") (pinfunction "1_1") (pintype "passive"))
    )
    (net (code "364") (name "unconnected-(J264-Pad1)") (class "Default")
      (node (ref "J264") (pin "1") (pinfunction "1_1") (pintype "passive"))
    )
    (net (code "365") (name "unconnected-(J265-Pad1)") (class "Default")
      (node (ref "J265") (pin "1") (pinfunction "1_1") (pintype "passive"))
    )
    (net (code "366") (name "unconnected-(J266-Pad1)") (class "Default")
      (node (ref "J266") (pin "1") (pinfunction "1_1") (pintype "passive"))
    )
    (net (code "367") (name "unconnected-(J267-Pad1)") (class "Default")
      (node (ref "J267") (pin "1") (pinfunction "1_1") (pintype "passive"))
    )
    (net (code "368") (name "unconnected-(J268-Pad1)") (class "Default")
      (node (ref "J268") (pin "1") (pinfunction "1_1") (pintype "passive"))
    )
    (net (code "369") (name "unconnected-(J269-Pad1)") (class "Default")
      (node (ref "J269") (pin "1") (pinfunction "1_1") (pintype "passive"))
    )
    (net (code "370") (name "unconnected-(J270-Pad1)") (class "Default")
      (node (ref "J270") (pin "1") (pinfunction "1_1") (pintype "passive"))
    )
    (net (code "371") (name "unconnected-(J271-Pad1)") (class "Default")
      (node (ref "J271") (pin "1") (pinfunction "1_1") (pintype "passive"))
    )
    (net (code "372") (name "unconnected-(J272-Pad1)") (class "Default")
      (node (ref "J272") (pin "1") (pinfunction "1_1") (pintype "passive"))
    )
    (net (code "373") (name "unconnected-(J273-Pad1)") (class "Default")
      (node (ref "J273") (pin "1") (pinfunction "1_1") (pintype "passive"))
    )
    (net (code "374") (name "unconnected-(J274-Pad1)") (class "Default")
      (node (ref "J274") (pin "1") (pinfunction "1_1") (pintype "passive"))
    )
    (net (code "375") (name "unconnected-(J275-Pad1)") (class "Default")
      (node (ref "J275") (pin "1") (pinfunction "1_1") (pintype "passive"))
    )
    (net (code "376") (name "unconnected-(J276-Pad1)") (class "Default")
      (node (ref "J276") (pin "1") (pinfunction "1_1") (pintype "passive"))
    )
    (net (code "377") (name "unconnected-(J277-Pad1)") (class "Default")
      (node (ref "J277") (pin "1") (pinfunction "1_1") (pintype "passive"))
    )
    (net (code "378") (name "unconnected-(J278-Pad1)") (class "Default")
      (node (ref "J278") (pin "1") (pinfunction "1_1") (pintype "passive"))
    )
    (net (code "379") (name "unconnected-(J279-Pad1)") (class "Default")
      (node (ref "J279") (pin "1") (pinfunction "1_1") (pintype "passive"))
    )
    (net (code "380") (name "unconnected-(J280-Pad1)") (class "Default")
      (node (ref "J280") (pin "1") (pinfunction "1_1") (pintype "passive"))
    )
    (net (code "381") (name "unconnected-(J281-Pad1)") (class "Default")
      (node (ref "J281") (pin "1") (pinfunction "1_1") (pintype "passive"))
    )
    (net (code "382") (name "unconnected-(J282-Pad1)") (class "Default")
      (node (ref "J282") (pin "1") (pinfunction "1_1") (pintype "passive"))
    )
    (net (code "383") (name "unconnected-(J283-Pad1)") (class "Default")
      (node (ref "J283") (pin "1") (pinfunction "1_1") (pintype "passive"))
    )
    (net (code "384") (name "unconnected-(J284-Pad1)") (class "Default")
      (node (ref "J284") (pin "1") (pinfunction "1_1") (pintype "passive"))
    )
    (net (code "385") (name "unconnected-(J285-Pad1)") (class "Default")
      (node (ref "J285") (pin "1") (pinfunction "1_1") (pintype "passive"))
    )
    (net (code "386") (name "unconnected-(J286-Pad1)") (class "Default")
      (node (ref "J286") (pin "1") (pinfunction "1_1") (pintype "passive"))
    )
    (net (code "387") (name "unconnected-(J287-Pad1)") (class "Default")
      (node (ref "J287") (pin "1") (pinfunction "1_1") (pintype "passive"))
    )
    (net (code "388") (name "unconnected-(J288-Pad1)") (class "Default")
      (node (ref "J288") (pin "1") (pinfunction "1_1") (pintype "passive"))
    )
    (net (code "389") (name "unconnected-(J289-Pad1)") (class "Default")
      (node (ref "J289") (pin "1") (pinfunction "1_1") (pintype "passive"))
    )
    (net (code "390") (name "unconnected-(J290-Pad1)") (class "Default")
      (node (ref "J290") (pin "1") (pinfunction "1_1") (pintype "passive"))
    )
    (net (code "391") (name "unconnected-(J291-Pad1)") (class "Default")
      (node (ref "J291") (pin "1") (pinfunction "1_1") (pintype "passive"))
    )
    (net (code "392") (name "unconnected-(J292-Pad1)") (class "Default")
      (node (ref "J292") (pin "1") (pinfunction "1_1") (pintype "passive"))
    )
    (net (code "393") (name "unconnected-(J293-Pad1)") (class "Default")
      (node (ref "J293") (pin "1") (pinfunction "1_1") (pintype "passive"))
    )
    (net (code "394") (name "unconnected-(J294-Pad1)") (class "Default")
      (node (ref "J294") (pin "1") (pinfunction "1_1") (pintype "passive"))
    )
    (net (code "395") (name "unconnected-(J295-Pad1)") (class "Default")
      (node (ref "J295") (pin "1") (pinfunction "1_1") (pintype "passive"))
    )
    (net (code "396") (name "unconnected-(J296-Pad1)") (class "Default")
      (node (ref "J296") (pin "1") (pinfunction "1_1") (pintype "passive"))
    )
    (net (code "397") (name "unconnected-(J297-Pad1)") (class "Default")
      (node (ref "J297") (pin "1") (pinfunction "1_1") (pintype "passive"))
    )
    (net (code "398") (name "unconnected-(J298-Pad1)") (class "Default")
      (node (ref "J298") (pin "1") (pinfunction "1_1") (pintype "passive"))
    )
    (net (code "399") (name "unconnected-(J299-Pad1)") (class "Default")
      (node (ref "J299") (pin "1") (pinfunction "1_1") (pintype "passive"))
    )
    (net (code "400") (name "unconnected-(J300-Pad1)") (class "Default")
      (node (ref "J300") (pin "1") (pinfunction "1_1") (pintype "passive"))
    )
    (net (code "401") (name "unconnected-(J301-Pad1)") (class "Default")
      (node (ref "J301") (pin "1") (pinfunction "1_1") (pintype "passive"))
    )
    (net (code "402") (name "unconnected-(J302-Pad1)") (class "Default")
      (node (ref "J302") (pin "1") (pinfunction "1_1") (pintype "passive"))
    )
    (net (code "403") (name "unconnected-(J303-Pad1)") (class "Default")
      (node (ref "J303") (pin "1") (pinfunction "1_1") (pintype "passive"))
    )
    (net (code "404") (name "unconnected-(J304-Pad1)") (class "Default")
      (node (ref "J304") (pin "1") (pinfunction "1_1") (pintype "passive"))
    )
    (net (code "405") (name "unconnected-(J305-Pad1)") (class "Default")
      (node (ref "J305") (pin "1") (pinfunction "1_1") (pintype "passive"))
    )
    (net (code "406") (name "unconnected-(J306-Pad1)") (class "Default")
      (node (ref "J306") (pin "1") (pinfunction "1_1") (pintype "passive"))
    )
    (net (code "407") (name "unconnected-(J307-Pad1)") (class "Default")
      (node (ref "J307") (pin "1") (pinfunction "1_1") (pintype "passive"))
    )
    (net (code "408") (name "unconnected-(J308-Pad1)") (class "Default")
      (node (ref "J308") (pin "1") (pinfunction "1_1") (pintype "passive"))
    )
    (net (code "409") (name "unconnected-(J309-Pad1)") (class "Default")
      (node (ref "J309") (pin "1") (pinfunction "1_1") (pintype "passive"))
    )
    (net (code "410") (name "unconnected-(J310-Pad1)") (class "Default")
      (node (ref "J310") (pin "1") (pinfunction "1_1") (pintype "passive"))
    )
    (net (code "411") (name "unconnected-(J311-Pad1)") (class "Default")
      (node (ref "J311") (pin "1") (pinfunction "1_1") (pintype "passive"))
    )
    (net (code "412") (name "unconnected-(J312-Pad1)") (class "Default")
      (node (ref "J312") (pin "1") (pinfunction "1_1") (pintype "passive"))
    )
    (net (code "413") (name "unconnected-(J313-Pad1)") (class "Default")
      (node (ref "J313") (pin "1") (pinfunction "1_1") (pintype "passive"))
    )
    (net (code "414") (name "unconnected-(J314-Pad1)") (class "Default")
      (node (ref "J314") (pin "1") (pinfunction "1_1") (pintype "passive"))
    )
    (net (code "415") (name "unconnected-(J315-Pad1)") (class "Default")
      (node (ref "J315") (pin "1") (pinfunction "1_1") (pintype "passive"))
    )
    (net (code "416") (name "unconnected-(J316-Pad1)") (class "Default")
      (node (ref "J316") (pin "1") (pinfunction "1_1") (pintype "passive"))
    )
    (net (code "417") (name "unconnected-(J317-Pad1)") (class "Default")
      (node (ref "J317") (pin "1") (pinfunction "1_1") (pintype "passive"))
    )
    (net (code "418") (name "unconnected-(J318-Pad1)") (class "Default")
      (node (ref "J318") (pin "1") (pinfunction "1_1") (pintype "passive"))
    )
    (net (code "419") (name "unconnected-(J319-Pad1)") (class "Default")
      (node (ref "J319") (pin "1") (pinfunction "1_1") (pintype "passive"))
    )
    (net (code "420") (name "unconnected-(J320-Pad1)") (class "Default")
      (node (ref "J320") (pin "1") (pinfunction "1_1") (pintype "passive"))
    )
    (net (code "421") (name "unconnected-(J321-Pad1)") (class "Default")
      (node (ref "J321") (pin "1") (pinfunction "1_1") (pintype "passive"))
    )
    (net (code "422") (name "unconnected-(J322-Pad1)") (class "Default")
      (node (ref "J322") (pin "1") (pinfunction "1_1") (pintype "passive"))
    )
    (net (code "423") (name "unconnected-(J323-Pad1)") (class "Default")
      (node (ref "J323") (pin "1") (pinfunction "1_1") (pintype "passive"))
    )
    (net (code "424") (name "unconnected-(J324-Pad1)") (class "Default")
      (node (ref "J324") (pin "1") (pinfunction "1_1") (pintype "passive"))
    )
    (net (code "425") (name "unconnected-(J325-Pad1)") (class "Default")
      (node (ref "J325") (pin "1") (pinfunction "1_1") (pintype "passive"))
    )
    (net (code "426") (name "unconnected-(J326-Pad1)") (class "Default")
      (node (ref "J326") (pin "1") (pinfunction "1_1") (pintype "passive"))
    )
    (net (code "427") (name "unconnected-(J327-Pad1)") (class "Default")
      (node (ref "J327") (pin "1") (pinfunction "1_1") (pintype "passive"))
    )
    (net (code "428") (name "unconnected-(J328-Pad1)") (class "Default")
      (node (ref "J328") (pin "1") (pinfunction "1_1") (pintype "passive"))
    )
    (net (code "429") (name "unconnected-(J329-Pad1)") (class "Default")
      (node (ref "J329") (pin "1") (pinfunction "1_1") (pintype "passive"))
    )
    (net (code "430") (name "unconnected-(J330-Pad1)") (class "Default")
      (node (ref "J330") (pin "1") (pinfunction "1_1") (pintype "passive"))
    )
    (net (code "431") (name "unconnected-(J331-Pad1)") (class "Default")
      (node (ref "J331") (pin "1") (pinfunction "1_1") (pintype "passive"))
    )
    (net (code "432") (name "unconnected-(J332-Pad1)") (class "Default")
      (node (ref "J332") (pin "1") (pinfunction "1_1") (pintype "passive"))
    )
    (net (code "433") (name "unconnected-(J333-Pad1)") (class "Default")
      (node (ref "J333") (pin "1") (pinfunction "1_1") (pintype "passive"))
    )
    (net (code "434") (name "unconnected-(J334-Pad1)") (class "Default")
      (node (ref "J334") (pin "1") (pinfunction "1_1") (pintype "passive"))
    )
    (net (code "435") (name "unconnected-(J335-Pad1)") (class "Default")
      (node (ref "J335") (pin "1") (pinfunction "1_1") (pintype "passive"))
    )
    (net (code "436") (name "unconnected-(J336-Pad1)") (class "Default")
      (node (ref "J336") (pin "1") (pinfunction "1_1") (pintype "passive"))
    )
    (net (code "437") (name "unconnected-(J337-Pad1)") (class "Default")
      (node (ref "J337") (pin "1") (pinfunction "1_1") (pintype "passive"))
    )
    (net (code "438") (name "unconnected-(J338-Pad1)") (class "Default")
      (node (ref "J338") (pin "1") (pinfunction "1_1") (pintype "passive"))
    )
    (net (code "439") (name "unconnected-(J339-Pad1)") (class "Default")
      (node (ref "J339") (pin "1") (pinfunction "1_1") (pintype "passive"))
    )
    (net (code "440") (name "unconnected-(J340-Pad1)") (class "Default")
      (node (ref "J340") (pin "1") (pinfunction "1_1") (pintype "passive"))
    )
    (net (code "441") (name "unconnected-(J341-Pad1)") (class "Default")
      (node (ref "J341") (pin "1") (pinfunction "1_1") (pintype "passive"))
    )
    (net (code "442") (name "unconnected-(J342-Pad1)") (class "Default")
      (node (ref "J342") (pin "1") (pinfunction "1_1") (pintype "passive"))
    )
    (net (code "443") (name "unconnected-(J343-Pad1)") (class "Default")
      (node (ref "J343") (pin "1") (pinfunction "1_1") (pintype "passive"))
    )
    (net (code "444") (name "unconnected-(J344-Pad1)") (class "Default")
      (node (ref "J344") (pin "1") (pinfunction "1_1") (pintype "passive"))
    )
    (net (code "445") (name "unconnected-(J345-Pad1)") (class "Default")
      (node (ref "J345") (pin "1") (pinfunction "1_1") (pintype "passive"))
    )
    (net (code "446") (name "unconnected-(J346-Pad1)") (class "Default")
      (node (ref "J346") (pin "1") (pinfunction "1_1") (pintype "passive"))
    )
    (net (code "447") (name "unconnected-(J347-Pad1)") (class "Default")
      (node (ref "J347") (pin "1") (pinfunction "1_1") (pintype "passive"))
    )
    (net (code "448") (name "unconnected-(J348-Pad1)") (class "Default")
      (node (ref "J348") (pin "1") (pinfunction "1_1") (pintype "passive"))
    )
    (net (code "449") (name "unconnected-(J349-Pad1)") (class "Default")
      (node (ref "J349") (pin "1") (pinfunction "1_1") (pintype "passive"))
    )
    (net (code "450") (name "unconnected-(J350-Pad1)") (class "Default")
      (node (ref "J350") (pin "1") (pinfunction "1_1") (pintype "passive"))
    )
    (net (code "451") (name "unconnected-(J351-Pad1)") (class "Default")
      (node (ref "J351") (pin "1") (pinfunction "1_1") (pintype "passive"))
    )
    (net (code "452") (name "unconnected-(J352-Pad1)") (class "Default")
      (node (ref "J352") (pin "1") (pinfunction "1_1") (pintype "passive"))
    )
    (net (code "453") (name "unconnected-(J353-Pad1)") (class "Default")
      (node (ref "J353") (pin "1") (pinfunction "1_1") (pintype "passive"))
    )
    (net (code "454") (name "unconnected-(J354-Pad1)") (class "Default")
      (node (ref "J354") (pin "1") (pinfunction "1_1") (pintype "passive"))
    )
    (net (code "455") (name "unconnected-(J355-Pad1)") (class "Default")
      (node (ref "J355") (pin "1") (pinfunction "1_1") (pintype "passive"))
    )
    (net (code "456") (name "unconnected-(J356-Pad1)") (class "Default")
      (node (ref "J356") (pin "1") (pinfunction "1_1") (pintype "passive"))
    )
    (net (code "457") (name "unconnected-(J357-Pad1)") (class "Default")
      (node (ref "J357") (pin "1") (pinfunction "1_1") (pintype "passive"))
    )
    (net (code "458") (name "unconnected-(J358-Pad1)") (class "Default")
      (node (ref "J358") (pin "1") (pinfunction "1_1") (pintype "passive"))
    )
    (net (code "459") (name "unconnected-(J359-Pad1)") (class "Default")
      (node (ref "J359") (pin "1") (pinfunction "1_1") (pintype "passive"))
    )
    (net (code "460") (name "unconnected-(J360-Pad1)") (class "Default")
      (node (ref "J360") (pin "1") (pinfunction "1_1") (pintype "passive"))
    )
    (net (code "461") (name "unconnected-(J361-Pad1)") (class "Default")
      (node (ref "J361") (pin "1") (pinfunction "1_1") (pintype "passive"))
    )
    (net (code "462") (name "unconnected-(J362-Pad1)") (class "Default")
      (node (ref "J362") (pin "1") (pinfunction "1_1") (pintype "passive"))
    )
    (net (code "463") (name "unconnected-(J363-Pad1)") (class "Default")
      (node (ref "J363") (pin "1") (pinfunction "1_1") (pintype "passive"))
    )
    (net (code "464") (name "unconnected-(J364-Pad1)") (class "Default")
      (node (ref "J364") (pin "1") (pinfunction "1_1") (pintype "passive"))
    )
    (net (code "465") (name "unconnected-(J365-Pad1)") (class "Default")
      (node (ref "J365") (pin "1") (pinfunction "1_1") (pintype "passive"))
    )
    (net (code "466") (name "unconnected-(J366-Pad1)") (class "Default")
      (node (ref "J366") (pin "1") (pinfunction "1_1") (pintype "passive"))
    )
    (net (code "467") (name "unconnected-(J367-Pad1)") (class "Default")
      (node (ref "J367") (pin "1") (pinfunction "1_1") (pintype "passive"))
    )
    (net (code "468") (name "unconnected-(J368-Pad1)") (class "Default")
      (node (ref "J368") (pin "1") (pinfunction "1_1") (pintype "passive"))
    )
    (net (code "469") (name "unconnected-(J369-Pad1)") (class "Default")
      (node (ref "J369") (pin "1") (pinfunction "1_1") (pintype "passive"))
    )
    (net (code "470") (name "unconnected-(J370-Pad1)") (class "Default")
      (node (ref "J370") (pin "1") (pinfunction "1_1") (pintype "passive"))
    )
    (net (code "471") (name "unconnected-(J371-Pad1)") (class "Default")
      (node (ref "J371") (pin "1") (pinfunction "1_1") (pintype "passive"))
    )
    (net (code "472") (name "unconnected-(J372-Pad1)") (class "Default")
      (node (ref "J372") (pin "1") (pinfunction "1_1") (pintype "passive"))
    )
    (net (code "473") (name "unconnected-(J373-Pad1)") (class "Default")
      (node (ref "J373") (pin "1") (pinfunction "1_1") (pintype "passive"))
    )
    (net (code "474") (name "unconnected-(J374-Pad1)") (class "Default")
      (node (ref "J374") (pin "1") (pinfunction "1_1") (pintype "passive"))
    )
    (net (code "475") (name "unconnected-(J375-Pad1)") (class "Default")
      (node (ref "J375") (pin "1") (pinfunction "1_1") (pintype "passive"))
    )
    (net (code "476") (name "unconnected-(J376-Pad1)") (class "Default")
      (node (ref "J376") (pin "1") (pinfunction "1_1") (pintype "passive"))
    )
    (net (code "477") (name "unconnected-(J377-Pad1)") (class "Default")
      (node (ref "J377") (pin "1") (pinfunction "1_1") (pintype "passive"))
    )
    (net (code "478") (name "unconnected-(J378-Pad1)") (class "Default")
      (node (ref "J378") (pin "1") (pinfunction "1_1") (pintype "passive"))
    )
    (net (code "479") (name "unconnected-(J379-Pad1)") (class "Default")
      (node (ref "J379") (pin "1") (pinfunction "1_1") (pintype "passive"))
    )
    (net (code "480") (name "unconnected-(J380-Pad1)") (class "Default")
      (node (ref "J380") (pin "1") (pinfunction "1_1") (pintype "passive"))
    )
    (net (code "481") (name "unconnected-(J381-Pad1)") (class "Default")
      (node (ref "J381") (pin "1") (pinfunction "1_1") (pintype "passive"))
    )
    (net (code "482") (name "unconnected-(J382-Pad1)") (class "Default")
      (node (ref "J382") (pin "1") (pinfunction "1_1") (pintype "passive"))
    )
    (net (code "483") (name "unconnected-(J383-Pad1)") (class "Default")
      (node (ref "J383") (pin "1") (pinfunction "1_1") (pintype "passive"))
    )
    (net (code "484") (name "unconnected-(J384-Pad1)") (class "Default")
      (node (ref "J384") (pin "1") (pinfunction "1_1") (pintype "passive"))
    )
    (net (code "485") (name "unconnected-(J385-Pad1)") (class "Default")
      (node (ref "J385") (pin "1") (pinfunction "1_1") (pintype "passive"))
    )
    (net (code "486") (name "unconnected-(J386-Pad1)") (class "Default")
      (node (ref "J386") (pin "1") (pinfunction "1_1") (pintype "passive"))
    )
    (net (code "487") (name "unconnected-(J387-Pad1)") (class "Default")
      (node (ref "J387") (pin "1") (pinfunction "1_1") (pintype "passive"))
    )
    (net (code "488") (name "unconnected-(J388-Pad1)") (class "Default")
      (node (ref "J388") (pin "1") (pinfunction "1_1") (pintype "passive"))
    )
    (net (code "489") (name "unconnected-(J389-Pad1)") (class "Default")
      (node (ref "J389") (pin "1") (pinfunction "1_1") (pintype "passive"))
    )
    (net (code "490") (name "unconnected-(J390-Pad1)") (class "Default")
      (node (ref "J390") (pin "1") (pinfunction "1_1") (pintype "passive"))
    )
    (net (code "491") (name "unconnected-(J391-Pad1)") (class "Default")
      (node (ref "J391") (pin "1") (pinfunction "1_1") (pintype "passive"))
    )
    (net (code "492") (name "unconnected-(U$1-EN-Pad1)") (class "Default")
      (node (ref "U$1") (pin "1") (pinfunction "EN_1") (pintype "bidirectional"))
    )
    (net (code "493") (name "unconnected-(X1AA-KL-Pad33)") (class "Default")
      (node (ref "X1") (pin "33") (pinfunction "KL_33") (pintype "passive"))
    )
    (net (code "494") (name "unconnected-(X1AB-KL-Pad34)") (class "Default")
      (node (ref "X1") (pin "34") (pinfunction "KL_34") (pintype "passive"))
    )
  )
)
